# Sheet1.net
KiCad netlist of a schematic drawn in Altium Designer
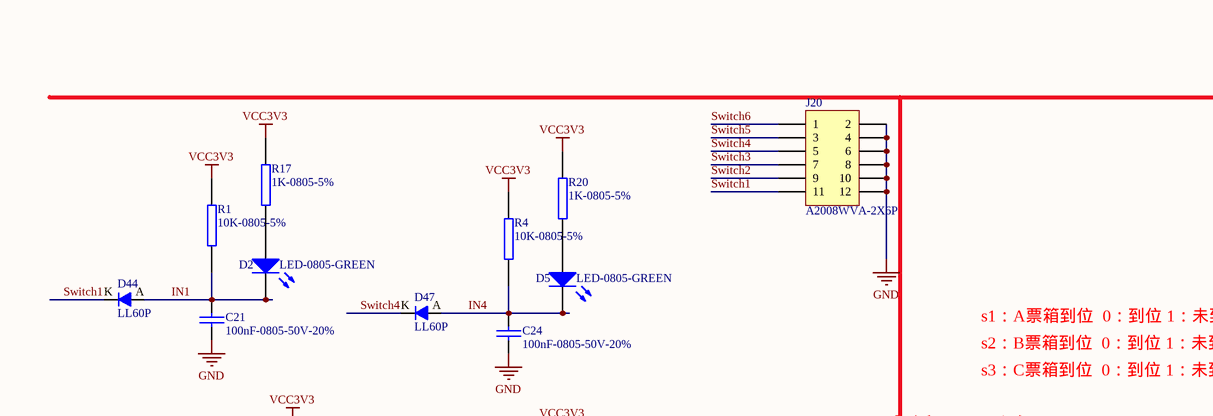
[diagram p0: Sheet1.SchDoc, top left]
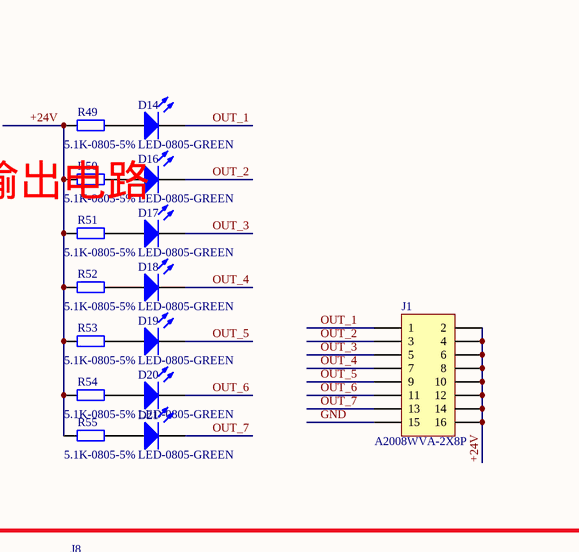
[diagram p1: Sheet1.SchDoc, top middle]
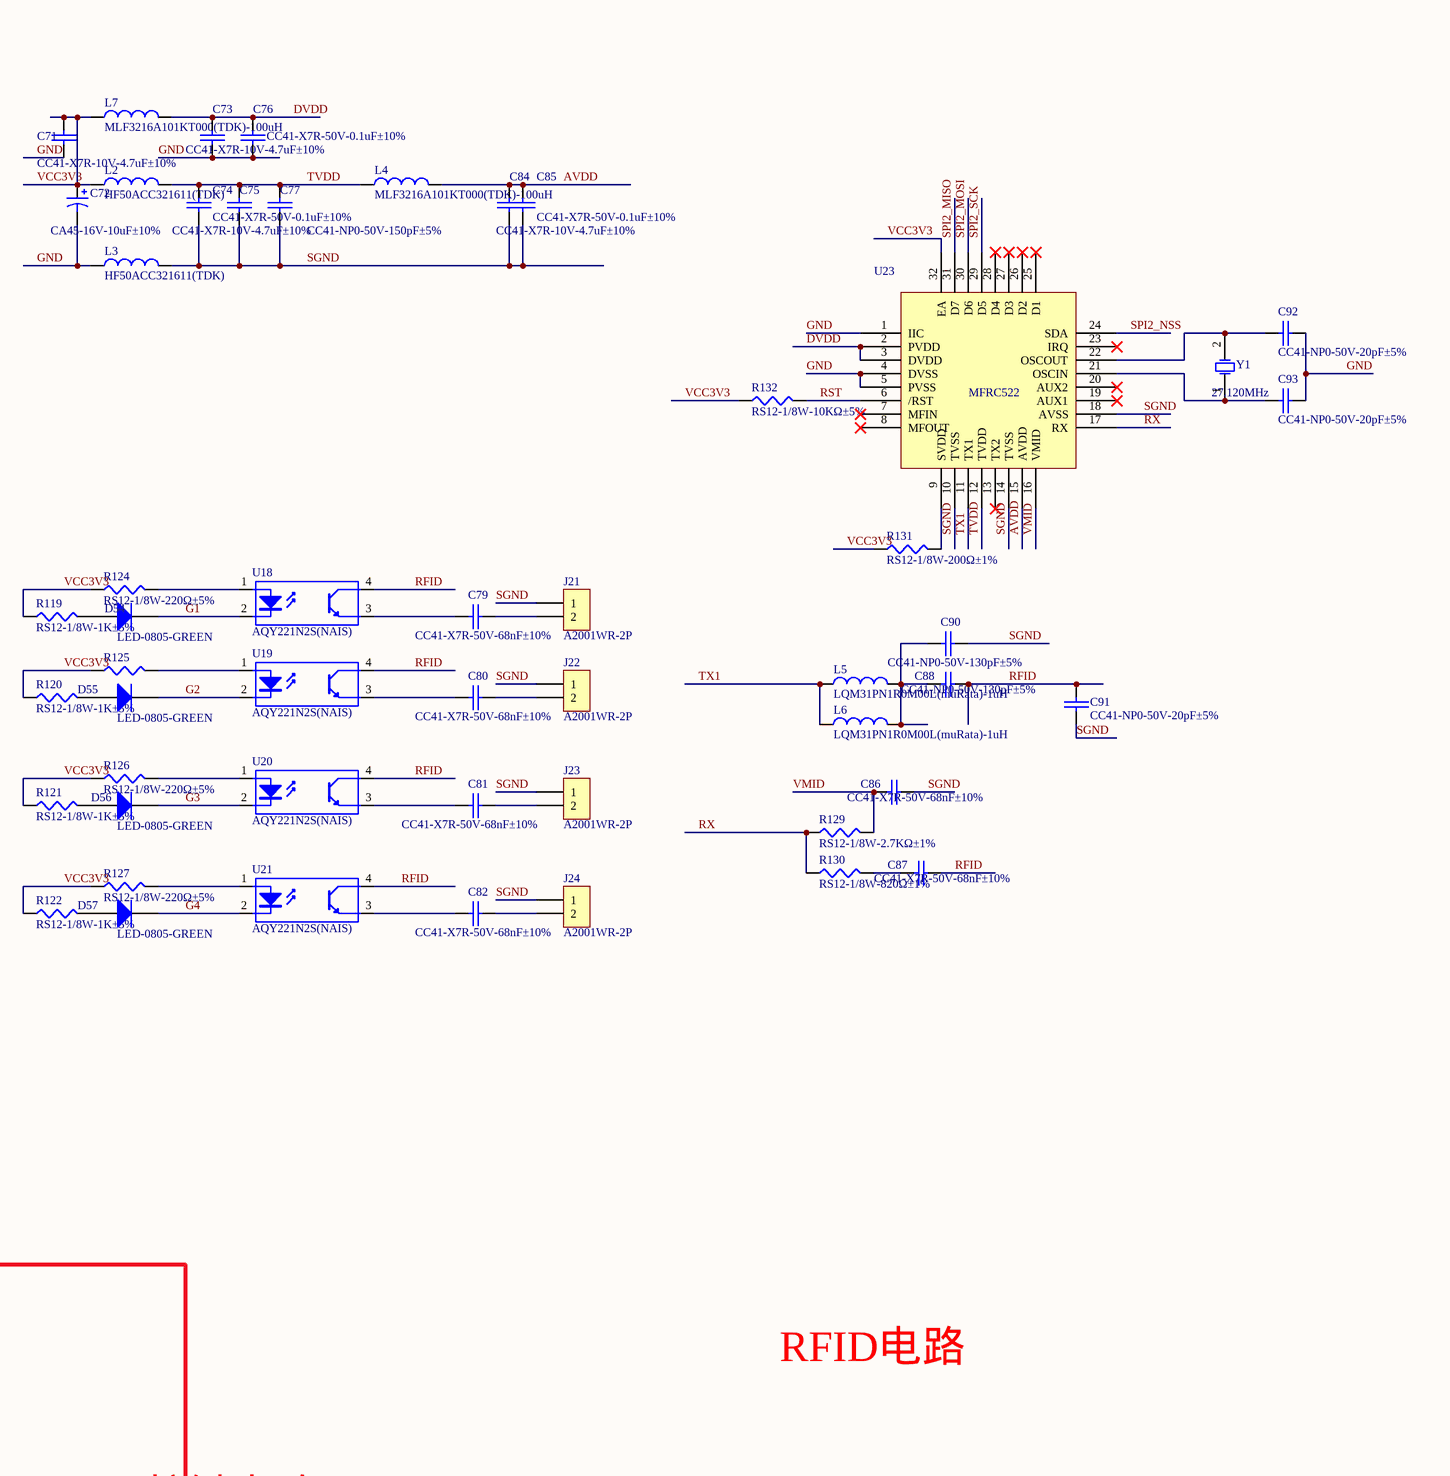
[diagram p2: Sheet1.SchDoc, top right]
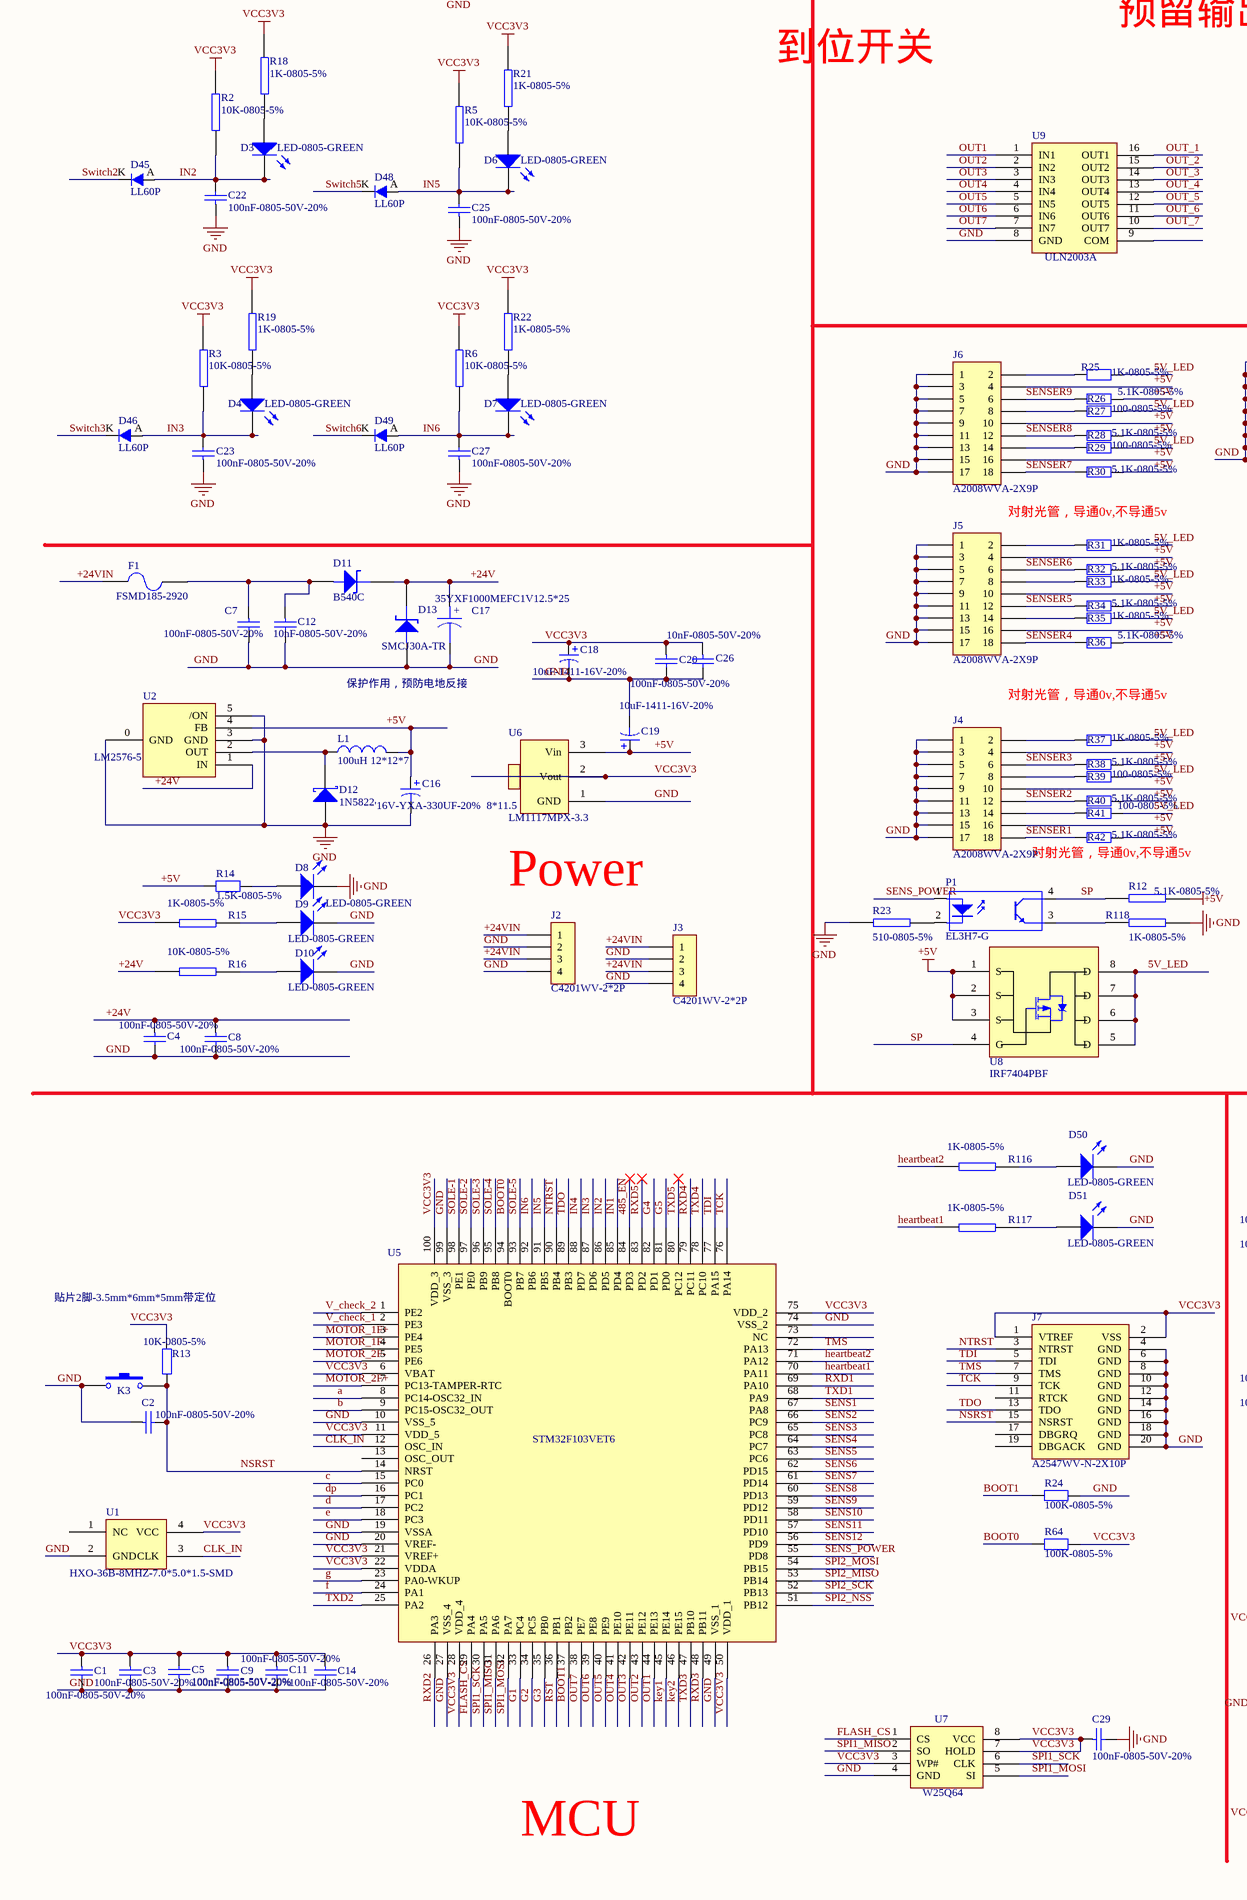
[diagram p3: Sheet1.SchDoc, bottom left]
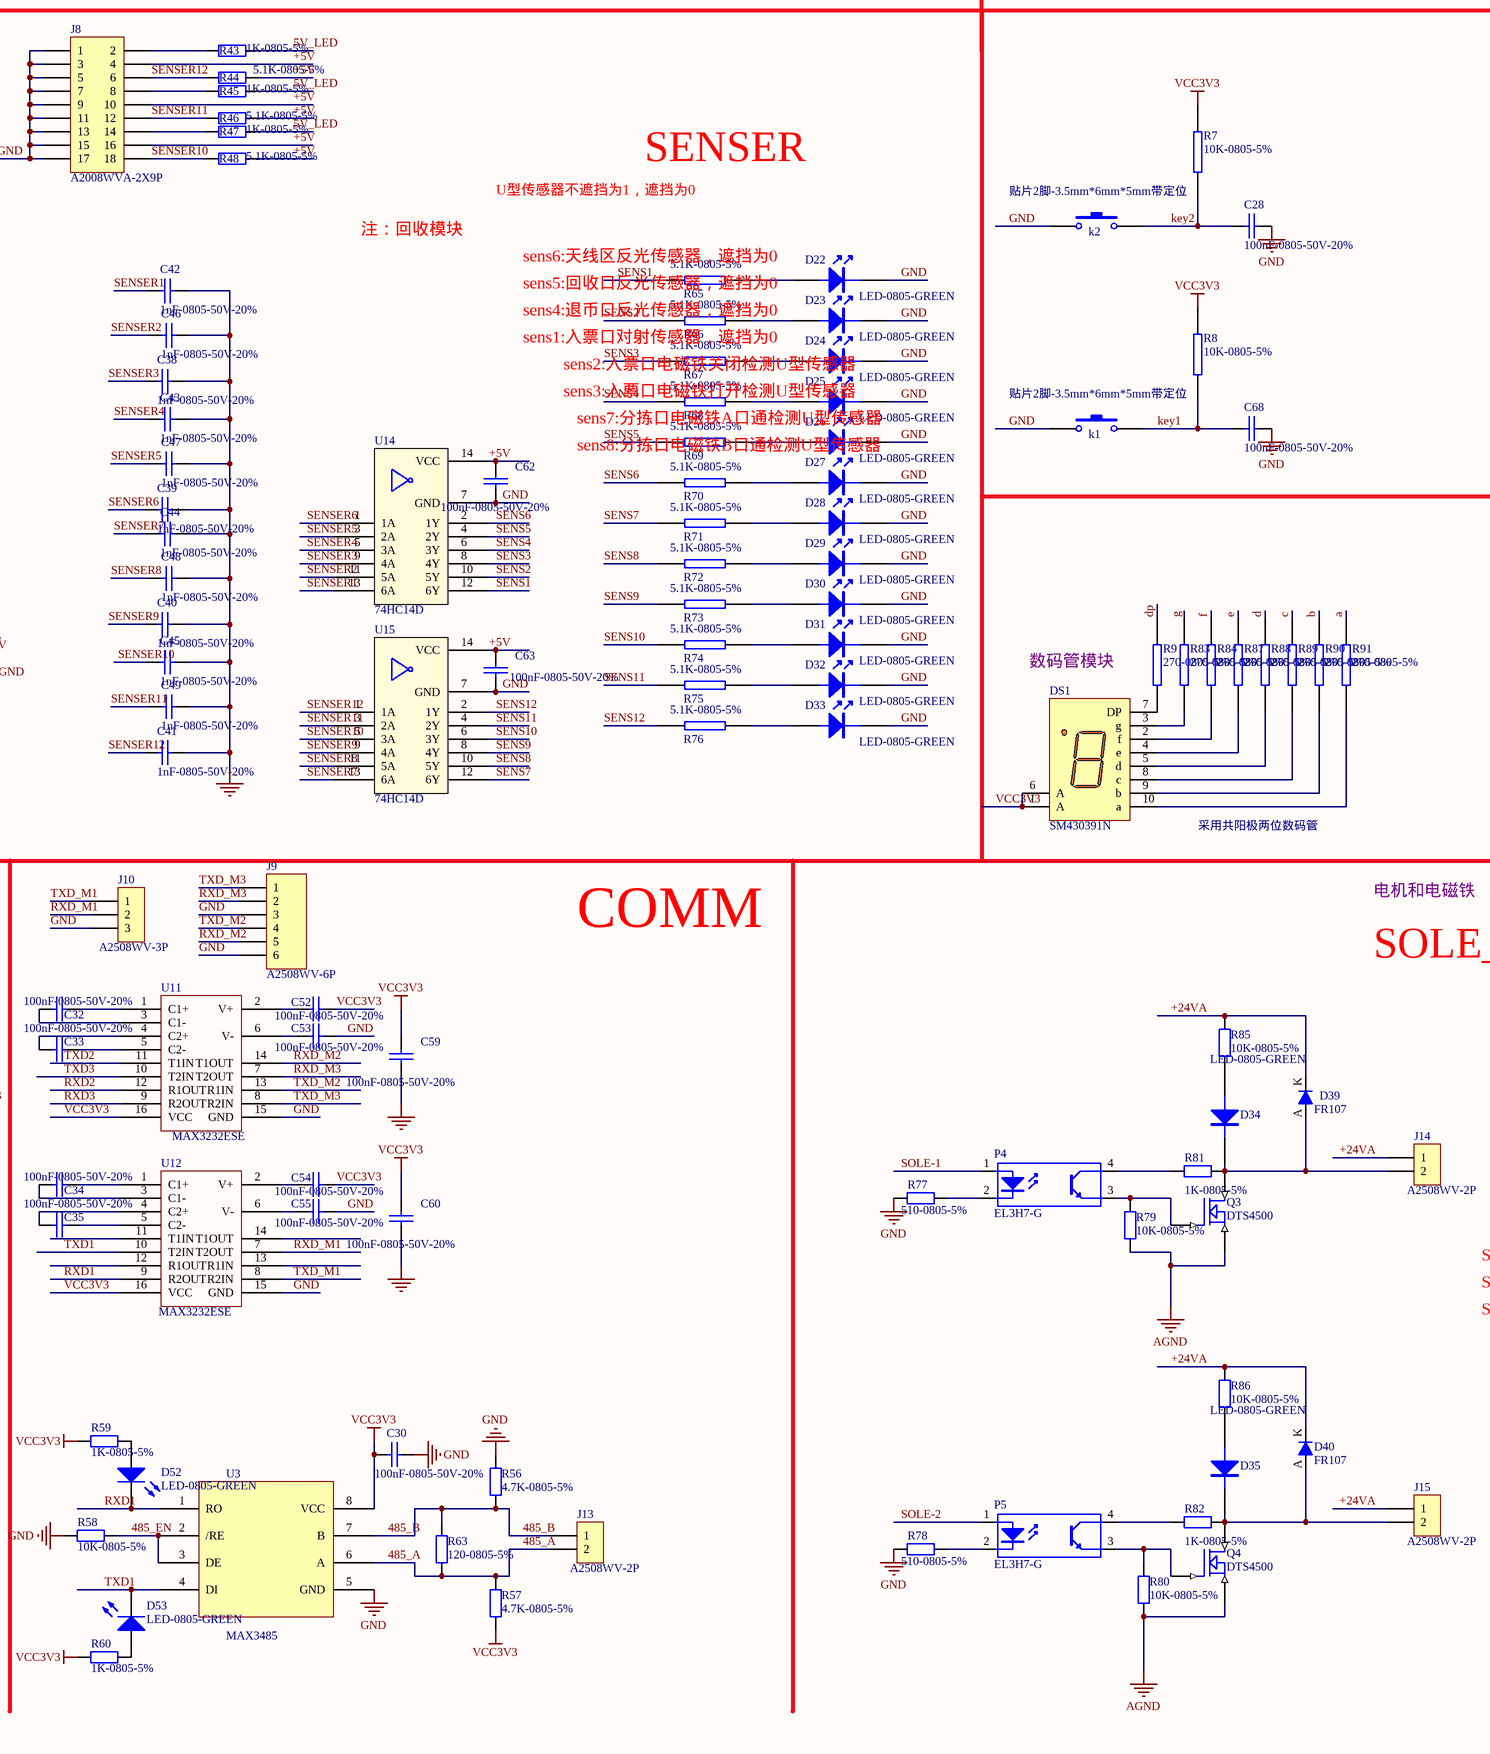
[diagram p4: Sheet1.SchDoc, bottom middle]
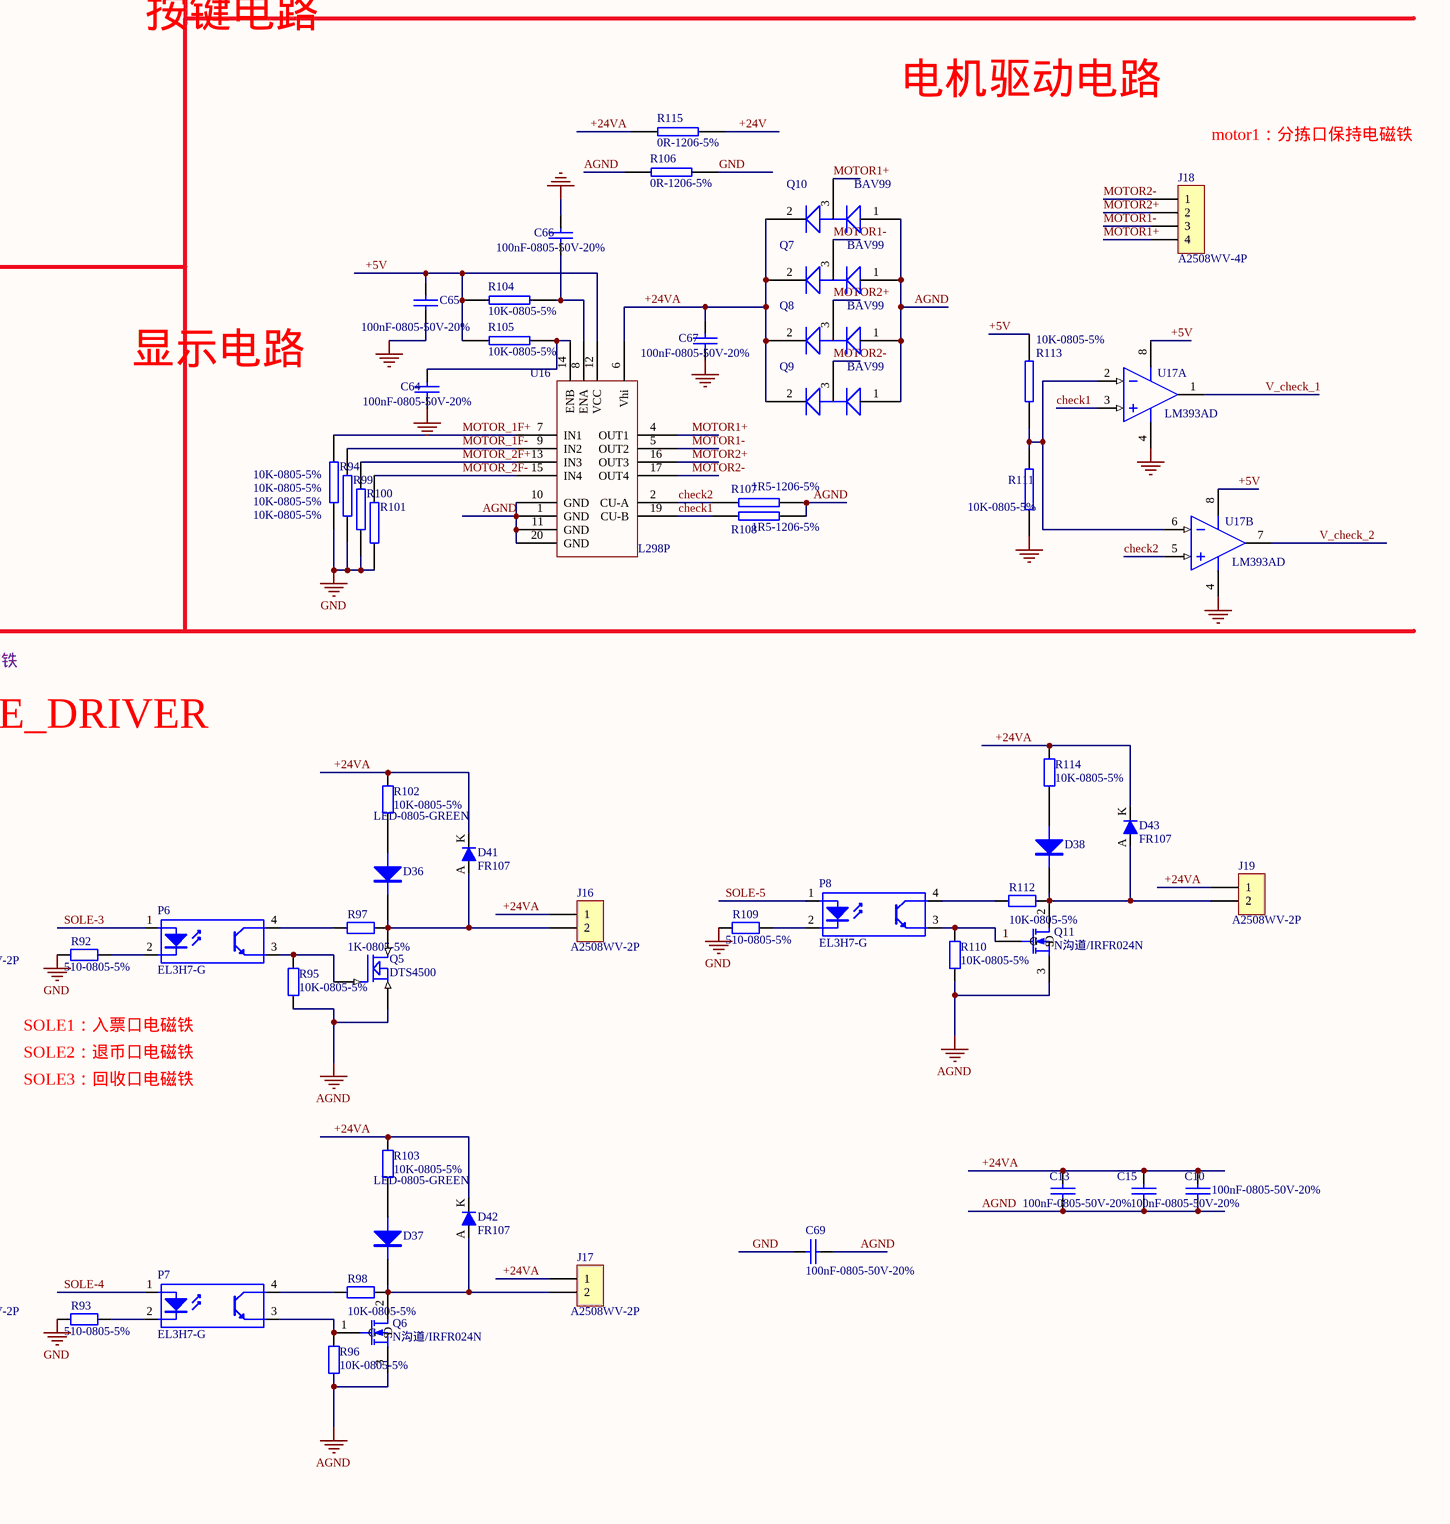
[diagram p5: Sheet1.SchDoc, bottom right]

(export (version "E")
  (design (tool "Eeschema 10.0.6"))
  (components
    (comp (ref "C1")
      (value "100nF-0805-50V-20%")
      (footprint "0805")
      (description "Capacitor")
      (libsource (lib "*") (part "CAP"))
    )
    (comp (ref "C2")
      (value "100nF-0805-50V-20%")
      (footprint "0805")
      (description "Capacitor")
      (libsource (lib "*") (part "CAP"))
    )
    (comp (ref "C3")
      (value "100nF-0805-50V-20%")
      (footprint "0805")
      (description "Capacitor")
      (libsource (lib "*") (part "CAP"))
    )
    (comp (ref "C4")
      (value "100nF-0805-50V-20%")
      (footprint "0805")
      (description "Capacitor")
      (libsource (lib "*") (part "CAP"))
    )
    (comp (ref "C5")
      (value "100nF-0805-50V-20%")
      (footprint "0805")
      (description "Capacitor")
      (libsource (lib "*") (part "CAP"))
    )
    (comp (ref "C7")
      (value "100nF-0805-50V-20%")
      (footprint "0805")
      (description "Capacitor")
      (libsource (lib "*") (part "CAP"))
    )
    (comp (ref "C8")
      (value "100nF-0805-50V-20%")
      (footprint "0805")
      (description "Capacitor")
      (libsource (lib "*") (part "CAP"))
    )
    (comp (ref "C9")
      (value "100nF-0805-50V-20%")
      (footprint "0805")
      (description "Capacitor")
      (libsource (lib "*") (part "CAP"))
    )
    (comp (ref "C10")
      (value "100nF-0805-50V-20%")
      (footprint "0805")
      (description "Capacitor")
      (libsource (lib "*") (part "CAP"))
    )
    (comp (ref "C11")
      (value "100nF-0805-50V-20%")
      (footprint "0805")
      (description "Capacitor")
      (libsource (lib "*") (part "CAP"))
    )
    (comp (ref "C12")
      (value "10nF-0805-50V-20%")
      (footprint "0805")
      (description "Capacitor")
      (libsource (lib "*") (part "CAP"))
    )
    (comp (ref "C13")
      (value "100nF-0805-50V-20%")
      (footprint "0805")
      (description "Capacitor")
      (libsource (lib "*") (part "CAP"))
    )
    (comp (ref "C14")
      (value "100nF-0805-50V-20%")
      (footprint "0805")
      (description "Capacitor")
      (libsource (lib "*") (part "CAP"))
    )
    (comp (ref "C15")
      (value "100nF-0805-50V-20%")
      (footprint "0805")
      (description "Capacitor")
      (libsource (lib "*") (part "CAP"))
    )
    (comp (ref "C16")
      (value "'16V-YXA-330UF-20%  8*11.5")
      (footprint "RB.2/.4 - 8MM")
      (description "Polarized Capacitor (Radial)")
      (fields (field (name "PUBLISHER") "Altium Limited"))
      (libsource (lib "Miscellaneous Devices") (part "Cap Pol1"))
    )
    (comp (ref "C17")
      (value "35YXF1000MEFC1V12.5*25")
      (footprint "RB.2/.4")
      (description "Capacitor")
      (libsource (lib "*") (part "CAPACITOR POL"))
    )
    (comp (ref "C18")
      (value "10uF-1411-16V-20%")
      (footprint "1411-B")
      (description "Polarized Capacitor (Radial)")
      (fields (field (name "PUBLISHER") "Altium Limited"))
      (libsource (lib "Miscellaneous Devices") (part "Cap Pol1"))
    )
    (comp (ref "C19")
      (value "10uF-1411-16V-20%")
      (footprint "1411-B")
      (description "Polarized Capacitor (Radial)")
      (fields (field (name "PUBLISHER") "Altium Limited"))
      (libsource (lib "Miscellaneous Devices") (part "Cap Pol1"))
    )
    (comp (ref "C20")
      (value "100nF-0805-50V-20%")
      (footprint "0805")
      (description "Capacitor")
      (libsource (lib "*") (part "CAP"))
    )
    (comp (ref "C21")
      (value "100nF-0805-50V-20%")
      (footprint "0805")
      (description "Capacitor")
      (libsource (lib "*") (part "CAP"))
    )
    (comp (ref "C22")
      (value "100nF-0805-50V-20%")
      (footprint "0805")
      (description "Capacitor")
      (libsource (lib "*") (part "CAP"))
    )
    (comp (ref "C23")
      (value "100nF-0805-50V-20%")
      (footprint "0805")
      (description "Capacitor")
      (libsource (lib "*") (part "CAP"))
    )
    (comp (ref "C24")
      (value "100nF-0805-50V-20%")
      (footprint "0805")
      (description "Capacitor")
      (libsource (lib "*") (part "CAP"))
    )
    (comp (ref "C25")
      (value "100nF-0805-50V-20%")
      (footprint "0805")
      (description "Capacitor")
      (libsource (lib "*") (part "CAP"))
    )
    (comp (ref "C26")
      (value "10nF-0805-50V-20%")
      (footprint "0805")
      (description "Capacitor")
      (libsource (lib "*") (part "CAP"))
    )
    (comp (ref "C27")
      (value "100nF-0805-50V-20%")
      (footprint "0805")
      (description "Capacitor")
      (libsource (lib "*") (part "CAP"))
    )
    (comp (ref "C28")
      (value "100nF-0805-50V-20%")
      (footprint "0805")
      (description "Capacitor")
      (libsource (lib "*") (part "CAP"))
    )
    (comp (ref "C29")
      (value "100nF-0805-50V-20%")
      (footprint "0805")
      (description "Capacitor")
      (libsource (lib "*") (part "CAP"))
    )
    (comp (ref "C30")
      (value "100nF-0805-50V-20%")
      (footprint "0805")
      (description "Capacitor")
      (libsource (lib "*") (part "CAP"))
    )
    (comp (ref "C32")
      (value "100nF-0805-50V-20%")
      (footprint "0805")
      (description "Capacitor")
      (libsource (lib "") (part "CAP_1"))
    )
    (comp (ref "C33")
      (value "100nF-0805-50V-20%")
      (footprint "0805")
      (description "Capacitor")
      (libsource (lib "") (part "CAP_1"))
    )
    (comp (ref "C34")
      (value "100nF-0805-50V-20%")
      (footprint "0805")
      (description "Capacitor")
      (libsource (lib "") (part "CAP_1"))
    )
    (comp (ref "C35")
      (value "100nF-0805-50V-20%")
      (footprint "0805")
      (description "Capacitor")
      (libsource (lib "") (part "CAP_1"))
    )
    (comp (ref "C38")
      (value "1nF-0805-50V-20%")
      (footprint "0805")
      (description "Capacitor")
      (libsource (lib "*") (part "CAP"))
    )
    (comp (ref "C39")
      (value "1nF-0805-50V-20%")
      (footprint "0805")
      (description "Capacitor")
      (libsource (lib "*") (part "CAP"))
    )
    (comp (ref "C40")
      (value "1nF-0805-50V-20%")
      (footprint "0805")
      (description "Capacitor")
      (libsource (lib "*") (part "CAP"))
    )
    (comp (ref "C41")
      (value "1nF-0805-50V-20%")
      (footprint "0805")
      (description "Capacitor")
      (libsource (lib "*") (part "CAP"))
    )
    (comp (ref "C42")
      (value "1nF-0805-50V-20%")
      (footprint "0805")
      (description "Capacitor")
      (libsource (lib "*") (part "CAP"))
    )
    (comp (ref "C43")
      (value "1nF-0805-50V-20%")
      (footprint "0805")
      (description "Capacitor")
      (libsource (lib "*") (part "CAP"))
    )
    (comp (ref "C44")
      (value "1nF-0805-50V-20%")
      (footprint "0805")
      (description "Capacitor")
      (libsource (lib "*") (part "CAP"))
    )
    (comp (ref "C45")
      (value "1nF-0805-50V-20%")
      (footprint "0805")
      (description "Capacitor")
      (libsource (lib "*") (part "CAP"))
    )
    (comp (ref "C46")
      (value "1nF-0805-50V-20%")
      (footprint "0805")
      (description "Capacitor")
      (libsource (lib "*") (part "CAP"))
    )
    (comp (ref "C47")
      (value "1nF-0805-50V-20%")
      (footprint "0805")
      (description "Capacitor")
      (libsource (lib "*") (part "CAP"))
    )
    (comp (ref "C48")
      (value "1nF-0805-50V-20%")
      (footprint "0805")
      (description "Capacitor")
      (libsource (lib "*") (part "CAP"))
    )
    (comp (ref "C49")
      (value "1nF-0805-50V-20%")
      (footprint "0805")
      (description "Capacitor")
      (libsource (lib "*") (part "CAP"))
    )
    (comp (ref "C52")
      (value "100nF-0805-50V-20%")
      (footprint "0805")
      (description "Capacitor")
      (libsource (lib "") (part "CAP_1"))
    )
    (comp (ref "C53")
      (value "100nF-0805-50V-20%")
      (footprint "0805")
      (description "Capacitor")
      (libsource (lib "") (part "CAP_1"))
    )
    (comp (ref "C54")
      (value "100nF-0805-50V-20%")
      (footprint "0805")
      (description "Capacitor")
      (libsource (lib "") (part "CAP_1"))
    )
    (comp (ref "C55")
      (value "100nF-0805-50V-20%")
      (footprint "0805")
      (description "Capacitor")
      (libsource (lib "") (part "CAP_1"))
    )
    (comp (ref "C59")
      (value "100nF-0805-50V-20%")
      (footprint "0805")
      (description "Capacitor")
      (libsource (lib "*") (part "CAP"))
    )
    (comp (ref "C60")
      (value "100nF-0805-50V-20%")
      (footprint "0805")
      (description "Capacitor")
      (libsource (lib "*") (part "CAP"))
    )
    (comp (ref "C62")
      (value "100nF-0805-50V-20%")
      (footprint "0805")
      (description "Capacitor")
      (libsource (lib "*") (part "CAP"))
    )
    (comp (ref "C63")
      (value "100nF-0805-50V-20%")
      (footprint "0805")
      (description "Capacitor")
      (libsource (lib "*") (part "CAP"))
    )
    (comp (ref "C64")
      (value "100nF-0805-50V-20%")
      (footprint "0805")
      (description "Capacitor")
      (libsource (lib "*") (part "CAP"))
    )
    (comp (ref "C65")
      (value "100nF-0805-50V-20%")
      (footprint "0805")
      (description "Capacitor")
      (libsource (lib "*") (part "CAP"))
    )
    (comp (ref "C66")
      (value "100nF-0805-50V-20%")
      (footprint "0805")
      (description "Capacitor")
      (libsource (lib "*") (part "CAP"))
    )
    (comp (ref "C67")
      (value "100nF-0805-50V-20%")
      (footprint "0805")
      (description "Capacitor")
      (libsource (lib "*") (part "CAP"))
    )
    (comp (ref "C68")
      (value "100nF-0805-50V-20%")
      (footprint "0805")
      (description "Capacitor")
      (libsource (lib "*") (part "CAP"))
    )
    (comp (ref "C69")
      (value "100nF-0805-50V-20%")
      (footprint "0805")
      (description "Capacitor")
      (libsource (lib "*") (part "CAP"))
    )
    (comp (ref "C71")
      (value "CC41-X7R-10V-4.7uF±10%")
      (footprint "RFID主控板-MFC522:1206C")
      (description "Capacitor")
      (libsource (lib "PCB_Project1_1") (part "CAP"))
    )
    (comp (ref "C72")
      (value "CA45-16V-10uF±10%")
      (footprint "RFID主控板-MFC522:3216-A")
      (description "Polarized Capacitor (Radial)")
      (fields (field (name "PUBLISHER") "Altium Limited"))
      (libsource (lib "Miscellaneous Devices") (part "Cap Pol1"))
    )
    (comp (ref "C73")
      (value "CC41-X7R-10V-4.7uF±10%")
      (footprint "1206C")
      (description "Capacitor")
      (libsource (lib "PCB_Project1_1") (part "CAP"))
    )
    (comp (ref "C74")
      (value "CC41-X7R-10V-4.7uF±10%")
      (footprint "RFID主控板-MFC522:1206C")
      (description "Capacitor")
      (libsource (lib "PCB_Project1_1") (part "CAP"))
    )
    (comp (ref "C75")
      (value "CC41-X7R-50V-0.1uF±10%")
      (footprint "0805C")
      (description "Capacitor")
      (libsource (lib "PCB_Project1_1") (part "CAP"))
    )
    (comp (ref "C76")
      (value "CC41-X7R-50V-0.1uF±10%")
      (footprint "0805C")
      (description "Capacitor")
      (libsource (lib "PCB_Project1_1") (part "CAP"))
    )
    (comp (ref "C77")
      (value "CC41-NP0-50V-150pF±5%")
      (footprint "0805C")
      (description "Capacitor")
      (libsource (lib "PCB_Project1_1") (part "CAP"))
    )
    (comp (ref "C79")
      (value "CC41-X7R-50V-68nF±10%")
      (footprint "RFID主控板-MFC522:0805C")
      (description "Capacitor")
      (libsource (lib "PCB_Project1_1") (part "CAP"))
    )
    (comp (ref "C80")
      (value "CC41-X7R-50V-68nF±10%")
      (footprint "0805C")
      (description "Capacitor")
      (libsource (lib "PCB_Project1_1") (part "CAP"))
    )
    (comp (ref "C81")
      (value "CC41-X7R-50V-68nF±10%")
      (footprint "0805C")
      (description "Capacitor")
      (libsource (lib "PCB_Project1_1") (part "CAP"))
    )
    (comp (ref "C82")
      (value "CC41-X7R-50V-68nF±10%")
      (footprint "0805C")
      (description "Capacitor")
      (libsource (lib "PCB_Project1_1") (part "CAP"))
    )
    (comp (ref "C84")
      (value "CC41-X7R-10V-4.7uF±10%")
      (footprint "1206C")
      (description "Capacitor")
      (libsource (lib "PCB_Project1_1") (part "CAP"))
    )
    (comp (ref "C85")
      (value "CC41-X7R-50V-0.1uF±10%")
      (footprint "0805C")
      (description "Capacitor")
      (libsource (lib "PCB_Project1_1") (part "CAP"))
    )
    (comp (ref "C86")
      (value "CC41-X7R-50V-68nF±10%")
      (footprint "0805C")
      (description "Capacitor")
      (libsource (lib "PCB_Project1_1") (part "CAP"))
    )
    (comp (ref "C87")
      (value "CC41-X7R-50V-68nF±10%")
      (footprint "0805C")
      (description "Capacitor")
      (libsource (lib "PCB_Project1_1") (part "CAP"))
    )
    (comp (ref "C88")
      (value "CC41-NP0-50V-130pF±5%")
      (footprint "0805C")
      (description "Capacitor")
      (libsource (lib "PCB_Project1_1") (part "CAP"))
    )
    (comp (ref "C90")
      (value "CC41-NP0-50V-130pF±5%")
      (footprint "0805C")
      (description "Capacitor")
      (libsource (lib "PCB_Project1_1") (part "CAP"))
    )
    (comp (ref "C91")
      (value "CC41-NP0-50V-20pF±5%")
      (footprint "0805C")
      (description "Capacitor")
      (libsource (lib "PCB_Project1_1") (part "CAP"))
    )
    (comp (ref "C92")
      (value "CC41-NP0-50V-20pF±5%")
      (footprint "0805C")
      (description "Capacitor")
      (libsource (lib "PCB_Project1_1") (part "CAP"))
    )
    (comp (ref "C93")
      (value "CC41-NP0-50V-20pF±5%")
      (footprint "0805C")
      (description "Capacitor")
      (libsource (lib "PCB_Project1_1") (part "CAP"))
    )
    (comp (ref "D2")
      (value "LED-0805-GREEN")
      (footprint "LED-0805")
      (description "Typical INFRARED GaAs LED")
      (fields (field (name "PUBLISHER") "Altium Limited"))
      (libsource (lib "Miscellaneous Devices") (part "LED0"))
    )
    (comp (ref "D3")
      (value "LED-0805-GREEN")
      (footprint "LED-0805")
      (description "Typical INFRARED GaAs LED")
      (fields (field (name "PUBLISHER") "Altium Limited"))
      (libsource (lib "Miscellaneous Devices") (part "LED0"))
    )
    (comp (ref "D4")
      (value "LED-0805-GREEN")
      (footprint "LED-0805")
      (description "Typical INFRARED GaAs LED")
      (fields (field (name "PUBLISHER") "Altium Limited"))
      (libsource (lib "Miscellaneous Devices") (part "LED0"))
    )
    (comp (ref "D5")
      (value "LED-0805-GREEN")
      (footprint "LED-0805")
      (description "Typical INFRARED GaAs LED")
      (fields (field (name "PUBLISHER") "Altium Limited"))
      (libsource (lib "Miscellaneous Devices") (part "LED0"))
    )
    (comp (ref "D6")
      (value "LED-0805-GREEN")
      (footprint "LED-0805")
      (description "Typical INFRARED GaAs LED")
      (fields (field (name "PUBLISHER") "Altium Limited"))
      (libsource (lib "Miscellaneous Devices") (part "LED0"))
    )
    (comp (ref "D7")
      (value "LED-0805-GREEN")
      (footprint "LED-0805")
      (description "Typical INFRARED GaAs LED")
      (fields (field (name "PUBLISHER") "Altium Limited"))
      (libsource (lib "Miscellaneous Devices") (part "LED0"))
    )
    (comp (ref "D8")
      (value "LED-0805-GREEN")
      (footprint "LED-0805")
      (description "Typical INFRARED GaAs LED")
      (fields (field (name "PUBLISHER") "Altium Limited"))
      (libsource (lib "Miscellaneous Devices") (part "LED0"))
    )
    (comp (ref "D9")
      (value "LED-0805-GREEN")
      (footprint "LED-0805")
      (description "Typical INFRARED GaAs LED")
      (fields (field (name "PUBLISHER") "Altium Limited"))
      (libsource (lib "Miscellaneous Devices") (part "LED0"))
    )
    (comp (ref "D10")
      (value "LED-0805-GREEN")
      (footprint "LED-0805")
      (description "Typical INFRARED GaAs LED")
      (fields (field (name "PUBLISHER") "Altium Limited"))
      (libsource (lib "Miscellaneous Devices") (part "LED0"))
    )
    (comp (ref "D11")
      (value "B540C")
      (footprint "SMC")
      (description "Zener Diode")
      (libsource (lib "*") (part "ZENER2"))
    )
    (comp (ref "D12")
      (value "1N5822")
      (footprint "IN5822 SMT")
      (description "Schottky Diode")
      (fields (field (name "PUBLISHER") "Altium Limited"))
      (libsource (lib "Miscellaneous Devices") (part "D Schottky"))
    )
    (comp (ref "D13")
      (value "SMCJ30A-TR")
      (footprint "SMC")
      (description "Zener Diode")
      (libsource (lib "*") (part "ZENER2"))
    )
    (comp (ref "D14")
      (value "LED-0805-GREEN")
      (footprint "LED-0805")
      (description "Typical INFRARED GaAs LED")
      (fields (field (name "PUBLISHER") "Altium Limited"))
      (libsource (lib "Miscellaneous Devices") (part "LED0"))
    )
    (comp (ref "D16")
      (value "LED-0805-GREEN")
      (footprint "LED-0805")
      (description "Typical INFRARED GaAs LED")
      (fields (field (name "PUBLISHER") "Altium Limited"))
      (libsource (lib "Miscellaneous Devices") (part "LED0"))
    )
    (comp (ref "D17")
      (value "LED-0805-GREEN")
      (footprint "LED-0805")
      (description "Typical INFRARED GaAs LED")
      (fields (field (name "PUBLISHER") "Altium Limited"))
      (libsource (lib "Miscellaneous Devices") (part "LED0"))
    )
    (comp (ref "D18")
      (value "LED-0805-GREEN")
      (footprint "LED-0805")
      (description "Typical INFRARED GaAs LED")
      (fields (field (name "PUBLISHER") "Altium Limited"))
      (libsource (lib "Miscellaneous Devices") (part "LED0"))
    )
    (comp (ref "D19")
      (value "LED-0805-GREEN")
      (footprint "LED-0805")
      (description "Typical INFRARED GaAs LED")
      (fields (field (name "PUBLISHER") "Altium Limited"))
      (libsource (lib "Miscellaneous Devices") (part "LED0"))
    )
    (comp (ref "D20")
      (value "LED-0805-GREEN")
      (footprint "LED-0805")
      (description "Typical INFRARED GaAs LED")
      (fields (field (name "PUBLISHER") "Altium Limited"))
      (libsource (lib "Miscellaneous Devices") (part "LED0"))
    )
    (comp (ref "D21")
      (value "LED-0805-GREEN")
      (footprint "LED-0805")
      (description "Typical INFRARED GaAs LED")
      (fields (field (name "PUBLISHER") "Altium Limited"))
      (libsource (lib "Miscellaneous Devices") (part "LED0"))
    )
    (comp (ref "D22") (value "LED-0805-GREEN") (footprint "LED-0805") (libsource (lib "*") (part "LED")))
    (comp (ref "D23") (value "LED-0805-GREEN") (footprint "LED-0805") (libsource (lib "*") (part "LED")))
    (comp (ref "D24") (value "LED-0805-GREEN") (footprint "LED-0805") (libsource (lib "*") (part "LED")))
    (comp (ref "D25") (value "LED-0805-GREEN") (footprint "LED-0805") (libsource (lib "*") (part "LED")))
    (comp (ref "D26") (value "LED-0805-GREEN") (footprint "LED-0805") (libsource (lib "*") (part "LED")))
    (comp (ref "D27") (value "LED-0805-GREEN") (footprint "LED-0805") (libsource (lib "*") (part "LED")))
    (comp (ref "D28") (value "LED-0805-GREEN") (footprint "LED-0805") (libsource (lib "*") (part "LED")))
    (comp (ref "D29") (value "LED-0805-GREEN") (footprint "LED-0805") (libsource (lib "*") (part "LED")))
    (comp (ref "D30") (value "LED-0805-GREEN") (footprint "LED-0805") (libsource (lib "*") (part "LED")))
    (comp (ref "D31") (value "LED-0805-GREEN") (footprint "LED-0805") (libsource (lib "*") (part "LED")))
    (comp (ref "D32") (value "LED-0805-GREEN") (footprint "LED-0805") (libsource (lib "*") (part "LED")))
    (comp (ref "D33") (value "LED-0805-GREEN") (footprint "LED-0805") (libsource (lib "*") (part "LED")))
    (comp (ref "D34")
      (value "LED-0805-GREEN")
      (footprint "LED-0805")
      (description "Diode")
      (libsource (lib "*") (part "DIODE"))
    )
    (comp (ref "D35")
      (value "LED-0805-GREEN")
      (footprint "LED-0805")
      (description "Diode")
      (libsource (lib "*") (part "DIODE"))
    )
    (comp (ref "D36")
      (value "LED-0805-GREEN")
      (footprint "LED-0805")
      (description "Diode")
      (libsource (lib "*") (part "DIODE"))
    )
    (comp (ref "D37")
      (value "LED-0805-GREEN")
      (footprint "LED-0805")
      (description "Diode")
      (libsource (lib "*") (part "DIODE"))
    )
    (comp (ref "D38")
      (value "LED-0805-GREEN")
      (footprint "LED-0805")
      (description "Diode")
      (libsource (lib "*") (part "DIODE"))
    )
    (comp (ref "D39")
      (value "FR107")
      (footprint "DO-214AC")
      (libsource (lib "T-SZLG-MCB-16-0247-PN-37990042-SZLG-Hopper-01控制板") (part "1N4148"))
    )
    (comp (ref "D40")
      (value "FR107")
      (footprint "DO-214AC")
      (libsource (lib "T-SZLG-MCB-16-0247-PN-37990042-SZLG-Hopper-01控制板") (part "1N4148"))
    )
    (comp (ref "D41")
      (value "FR107")
      (footprint "DO-214AC")
      (libsource (lib "T-SZLG-MCB-16-0247-PN-37990042-SZLG-Hopper-01控制板") (part "1N4148"))
    )
    (comp (ref "D42")
      (value "FR107")
      (footprint "DO-214AC")
      (libsource (lib "T-SZLG-MCB-16-0247-PN-37990042-SZLG-Hopper-01控制板") (part "1N4148"))
    )
    (comp (ref "D43")
      (value "FR107")
      (footprint "DO-214AC")
      (libsource (lib "T-SZLG-MCB-16-0247-PN-37990042-SZLG-Hopper-01控制板") (part "1N4148"))
    )
    (comp (ref "D44")
      (value "LL60P")
      (footprint "PCB22:DIODE")
      (libsource (lib "T-SZLG-MCB-16-0247-PN-37990042-SZLG-Hopper-01控制板") (part "1N4148"))
    )
    (comp (ref "D45")
      (value "LL60P")
      (footprint "DIODE")
      (libsource (lib "T-SZLG-MCB-16-0247-PN-37990042-SZLG-Hopper-01控制板") (part "1N4148"))
    )
    (comp (ref "D46")
      (value "LL60P")
      (footprint "DIODE")
      (libsource (lib "T-SZLG-MCB-16-0247-PN-37990042-SZLG-Hopper-01控制板") (part "1N4148"))
    )
    (comp (ref "D47")
      (value "LL60P")
      (footprint "DIODE")
      (libsource (lib "T-SZLG-MCB-16-0247-PN-37990042-SZLG-Hopper-01控制板") (part "1N4148"))
    )
    (comp (ref "D48")
      (value "LL60P")
      (footprint "DIODE")
      (libsource (lib "T-SZLG-MCB-16-0247-PN-37990042-SZLG-Hopper-01控制板") (part "1N4148"))
    )
    (comp (ref "D49")
      (value "LL60P")
      (footprint "DIODE")
      (libsource (lib "T-SZLG-MCB-16-0247-PN-37990042-SZLG-Hopper-01控制板") (part "1N4148"))
    )
    (comp (ref "D50")
      (value "LED-0805-GREEN")
      (footprint "LED-0805")
      (description "Typical INFRARED GaAs LED")
      (fields (field (name "PUBLISHER") "Altium Limited"))
      (libsource (lib "Miscellaneous Devices") (part "LED0"))
    )
    (comp (ref "D51")
      (value "LED-0805-GREEN")
      (footprint "LED-0805")
      (description "Typical INFRARED GaAs LED")
      (fields (field (name "PUBLISHER") "Altium Limited"))
      (libsource (lib "Miscellaneous Devices") (part "LED0"))
    )
    (comp (ref "D52")
      (value "LED-0805-GREEN")
      (footprint "LED-0805")
      (description "Typical INFRARED GaAs LED")
      (fields (field (name "PUBLISHER") "Altium Limited"))
      (libsource (lib "Miscellaneous Devices") (part "LED0"))
    )
    (comp (ref "D53")
      (value "LED-0805-GREEN")
      (footprint "LED-0805")
      (description "Typical INFRARED GaAs LED")
      (fields (field (name "PUBLISHER") "Altium Limited"))
      (libsource (lib "Miscellaneous Devices") (part "LED0"))
    )
    (comp (ref "D54")
      (value "LED-0805-GREEN")
      (footprint "RFID主控板-MFC522:0805D")
      (description "Default Diode")
      (fields (field (name "PUBLISHER") "Altium Limited"))
      (libsource (lib "Miscellaneous Devices") (part "Diode"))
    )
    (comp (ref "D55")
      (value "LED-0805-GREEN")
      (footprint "0805D")
      (description "Default Diode")
      (fields (field (name "PUBLISHER") "Altium Limited"))
      (libsource (lib "Miscellaneous Devices") (part "Diode"))
    )
    (comp (ref "D56")
      (value "LED-0805-GREEN")
      (footprint "0805D")
      (description "Default Diode")
      (fields (field (name "PUBLISHER") "Altium Limited"))
      (libsource (lib "Miscellaneous Devices") (part "Diode"))
    )
    (comp (ref "D57")
      (value "LED-0805-GREEN")
      (footprint "0805D")
      (description "Default Diode")
      (fields (field (name "PUBLISHER") "Altium Limited"))
      (libsource (lib "Miscellaneous Devices") (part "Diode"))
    )
    (comp (ref "DS1")
      (value "SM430391N")
      (footprint "LEDDIP-10")
      (description "7.62 mm Black Surface Orange 7-Segment Display: CA, RH DP")
      (fields (field (name "PUBLISHER") "Altium Limited"))
      (libsource (lib "*") (part "Dpy Amber-CA"))
    )
    (comp (ref "F1")
      (value "FSMD185-2920")
      (footprint "2920")
      (description "Fuse")
      (libsource (lib "*") (part "FUSE2"))
    )
    (comp (ref "J1")
      (value "A2008WVA-2X8P")
      (footprint "PCB12:A2008WVA-2X8P")
      (description "Header, 8-Pin, Dual row")
      (fields (field (name "PUBLISHER") "Altium Limited"))
      (libsource (lib "Miscellaneous Connectors") (part "Header 8X2"))
    )
    (comp (ref "J2")
      (value "C4201WV-2*2P")
      (footprint "MX4 .2- 2*2P-180")
      (description "Connector")
      (libsource (lib "*") (part "CON4"))
    )
    (comp (ref "J3")
      (value "C4201WV-2*2P")
      (footprint "PCB1:MX4 .2- 2*2P-180")
      (description "Connector")
      (libsource (lib "*") (part "CON4"))
    )
    (comp (ref "J4")
      (value "A2008WVA-2X9P")
      (footprint "PCB12:A2008WVA-2X9P")
      (description "Header, 9-Pin, Dual row")
      (fields (field (name "PUBLISHER") "Altium Limited"))
      (libsource (lib "Miscellaneous Connectors") (part "Header 9X2"))
    )
    (comp (ref "J5")
      (value "A2008WVA-2X9P")
      (footprint "PCB12:A2008WVA-2X9P")
      (description "Header, 9-Pin, Dual row")
      (fields (field (name "PUBLISHER") "Altium Limited"))
      (libsource (lib "Miscellaneous Connectors") (part "Header 9X2"))
    )
    (comp (ref "J6")
      (value "A2008WVA-2X9P")
      (footprint "PCB12:A2008WVA-2X9P")
      (description "Header, 9-Pin, Dual row")
      (fields (field (name "PUBLISHER") "Altium Limited"))
      (libsource (lib "Miscellaneous Connectors") (part "Header 9X2"))
    )
    (comp (ref "J7") (value "A2547WV-N-2X10P") (footprint "JTAG_20") (libsource (lib "STM32") (part "JTAG")))
    (comp (ref "J8")
      (value "A2008WVA-2X9P")
      (footprint "PCB12:A2008WVA-2X9P")
      (description "Header, 9-Pin, Dual row")
      (fields (field (name "PUBLISHER") "Altium Limited"))
      (libsource (lib "Miscellaneous Connectors") (part "Header 9X2"))
    )
    (comp (ref "J9")
      (value "A2508WV-6P")
      (footprint "PCB1:W143-6")
      (description "Header, 6-Pin")
      (fields (field (name "PUBLISHER") "Altium Limited"))
      (libsource (lib "Miscellaneous Connectors") (part "Header 6"))
    )
    (comp (ref "J10")
      (value "A2508WV-3P")
      (footprint "H3")
      (description "Connector")
      (libsource (lib "*") (part "CON3"))
    )
    (comp (ref "J13")
      (value "A2508WV-2P")
      (footprint "2.5-2P  180 JXT")
      (libsource (lib "元件库") (part "CON2"))
    )
    (comp (ref "J14")
      (value "A2508WV-2P")
      (footprint "2.5-2P  180 JXT")
      (libsource (lib "元件库") (part "CON2"))
    )
    (comp (ref "J15")
      (value "A2508WV-2P")
      (footprint "2.5-2P  180 JXT")
      (libsource (lib "元件库") (part "CON2"))
    )
    (comp (ref "J16")
      (value "A2508WV-2P")
      (footprint "2.5-2P  180 JXT")
      (libsource (lib "元件库") (part "CON2"))
    )
    (comp (ref "J17")
      (value "A2508WV-2P")
      (footprint "2.5-2P  180 JXT")
      (libsource (lib "元件库") (part "CON2"))
    )
    (comp (ref "J18")
      (value "A2508WV-4P")
      (footprint "W143-4")
      (description "Connector")
      (libsource (lib "*") (part "CON4"))
    )
    (comp (ref "J19")
      (value "A2508WV-2P")
      (footprint "2.5-2P  180 JXT")
      (libsource (lib "元件库") (part "CON2"))
    )
    (comp (ref "J20")
      (value "A2008WVA-2X6P")
      (footprint "PCB12:A2008WVA-2X6P")
      (description "Header, 6-Pin, Dual row")
      (fields (field (name "PUBLISHER") "Altium Limited"))
      (libsource (lib "Miscellaneous Connectors") (part "Header 6X2"))
    )
    (comp (ref "J21")
      (value "A2001WR-2P")
      (footprint "A2001WR-2P")
      (libsource (lib "PCB_Project1_1") (part "CON2"))
    )
    (comp (ref "J22")
      (value "A2001WR-2P")
      (footprint "A2001WR-2P")
      (libsource (lib "PCB_Project1_1") (part "CON2"))
    )
    (comp (ref "J23")
      (value "A2001WR-2P")
      (footprint "A2001WR-2P")
      (libsource (lib "PCB_Project1_1") (part "CON2"))
    )
    (comp (ref "J24")
      (value "A2001WR-2P")
      (footprint "A2001WR-2P")
      (libsource (lib "PCB_Project1_1") (part "CON2"))
    )
    (comp (ref "k1")
      (value "贴片2脚-3.5mm*6mm*5mm带定位")
      (footprint "BUTTON2")
      (description "Switch")
      (libsource (lib "SilvestStandardSchLib") (part "Switch"))
    )
    (comp (ref "k2")
      (value "贴片2脚-3.5mm*6mm*5mm带定位")
      (footprint "BUTTON2")
      (description "Switch")
      (libsource (lib "SilvestStandardSchLib") (part "Switch"))
    )
    (comp (ref "K3")
      (value "贴片2脚-3.5mm*6mm*5mm带定位")
      (footprint "BUTTON2")
      (description "Switch")
      (libsource (lib "SilvestStandardSchLib") (part "Switch"))
    )
    (comp (ref "L1")
      (value "100uH 12*12*7")
      (footprint "Inductor SMT7")
      (description "Inductor")
      (fields (field (name "PUBLISHER") "Altium Limited"))
      (libsource (lib "Miscellaneous Devices") (part "Inductor"))
    )
    (comp (ref "L2")
      (value "HF50ACC321611(TDK)")
      (footprint "RFID主控板-MFC522:1206L")
      (description "Inductor")
      (fields (field (name "PUBLISHER") "Altium Limited"))
      (libsource (lib "Miscellaneous Devices") (part "Inductor"))
    )
    (comp (ref "L3")
      (value "HF50ACC321611(TDK)")
      (footprint "RFID主控板-MFC522:1206L")
      (description "Inductor")
      (fields (field (name "PUBLISHER") "Altium Limited"))
      (libsource (lib "Miscellaneous Devices") (part "Inductor"))
    )
    (comp (ref "L4")
      (value "MLF3216A101KT000(TDK)-100uH")
      (footprint "RFID主控板-MFC522:1206L")
      (description "Inductor")
      (fields (field (name "PUBLISHER") "Altium Limited"))
      (libsource (lib "Miscellaneous Devices") (part "Inductor"))
    )
    (comp (ref "L5")
      (value "LQM31PN1R0M00L(muRata)-1uH")
      (footprint "RFID主控板-MFC522:1206L")
      (description "Inductor")
      (fields (field (name "PUBLISHER") "Altium Limited"))
      (libsource (lib "Miscellaneous Devices") (part "Inductor"))
    )
    (comp (ref "L6")
      (value "LQM31PN1R0M00L(muRata)-1uH")
      (footprint "RFID主控板-MFC522:1206L")
      (description "Inductor")
      (fields (field (name "PUBLISHER") "Altium Limited"))
      (libsource (lib "Miscellaneous Devices") (part "Inductor"))
    )
    (comp (ref "L7")
      (value "MLF3216A101KT000(TDK)-100uH")
      (footprint "RFID主控板-MFC522:1206L")
      (description "Inductor")
      (fields (field (name "PUBLISHER") "Altium Limited"))
      (libsource (lib "Miscellaneous Devices") (part "Inductor"))
    )
    (comp (ref "P1")
      (value "EL3H7-G")
      (footprint "SSOP4")
      (description "OpticalCoupler")
      (libsource (lib "SilvestStandardSchLib") (part "OpticalCoupler"))
    )
    (comp (ref "P4")
      (value "EL3H7-G")
      (footprint "SSOP4")
      (description "OpticalCoupler")
      (libsource (lib "SilvestStandardSchLib") (part "OpticalCoupler"))
    )
    (comp (ref "P5")
      (value "EL3H7-G")
      (footprint "SSOP4")
      (description "OpticalCoupler")
      (libsource (lib "SilvestStandardSchLib") (part "OpticalCoupler"))
    )
    (comp (ref "P6")
      (value "EL3H7-G")
      (footprint "SSOP4")
      (description "OpticalCoupler")
      (libsource (lib "SilvestStandardSchLib") (part "OpticalCoupler"))
    )
    (comp (ref "P7")
      (value "EL3H7-G")
      (footprint "SSOP4")
      (description "OpticalCoupler")
      (libsource (lib "SilvestStandardSchLib") (part "OpticalCoupler"))
    )
    (comp (ref "P8")
      (value "EL3H7-G")
      (footprint "SSOP4")
      (description "OpticalCoupler")
      (libsource (lib "SilvestStandardSchLib") (part "OpticalCoupler"))
    )
    (comp (ref "Q3") (value "DTS4500") (footprint "SOT-23") (libsource (lib "*") (part "MOSFET N")))
    (comp (ref "Q4") (value "DTS4500") (footprint "SOT-23") (libsource (lib "*") (part "MOSFET N")))
    (comp (ref "Q5") (value "DTS4500") (footprint "SOT-23") (libsource (lib "*") (part "MOSFET N")))
    (comp (ref "Q6")
      (value "N沟道/IRFR024N")
      (footprint "TO-252AA")
      (description "N-Channel MOSFET")
      (fields (field (name "PUBLISHER") "Altium Limited"))
      (libsource (lib "T-SZLG-MCB-16-0247-PN-37990042-SZLG-Hopper-01控制板") (part "MOSFET-N"))
    )
    (comp (ref "Q7") (value "BAV99") (footprint "SOT-23") (libsource (lib "*") (part "BAV99")))
    (comp (ref "Q8") (value "BAV99") (footprint "SOT-23") (libsource (lib "*") (part "BAV99")))
    (comp (ref "Q9") (value "BAV99") (footprint "SOT-23") (libsource (lib "*") (part "BAV99")))
    (comp (ref "Q10") (value "BAV99") (footprint "SOT-23") (libsource (lib "*") (part "BAV99")))
    (comp (ref "Q11")
      (value "N沟道/IRFR024N")
      (footprint "TO-252AA")
      (description "N-Channel MOSFET")
      (fields (field (name "PUBLISHER") "Altium Limited"))
      (libsource (lib "T-SZLG-MCB-16-0247-PN-37990042-SZLG-Hopper-01控制板") (part "MOSFET-N"))
    )
    (comp (ref "R1") (value "10K-0805-5%") (footprint "0805") (libsource (lib "*") (part "RES2")))
    (comp (ref "R2") (value "10K-0805-5%") (footprint "0805") (libsource (lib "*") (part "RES2")))
    (comp (ref "R3") (value "10K-0805-5%") (footprint "0805") (libsource (lib "*") (part "RES2")))
    (comp (ref "R4") (value "10K-0805-5%") (footprint "0805") (libsource (lib "*") (part "RES2")))
    (comp (ref "R5") (value "10K-0805-5%") (footprint "0805") (libsource (lib "*") (part "RES2")))
    (comp (ref "R6") (value "10K-0805-5%") (footprint "0805") (libsource (lib "*") (part "RES2")))
    (comp (ref "R7") (value "10K-0805-5%") (footprint "0805") (libsource (lib "*") (part "RES2")))
    (comp (ref "R8") (value "10K-0805-5%") (footprint "0805") (libsource (lib "*") (part "RES2")))
    (comp (ref "R9") (value "270-0805-5%") (footprint "0805") (libsource (lib "*") (part "RES2")))
    (comp (ref "R12") (value "5.1K-0805-5%") (footprint "0805") (libsource (lib "*") (part "RES2")))
    (comp (ref "R13")
      (value "10K-0805-5%")
      (footprint "0805")
      (description "Resistor")
      (fields (field (name "PUBLISHER") "Altium Limited"))
      (libsource (lib "") (part "Res2_2"))
    )
    (comp (ref "R14")
      (value "1.5K-0805-5%")
      (footprint "0805")
      (description "Resistor")
      (fields (field (name "PUBLISHER") "Altium Limited"))
      (libsource (lib "") (part "Res2_3"))
    )
    (comp (ref "R15") (value "1K-0805-5%") (footprint "0805") (libsource (lib "") (part "RES2_1")))
    (comp (ref "R16") (value "10K-0805-5%") (footprint "0805") (libsource (lib "") (part "RES2_1")))
    (comp (ref "R17") (value "1K-0805-5%") (footprint "0805") (libsource (lib "*") (part "RES2")))
    (comp (ref "R18") (value "1K-0805-5%") (footprint "0805") (libsource (lib "*") (part "RES2")))
    (comp (ref "R19") (value "1K-0805-5%") (footprint "0805") (libsource (lib "*") (part "RES2")))
    (comp (ref "R20") (value "1K-0805-5%") (footprint "0805") (libsource (lib "*") (part "RES2")))
    (comp (ref "R21") (value "1K-0805-5%") (footprint "0805") (libsource (lib "*") (part "RES2")))
    (comp (ref "R22") (value "1K-0805-5%") (footprint "0805") (libsource (lib "*") (part "RES2")))
    (comp (ref "R23") (value "510-0805-5%") (footprint "0805") (libsource (lib "*") (part "RES2")))
    (comp (ref "R24")
      (value "100K-0805-5%")
      (footprint "0805")
      (description "Resistor")
      (fields (field (name "PUBLISHER") "Altium Limited"))
      (libsource (lib "") (part "Res2_1"))
    )
    (comp (ref "R25")
      (value "1K-0805-5%")
      (footprint "0805")
      (description "Resistor")
      (fields (field (name "PUBLISHER") "Altium Limited"))
      (libsource (lib "*") (part "Res2"))
    )
    (comp (ref "R26")
      (value "5.1K-0805-5%")
      (footprint "0805")
      (description "Resistor")
      (fields (field (name "PUBLISHER") "Altium Limited"))
      (libsource (lib "*") (part "Res2"))
    )
    (comp (ref "R27")
      (value "100-0805-5%")
      (footprint "0805")
      (description "Resistor")
      (fields (field (name "PUBLISHER") "Altium Limited"))
      (libsource (lib "*") (part "Res2"))
    )
    (comp (ref "R28")
      (value "5.1K-0805-5%")
      (footprint "0805")
      (description "Resistor")
      (fields (field (name "PUBLISHER") "Altium Limited"))
      (libsource (lib "*") (part "Res2"))
    )
    (comp (ref "R29")
      (value "100-0805-5%")
      (footprint "0805")
      (description "Resistor")
      (fields (field (name "PUBLISHER") "Altium Limited"))
      (libsource (lib "*") (part "Res2"))
    )
    (comp (ref "R30")
      (value "5.1K-0805-5%")
      (footprint "0805")
      (description "Resistor")
      (fields (field (name "PUBLISHER") "Altium Limited"))
      (libsource (lib "*") (part "Res2"))
    )
    (comp (ref "R31")
      (value "1K-0805-5%")
      (footprint "0805")
      (description "Resistor")
      (fields (field (name "PUBLISHER") "Altium Limited"))
      (libsource (lib "*") (part "Res2"))
    )
    (comp (ref "R32")
      (value "5.1K-0805-5%")
      (footprint "0805")
      (description "Resistor")
      (fields (field (name "PUBLISHER") "Altium Limited"))
      (libsource (lib "*") (part "Res2"))
    )
    (comp (ref "R33")
      (value "1K-0805-5%")
      (footprint "0805")
      (description "Resistor")
      (fields (field (name "PUBLISHER") "Altium Limited"))
      (libsource (lib "*") (part "Res2"))
    )
    (comp (ref "R34")
      (value "5.1K-0805-5%")
      (footprint "0805")
      (description "Resistor")
      (fields (field (name "PUBLISHER") "Altium Limited"))
      (libsource (lib "*") (part "Res2"))
    )
    (comp (ref "R35")
      (value "1K-0805-5%")
      (footprint "0805")
      (description "Resistor")
      (fields (field (name "PUBLISHER") "Altium Limited"))
      (libsource (lib "*") (part "Res2"))
    )
    (comp (ref "R36")
      (value "5.1K-0805-5%")
      (footprint "0805")
      (description "Resistor")
      (fields (field (name "PUBLISHER") "Altium Limited"))
      (libsource (lib "*") (part "Res2"))
    )
    (comp (ref "R37")
      (value "1K-0805-5%")
      (footprint "0805")
      (description "Resistor")
      (fields (field (name "PUBLISHER") "Altium Limited"))
      (libsource (lib "*") (part "Res2"))
    )
    (comp (ref "R38")
      (value "5.1K-0805-5%")
      (footprint "0805")
      (description "Resistor")
      (fields (field (name "PUBLISHER") "Altium Limited"))
      (libsource (lib "*") (part "Res2"))
    )
    (comp (ref "R39")
      (value "100-0805-5%")
      (footprint "0805")
      (description "Resistor")
      (fields (field (name "PUBLISHER") "Altium Limited"))
      (libsource (lib "*") (part "Res2"))
    )
    (comp (ref "R40")
      (value "5.1K-0805-5%")
      (footprint "0805")
      (description "Resistor")
      (fields (field (name "PUBLISHER") "Altium Limited"))
      (libsource (lib "*") (part "Res2"))
    )
    (comp (ref "R41")
      (value "100-0805-5%")
      (footprint "0805")
      (description "Resistor")
      (fields (field (name "PUBLISHER") "Altium Limited"))
      (libsource (lib "*") (part "Res2"))
    )
    (comp (ref "R42")
      (value "5.1K-0805-5%")
      (footprint "0805")
      (description "Resistor")
      (fields (field (name "PUBLISHER") "Altium Limited"))
      (libsource (lib "*") (part "Res2"))
    )
    (comp (ref "R43")
      (value "1K-0805-5%")
      (footprint "0805")
      (description "Resistor")
      (fields (field (name "PUBLISHER") "Altium Limited"))
      (libsource (lib "*") (part "Res2"))
    )
    (comp (ref "R44")
      (value "5.1K-0805-5%")
      (footprint "0805")
      (description "Resistor")
      (fields (field (name "PUBLISHER") "Altium Limited"))
      (libsource (lib "*") (part "Res2"))
    )
    (comp (ref "R45")
      (value "1K-0805-5%")
      (footprint "0805")
      (description "Resistor")
      (fields (field (name "PUBLISHER") "Altium Limited"))
      (libsource (lib "*") (part "Res2"))
    )
    (comp (ref "R46")
      (value "5.1K-0805-5%")
      (footprint "0805")
      (description "Resistor")
      (fields (field (name "PUBLISHER") "Altium Limited"))
      (libsource (lib "*") (part "Res2"))
    )
    (comp (ref "R47")
      (value "1K-0805-5%")
      (footprint "0805")
      (description "Resistor")
      (fields (field (name "PUBLISHER") "Altium Limited"))
      (libsource (lib "*") (part "Res2"))
    )
    (comp (ref "R48")
      (value "5.1K-0805-5%")
      (footprint "0805")
      (description "Resistor")
      (fields (field (name "PUBLISHER") "Altium Limited"))
      (libsource (lib "*") (part "Res2"))
    )
    (comp (ref "R49")
      (value "5.1K-0805-5%")
      (footprint "0805")
      (description "Resistor")
      (fields (field (name "PUBLISHER") "Altium Limited"))
      (libsource (lib "") (part "Res2_1"))
    )
    (comp (ref "R50")
      (value "5.1K-0805-5%")
      (footprint "0805")
      (description "Resistor")
      (fields (field (name "PUBLISHER") "Altium Limited"))
      (libsource (lib "") (part "Res2_1"))
    )
    (comp (ref "R51")
      (value "5.1K-0805-5%")
      (footprint "0805")
      (description "Resistor")
      (fields (field (name "PUBLISHER") "Altium Limited"))
      (libsource (lib "") (part "Res2_1"))
    )
    (comp (ref "R52")
      (value "5.1K-0805-5%")
      (footprint "0805")
      (description "Resistor")
      (fields (field (name "PUBLISHER") "Altium Limited"))
      (libsource (lib "") (part "Res2_1"))
    )
    (comp (ref "R53")
      (value "5.1K-0805-5%")
      (footprint "0805")
      (description "Resistor")
      (fields (field (name "PUBLISHER") "Altium Limited"))
      (libsource (lib "") (part "Res2_1"))
    )
    (comp (ref "R54")
      (value "5.1K-0805-5%")
      (footprint "0805")
      (description "Resistor")
      (fields (field (name "PUBLISHER") "Altium Limited"))
      (libsource (lib "") (part "Res2_1"))
    )
    (comp (ref "R55")
      (value "5.1K-0805-5%")
      (footprint "0805")
      (description "Resistor")
      (fields (field (name "PUBLISHER") "Altium Limited"))
      (libsource (lib "") (part "Res2_1"))
    )
    (comp (ref "R56")
      (value "4.7K-0805-5%")
      (footprint "0805")
      (description "Resistor")
      (fields (field (name "PUBLISHER") "Altium Limited"))
      (libsource (lib "Miscellaneous Devices") (part "Res2"))
    )
    (comp (ref "R57")
      (value "4.7K-0805-5%")
      (footprint "0805")
      (description "Resistor")
      (fields (field (name "PUBLISHER") "Altium Limited"))
      (libsource (lib "Miscellaneous Devices") (part "Res2"))
    )
    (comp (ref "R58")
      (value "10K-0805-5%")
      (footprint "0805")
      (description "Resistor")
      (fields (field (name "PUBLISHER") "Altium Limited"))
      (libsource (lib "") (part "Res2_3"))
    )
    (comp (ref "R59")
      (value "1K-0805-5%")
      (footprint "0805")
      (description "Resistor")
      (fields (field (name "PUBLISHER") "Altium Limited"))
      (libsource (lib "") (part "Res2_1"))
    )
    (comp (ref "R60")
      (value "1K-0805-5%")
      (footprint "0805")
      (description "Resistor")
      (fields (field (name "PUBLISHER") "Altium Limited"))
      (libsource (lib "") (part "Res2_1"))
    )
    (comp (ref "R63")
      (value "120-0805-5%")
      (footprint "0805")
      (description "Resistor")
      (fields (field (name "PUBLISHER") "Altium Limited"))
      (libsource (lib "Miscellaneous Devices") (part "Res2"))
    )
    (comp (ref "R64")
      (value "100K-0805-5%")
      (footprint "0805")
      (description "Resistor")
      (fields (field (name "PUBLISHER") "Altium Limited"))
      (libsource (lib "") (part "Res2_1"))
    )
    (comp (ref "R65") (value "5.1K-0805-5%") (footprint "0805") (libsource (lib "*") (part "RES2")))
    (comp (ref "R66") (value "5.1K-0805-5%") (footprint "0805") (libsource (lib "*") (part "RES2")))
    (comp (ref "R67") (value "5.1K-0805-5%") (footprint "0805") (libsource (lib "*") (part "RES2")))
    (comp (ref "R68") (value "5.1K-0805-5%") (footprint "0805") (libsource (lib "*") (part "RES2")))
    (comp (ref "R69") (value "5.1K-0805-5%") (footprint "0805") (libsource (lib "*") (part "RES2")))
    (comp (ref "R70") (value "5.1K-0805-5%") (footprint "0805") (libsource (lib "*") (part "RES2")))
    (comp (ref "R71") (value "5.1K-0805-5%") (footprint "0805") (libsource (lib "*") (part "RES2")))
    (comp (ref "R72") (value "5.1K-0805-5%") (footprint "0805") (libsource (lib "*") (part "RES2")))
    (comp (ref "R73") (value "5.1K-0805-5%") (footprint "0805") (libsource (lib "*") (part "RES2")))
    (comp (ref "R74") (value "5.1K-0805-5%") (footprint "0805") (libsource (lib "*") (part "RES2")))
    (comp (ref "R75") (value "5.1K-0805-5%") (footprint "0805") (libsource (lib "*") (part "RES2")))
    (comp (ref "R76") (value "5.1K-0805-5%") (footprint "0805") (libsource (lib "*") (part "RES2")))
    (comp (ref "R77")
      (value "510-0805-5%")
      (footprint "0805")
      (description "Resistor")
      (fields (field (name "PUBLISHER") "Altium Limited"))
      (libsource (lib "") (part "Res2_1"))
    )
    (comp (ref "R78")
      (value "510-0805-5%")
      (footprint "0805")
      (description "Resistor")
      (fields (field (name "PUBLISHER") "Altium Limited"))
      (libsource (lib "") (part "Res2_1"))
    )
    (comp (ref "R79")
      (value "10K-0805-5%")
      (footprint "0805")
      (description "Resistor")
      (fields (field (name "PUBLISHER") "Altium Limited"))
      (libsource (lib "Miscellaneous Devices") (part "Res2"))
    )
    (comp (ref "R80")
      (value "10K-0805-5%")
      (footprint "0805")
      (description "Resistor")
      (fields (field (name "PUBLISHER") "Altium Limited"))
      (libsource (lib "Miscellaneous Devices") (part "Res2"))
    )
    (comp (ref "R81")
      (value "1K-0805-5%")
      (footprint "0805")
      (description "Resistor")
      (fields (field (name "PUBLISHER") "Altium Limited"))
      (libsource (lib "") (part "Res2_3"))
    )
    (comp (ref "R82")
      (value "1K-0805-5%")
      (footprint "0805")
      (description "Resistor")
      (fields (field (name "PUBLISHER") "Altium Limited"))
      (libsource (lib "") (part "Res2_3"))
    )
    (comp (ref "R83") (value "270-0805-5%") (footprint "0805") (libsource (lib "*") (part "RES2")))
    (comp (ref "R84") (value "270-0805-5%") (footprint "0805") (libsource (lib "*") (part "RES2")))
    (comp (ref "R85")
      (value "10K-0805-5%")
      (footprint "0805")
      (description "Resistor")
      (fields (field (name "PUBLISHER") "Altium Limited"))
      (libsource (lib "Miscellaneous Devices") (part "Res2"))
    )
    (comp (ref "R86")
      (value "10K-0805-5%")
      (footprint "0805")
      (description "Resistor")
      (fields (field (name "PUBLISHER") "Altium Limited"))
      (libsource (lib "Miscellaneous Devices") (part "Res2"))
    )
    (comp (ref "R87") (value "270-0805-5%") (footprint "0805") (libsource (lib "*") (part "RES2")))
    (comp (ref "R88") (value "270-0805-5%") (footprint "0805") (libsource (lib "*") (part "RES2")))
    (comp (ref "R89") (value "270-0805-5%") (footprint "0805") (libsource (lib "*") (part "RES2")))
    (comp (ref "R90") (value "270-0805-5%") (footprint "0805") (libsource (lib "*") (part "RES2")))
    (comp (ref "R91") (value "270-0805-5%") (footprint "0805") (libsource (lib "*") (part "RES2")))
    (comp (ref "R92")
      (value "510-0805-5%")
      (footprint "0805")
      (description "Resistor")
      (fields (field (name "PUBLISHER") "Altium Limited"))
      (libsource (lib "") (part "Res2_1"))
    )
    (comp (ref "R93")
      (value "510-0805-5%")
      (footprint "0805")
      (description "Resistor")
      (fields (field (name "PUBLISHER") "Altium Limited"))
      (libsource (lib "") (part "Res2_1"))
    )
    (comp (ref "R94") (value "10K-0805-5%") (footprint "0805") (libsource (lib "*") (part "RES2")))
    (comp (ref "R95")
      (value "10K-0805-5%")
      (footprint "0805")
      (description "Resistor")
      (fields (field (name "PUBLISHER") "Altium Limited"))
      (libsource (lib "Miscellaneous Devices") (part "Res2"))
    )
    (comp (ref "R96")
      (value "10K-0805-5%")
      (footprint "0805")
      (description "Resistor")
      (fields (field (name "PUBLISHER") "Altium Limited"))
      (libsource (lib "Miscellaneous Devices") (part "Res2"))
    )
    (comp (ref "R97")
      (value "1K-0805-5%")
      (footprint "0805")
      (description "Resistor")
      (fields (field (name "PUBLISHER") "Altium Limited"))
      (libsource (lib "") (part "Res2_3"))
    )
    (comp (ref "R98")
      (value "10K-0805-5%")
      (footprint "0805")
      (description "Resistor")
      (fields (field (name "PUBLISHER") "Altium Limited"))
      (libsource (lib "") (part "Res2_3"))
    )
    (comp (ref "R99") (value "10K-0805-5%") (footprint "0805") (libsource (lib "*") (part "RES2")))
    (comp (ref "R100") (value "10K-0805-5%") (footprint "0805") (libsource (lib "*") (part "RES2")))
    (comp (ref "R101") (value "10K-0805-5%") (footprint "0805") (libsource (lib "*") (part "RES2")))
    (comp (ref "R102")
      (value "10K-0805-5%")
      (footprint "0805")
      (description "Resistor")
      (fields (field (name "PUBLISHER") "Altium Limited"))
      (libsource (lib "Miscellaneous Devices") (part "Res2"))
    )
    (comp (ref "R103")
      (value "10K-0805-5%")
      (footprint "0805")
      (description "Resistor")
      (fields (field (name "PUBLISHER") "Altium Limited"))
      (libsource (lib "Miscellaneous Devices") (part "Res2"))
    )
    (comp (ref "R104") (value "10K-0805-5%") (footprint "0805") (libsource (lib "*") (part "RES2")))
    (comp (ref "R105") (value "10K-0805-5%") (footprint "0805") (libsource (lib "*") (part "RES2")))
    (comp (ref "R106") (value "0R-1206-5%") (footprint "1206") (libsource (lib "*") (part "RES2")))
    (comp (ref "R107") (value "1R5-1206-5%") (footprint "1206") (libsource (lib "*") (part "RES2")))
    (comp (ref "R108") (value "1R5-1206-5%") (footprint "1206") (libsource (lib "*") (part "RES2")))
    (comp (ref "R109")
      (value "510-0805-5%")
      (footprint "0805")
      (description "Resistor")
      (fields (field (name "PUBLISHER") "Altium Limited"))
      (libsource (lib "") (part "Res2_1"))
    )
    (comp (ref "R110")
      (value "10K-0805-5%")
      (footprint "0805")
      (description "Resistor")
      (fields (field (name "PUBLISHER") "Altium Limited"))
      (libsource (lib "Miscellaneous Devices") (part "Res2"))
    )
    (comp (ref "R111") (value "10K-0805-5%") (footprint "0805") (libsource (lib "*") (part "RES2")))
    (comp (ref "R112")
      (value "10K-0805-5%")
      (footprint "0805")
      (description "Resistor")
      (fields (field (name "PUBLISHER") "Altium Limited"))
      (libsource (lib "") (part "Res2_3"))
    )
    (comp (ref "R113") (value "10K-0805-5%") (footprint "0805") (libsource (lib "*") (part "RES2")))
    (comp (ref "R114")
      (value "10K-0805-5%")
      (footprint "0805")
      (description "Resistor")
      (fields (field (name "PUBLISHER") "Altium Limited"))
      (libsource (lib "Miscellaneous Devices") (part "Res2"))
    )
    (comp (ref "R115") (value "0R-1206-5%") (footprint "1206") (libsource (lib "*") (part "RES2")))
    (comp (ref "R116") (value "1K-0805-5%") (footprint "0805") (libsource (lib "") (part "RES2_1")))
    (comp (ref "R117") (value "1K-0805-5%") (footprint "0805") (libsource (lib "") (part "RES2_1")))
    (comp (ref "R118") (value "1K-0805-5%") (footprint "0805") (libsource (lib "*") (part "RES2")))
    (comp (ref "R119")
      (value "RS12-1/8W-1K±5%")
      (footprint "RFID主控板-MFC522:0805R")
      (description "Resistor")
      (fields (field (name "PUBLISHER") "Altium Limited"))
      (libsource (lib "Miscellaneous Devices") (part "Res3"))
    )
    (comp (ref "R120")
      (value "RS12-1/8W-1K±5%")
      (footprint "RFID主控板-MFC522:0805R")
      (description "Resistor")
      (fields (field (name "PUBLISHER") "Altium Limited"))
      (libsource (lib "Miscellaneous Devices") (part "Res3"))
    )
    (comp (ref "R121")
      (value "RS12-1/8W-1K±5%")
      (footprint "RFID主控板-MFC522:0805R")
      (description "Resistor")
      (fields (field (name "PUBLISHER") "Altium Limited"))
      (libsource (lib "Miscellaneous Devices") (part "Res3"))
    )
    (comp (ref "R122")
      (value "RS12-1/8W-1K±5%")
      (footprint "RFID主控板-MFC522:0805R")
      (description "Resistor")
      (fields (field (name "PUBLISHER") "Altium Limited"))
      (libsource (lib "Miscellaneous Devices") (part "Res3"))
    )
    (comp (ref "R124")
      (value "RS12-1/8W-220Ω±5%")
      (footprint "RFID主控板-MFC522:0805R")
      (description "Resistor")
      (fields (field (name "PUBLISHER") "Altium Limited"))
      (libsource (lib "Miscellaneous Devices") (part "Res3"))
    )
    (comp (ref "R125")
      (value "RS12-1/8W-220Ω±5%")
      (footprint "RFID主控板-MFC522:0805R")
      (description "Resistor")
      (fields (field (name "PUBLISHER") "Altium Limited"))
      (libsource (lib "Miscellaneous Devices") (part "Res3"))
    )
    (comp (ref "R126")
      (value "RS12-1/8W-220Ω±5%")
      (footprint "0805R")
      (description "Resistor")
      (fields (field (name "PUBLISHER") "Altium Limited"))
      (libsource (lib "Miscellaneous Devices") (part "Res3"))
    )
    (comp (ref "R127")
      (value "RS12-1/8W-220Ω±5%")
      (footprint "0805R")
      (description "Resistor")
      (fields (field (name "PUBLISHER") "Altium Limited"))
      (libsource (lib "Miscellaneous Devices") (part "Res3"))
    )
    (comp (ref "R129")
      (value "RS12-1/8W-2.7KΩ±1%")
      (footprint "RFID主控板-MFC522:0805R")
      (description "Resistor")
      (fields (field (name "PUBLISHER") "Altium Limited"))
      (libsource (lib "Miscellaneous Devices") (part "Res3"))
    )
    (comp (ref "R130")
      (value "RS12-1/8W-820Ω±1%")
      (footprint "RFID主控板-MFC522:0805R")
      (description "Resistor")
      (fields (field (name "PUBLISHER") "Altium Limited"))
      (libsource (lib "Miscellaneous Devices") (part "Res3"))
    )
    (comp (ref "R131")
      (value "RS12-1/8W-200Ω±1%")
      (footprint "RFID主控板-MFC522:0805R")
      (description "Resistor")
      (fields (field (name "PUBLISHER") "Altium Limited"))
      (libsource (lib "Miscellaneous Devices") (part "Res3"))
    )
    (comp (ref "R132")
      (value "RS12-1/8W-10KΩ±5%")
      (footprint "RFID主控板-MFC522:0805R")
      (description "Resistor")
      (fields (field (name "PUBLISHER") "Altium Limited"))
      (libsource (lib "Miscellaneous Devices") (part "Res3"))
    )
    (comp (ref "U1")
      (value "HXO-36B-8MHZ-7.0*5.0*1.5-SMD")
      (footprint "OSC_4_S")
      (libsource (lib "*") (part "CRYSTAL"))
    )
    (comp (ref "U2")
      (value "LM2576-5")
      (footprint "TO-263")
      (description "TO-263")
      (libsource (lib "SilvestStandardSchLib") (part "LM2576"))
    )
    (comp (ref "U3") (value "MAX3485") (footprint "PcbLib1:SOP8") (libsource (lib "*") (part "MAX3485")))
    (comp (ref "U5")
      (value "STM32F103VET6")
      (footprint "LQFP100_N")
      (libsource (lib "STM32") (part "STM32F103VET6"))
    )
    (comp (ref "U6")
      (value "LM1117MPX-3.3")
      (footprint "SOT-223-3L")
      (libsource (lib "PCB_Project1") (part "LM1117MPX-3.3"))
    )
    (comp (ref "U7") (value "W25Q64") (footprint "SO-8M") (libsource (lib "*") (part "W25Q64")))
    (comp (ref "U8") (value "IRF7404PBF") (footprint "SO-8") (libsource (lib "*") (part "sop8(IRF7404)")))
    (comp (ref "U9")
      (value "ULN2003A")
      (footprint "SO-16")
      (description "Darlinton BJT Array")
      (libsource (lib "SilvestStandardSchLib") (part "ULN2003"))
    )
    (comp (ref "U11") (value "MAX3232ESE") (footprint "SOIC-16") (libsource (lib "*") (part "SPI3232E")))
    (comp (ref "U12") (value "MAX3232ESE") (footprint "SOIC-16") (libsource (lib "*") (part "SPI3232E")))
    (comp (ref "U14")
      (value "74HC14D")
      (footprint "SO-14")
      (description "Hex Inverters")
      (libsource (lib "SilvestStandardSchLib") (part "74HC04"))
    )
    (comp (ref "U15")
      (value "74HC14D")
      (footprint "SO-14")
      (description "Hex Inverters")
      (libsource (lib "SilvestStandardSchLib") (part "74HC04"))
    )
    (comp (ref "U16") (value "L298P") (footprint "POWERSO20_N") (libsource (lib "*") (part "L298P")))
    (comp (ref "U17")
      (value "LM393AD")
      (footprint "SO-8")
      (description "Low-Power Dual Voltage Comparator")
      (fields (field (name "PUBLISHER") "Altium Limited"))
      (libsource (lib "*") (part "LM393AD"))
    )
    (comp (ref "U18")
      (value "AQY221N2S(NAIS)")
      (footprint "SOP-4")
      (description "OpticalCoupler")
      (libsource (lib "PCB_Project1_1") (part "OpticalCoupler"))
    )
    (comp (ref "U19")
      (value "AQY221N2S(NAIS)")
      (footprint "SOP-4")
      (description "OpticalCoupler")
      (libsource (lib "PCB_Project1_1") (part "OpticalCoupler"))
    )
    (comp (ref "U20")
      (value "AQY221N2S(NAIS)")
      (footprint "SOP-4")
      (description "OpticalCoupler")
      (libsource (lib "PCB_Project1_1") (part "OpticalCoupler"))
    )
    (comp (ref "U21")
      (value "AQY221N2S(NAIS)")
      (footprint "SOP-4")
      (description "OpticalCoupler")
      (libsource (lib "PCB_Project1_1") (part "OpticalCoupler"))
    )
    (comp (ref "U23")
      (value "MFRC522")
      (footprint "RFID主控板-MFC522:QFN-32")
      (libsource (lib "PCB_Project2") (part "RC522"))
    )
    (comp (ref "Y1")
      (value "27.120MHz")
      (footprint "PcbLib1:XTAL")
      (description "Crystal Oscillator")
      (fields (field (name "PUBLISHER") "Altium Limited"))
      (libsource (lib "Miscellaneous Devices") (part "XTAL"))
    )
  )
  (nets
    (net (code "1") (name "+5V") (class "Default")
      (node (ref "C16") (pin "1") (pinfunction "1_1") (pintype "passive"))
      (node (ref "C19") (pin "1") (pinfunction "1_1") (pintype "passive"))
      (node (ref "C62") (pin "1") (pinfunction "1_1") (pintype "passive"))
      (node (ref "C63") (pin "1") (pinfunction "1_1") (pintype "passive"))
      (node (ref "C65") (pin "1") (pinfunction "1_1") (pintype "passive"))
      (node (ref "J4") (pin "10") (pinfunction "10_10") (pintype "passive"))
      (node (ref "J4") (pin "16") (pinfunction "16_16") (pintype "passive"))
      (node (ref "J4") (pin "4") (pinfunction "4_4") (pintype "passive"))
      (node (ref "J5") (pin "10") (pinfunction "10_10") (pintype "passive"))
      (node (ref "J5") (pin "16") (pinfunction "16_16") (pintype "passive"))
      (node (ref "J5") (pin "4") (pinfunction "4_4") (pintype "passive"))
      (node (ref "J6") (pin "10") (pinfunction "10_10") (pintype "passive"))
      (node (ref "J6") (pin "16") (pinfunction "16_16") (pintype "passive"))
      (node (ref "J6") (pin "4") (pinfunction "4_4") (pintype "passive"))
      (node (ref "J8") (pin "10") (pinfunction "10_10") (pintype "passive"))
      (node (ref "J8") (pin "16") (pinfunction "16_16") (pintype "passive"))
      (node (ref "J8") (pin "4") (pinfunction "4_4") (pintype "passive"))
      (node (ref "L1") (pin "2") (pinfunction "2_2") (pintype "passive"))
      (node (ref "R104") (pin "1") (pinfunction "1_1") (pintype "passive"))
      (node (ref "R105") (pin "1") (pinfunction "1_1") (pintype "passive"))
      (node (ref "R113") (pin "1") (pinfunction "1_1") (pintype "passive"))
      (node (ref "R12") (pin "1") (pinfunction "1_1") (pintype "passive"))
      (node (ref "R14") (pin "1") (pinfunction "1_1") (pintype "passive"))
      (node (ref "R26") (pin "1") (pinfunction "1_1") (pintype "passive"))
      (node (ref "R28") (pin "1") (pinfunction "1_1") (pintype "passive"))
      (node (ref "R30") (pin "1") (pinfunction "1_1") (pintype "passive"))
      (node (ref "R32") (pin "1") (pinfunction "1_1") (pintype "passive"))
      (node (ref "R34") (pin "1") (pinfunction "1_1") (pintype "passive"))
      (node (ref "R36") (pin "1") (pinfunction "1_1") (pintype "passive"))
      (node (ref "R38") (pin "1") (pinfunction "1_1") (pintype "passive"))
      (node (ref "R40") (pin "1") (pinfunction "1_1") (pintype "passive"))
      (node (ref "R42") (pin "1") (pinfunction "1_1") (pintype "passive"))
      (node (ref "R44") (pin "1") (pinfunction "1_1") (pintype "passive"))
      (node (ref "R46") (pin "1") (pinfunction "1_1") (pintype "passive"))
      (node (ref "R48") (pin "1") (pinfunction "1_1") (pintype "passive"))
      (node (ref "U14") (pin "14") (pinfunction "VCC_14") (pintype "passive"))
      (node (ref "U15") (pin "14") (pinfunction "VCC_14") (pintype "passive"))
      (node (ref "U16") (pin "12") (pinfunction "VCC_12") (pintype "passive"))
      (node (ref "U17") (pin "8") (pinfunction "V+_8") (pintype "power_in"))
      (node (ref "U2") (pin "4") (pinfunction "FB_4") (pintype "passive"))
      (node (ref "U6") (pin "3") (pinfunction "Vin_3") (pintype "passive"))
      (node (ref "U8") (pin "1") (pinfunction "S_1") (pintype "passive"))
      (node (ref "U8") (pin "2") (pinfunction "S_2") (pintype "passive"))
      (node (ref "U8") (pin "3") (pinfunction "S_3") (pintype "passive"))
    )
    (net (code "2") (name "/+24V") (class "Default")
      (node (ref "C17") (pin "1") (pinfunction "1_1") (pintype "passive"))
      (node (ref "C4") (pin "1") (pinfunction "1_1") (pintype "passive"))
      (node (ref "C8") (pin "1") (pinfunction "1_1") (pintype "passive"))
      (node (ref "D11") (pin "2") (pinfunction "K_2") (pintype "passive"))
      (node (ref "D13") (pin "2") (pinfunction "K_2") (pintype "passive"))
      (node (ref "J1") (pin "10") (pinfunction "10_10") (pintype "passive"))
      (node (ref "J1") (pin "12") (pinfunction "12_12") (pintype "passive"))
      (node (ref "J1") (pin "14") (pinfunction "14_14") (pintype "passive"))
      (node (ref "J1") (pin "16") (pinfunction "16_16") (pintype "passive"))
      (node (ref "J1") (pin "2") (pinfunction "2_2") (pintype "passive"))
      (node (ref "J1") (pin "4") (pinfunction "4_4") (pintype "passive"))
      (node (ref "J1") (pin "6") (pinfunction "6_6") (pintype "passive"))
      (node (ref "J1") (pin "8") (pinfunction "8_8") (pintype "passive"))
      (node (ref "R115") (pin "2") (pinfunction "2_2") (pintype "passive"))
      (node (ref "R16") (pin "1") (pinfunction "1_1") (pintype "passive"))
      (node (ref "R49") (pin "2") (pinfunction "2_2") (pintype "passive"))
      (node (ref "R50") (pin "2") (pinfunction "2_2") (pintype "passive"))
      (node (ref "R51") (pin "2") (pinfunction "2_2") (pintype "passive"))
      (node (ref "R52") (pin "2") (pinfunction "2_2") (pintype "passive"))
      (node (ref "R53") (pin "2") (pinfunction "2_2") (pintype "passive"))
      (node (ref "R54") (pin "2") (pinfunction "2_2") (pintype "passive"))
      (node (ref "R55") (pin "2") (pinfunction "2_2") (pintype "passive"))
      (node (ref "U2") (pin "1") (pinfunction "IN_1") (pintype "passive"))
    )
    (net (code "3") (name "/+24VA") (class "Default")
      (node (ref "C10") (pin "1") (pinfunction "1_1") (pintype "passive"))
      (node (ref "C13") (pin "1") (pinfunction "1_1") (pintype "passive"))
      (node (ref "C15") (pin "1") (pinfunction "1_1") (pintype "passive"))
      (node (ref "C67") (pin "1") (pinfunction "1_1") (pintype "passive"))
      (node (ref "D39") (pin "K") (pinfunction "K_K") (pintype "passive"))
      (node (ref "D40") (pin "K") (pinfunction "K_K") (pintype "passive"))
      (node (ref "D41") (pin "K") (pinfunction "K_K") (pintype "passive"))
      (node (ref "D42") (pin "K") (pinfunction "K_K") (pintype "passive"))
      (node (ref "D43") (pin "K") (pinfunction "K_K") (pintype "passive"))
      (node (ref "J14") (pin "1") (pinfunction "1_1") (pintype "passive"))
      (node (ref "J15") (pin "1") (pinfunction "1_1") (pintype "passive"))
      (node (ref "J16") (pin "1") (pinfunction "1_1") (pintype "passive"))
      (node (ref "J17") (pin "1") (pinfunction "1_1") (pintype "passive"))
      (node (ref "J19") (pin "1") (pinfunction "1_1") (pintype "passive"))
      (node (ref "Q10") (pin "2") (pintype "passive"))
      (node (ref "Q7") (pin "2") (pintype "passive"))
      (node (ref "Q8") (pin "2") (pintype "passive"))
      (node (ref "Q9") (pin "2") (pintype "passive"))
      (node (ref "R102") (pin "1") (pinfunction "1_1") (pintype "passive"))
      (node (ref "R103") (pin "1") (pinfunction "1_1") (pintype "passive"))
      (node (ref "R114") (pin "1") (pinfunction "1_1") (pintype "passive"))
      (node (ref "R115") (pin "1") (pinfunction "1_1") (pintype "passive"))
      (node (ref "R85") (pin "1") (pinfunction "1_1") (pintype "passive"))
      (node (ref "R86") (pin "1") (pinfunction "1_1") (pintype "passive"))
      (node (ref "U16") (pin "6") (pinfunction "Vhi_6") (pintype "passive"))
    )
    (net (code "4") (name "/+24VIN") (class "Default")
      (node (ref "F1") (pin "1") (pinfunction "1_1") (pintype "passive"))
      (node (ref "J2") (pin "1") (pinfunction "1_1") (pintype "passive"))
      (node (ref "J2") (pin "3") (pinfunction "3_3") (pintype "passive"))
      (node (ref "J3") (pin "1") (pinfunction "1_1") (pintype "passive"))
      (node (ref "J3") (pin "3") (pinfunction "3_3") (pintype "passive"))
    )
    (net (code "5") (name "/5V_LED") (class "Default")
      (node (ref "R25") (pin "1") (pinfunction "1_1") (pintype "passive"))
      (node (ref "R27") (pin "1") (pinfunction "1_1") (pintype "passive"))
      (node (ref "R29") (pin "1") (pinfunction "1_1") (pintype "passive"))
      (node (ref "R31") (pin "1") (pinfunction "1_1") (pintype "passive"))
      (node (ref "R33") (pin "1") (pinfunction "1_1") (pintype "passive"))
      (node (ref "R35") (pin "1") (pinfunction "1_1") (pintype "passive"))
      (node (ref "R37") (pin "1") (pinfunction "1_1") (pintype "passive"))
      (node (ref "R39") (pin "1") (pinfunction "1_1") (pintype "passive"))
      (node (ref "R41") (pin "1") (pinfunction "1_1") (pintype "passive"))
      (node (ref "R43") (pin "1") (pinfunction "1_1") (pintype "passive"))
      (node (ref "R45") (pin "1") (pinfunction "1_1") (pintype "passive"))
      (node (ref "R47") (pin "1") (pinfunction "1_1") (pintype "passive"))
      (node (ref "U8") (pin "5") (pinfunction "D_5") (pintype "passive"))
      (node (ref "U8") (pin "6") (pinfunction "D_6") (pintype "passive"))
      (node (ref "U8") (pin "7") (pinfunction "D_7") (pintype "passive"))
      (node (ref "U8") (pin "8") (pinfunction "D_8") (pintype "passive"))
    )
    (net (code "6") (name "/485_A") (class "Default")
      (node (ref "J13") (pin "2") (pinfunction "2_2") (pintype "passive"))
      (node (ref "R57") (pin "1") (pinfunction "1_1") (pintype "passive"))
      (node (ref "R63") (pin "2") (pinfunction "2_2") (pintype "passive"))
      (node (ref "U3") (pin "6") (pinfunction "A_6") (pintype "passive"))
    )
    (net (code "7") (name "/485_B") (class "Default")
      (node (ref "J13") (pin "1") (pinfunction "1_1") (pintype "passive"))
      (node (ref "R56") (pin "2") (pinfunction "2_2") (pintype "passive"))
      (node (ref "R63") (pin "1") (pinfunction "1_1") (pintype "passive"))
      (node (ref "U3") (pin "7") (pinfunction "B_7") (pintype "passive"))
    )
    (net (code "8") (name "/485_EN") (class "Default")
      (node (ref "R58") (pin "2") (pinfunction "2_2") (pintype "passive"))
      (node (ref "U3") (pin "2") (pinfunction "/RE_2") (pintype "passive"))
      (node (ref "U3") (pin "3") (pinfunction "DE_3") (pintype "passive"))
      (node (ref "U5") (pin "84") (pinfunction "PD3_84") (pintype "passive"))
    )
    (net (code "9") (name "/AVDD") (class "Default")
      (node (ref "C84") (pin "2") (pinfunction "2_2") (pintype "passive"))
      (node (ref "C85") (pin "2") (pinfunction "2_2") (pintype "passive"))
      (node (ref "L4") (pin "2") (pinfunction "2_2") (pintype "passive"))
      (node (ref "U23") (pin "15") (pinfunction "AVDD_15") (pintype "passive"))
    )
    (net (code "10") (name "/BOOT0") (class "Default")
      (node (ref "R64") (pin "2") (pinfunction "2_2") (pintype "passive"))
      (node (ref "U5") (pin "94") (pinfunction "BOOT0_94") (pintype "passive"))
    )
    (net (code "11") (name "/BOOT1") (class "Default")
      (node (ref "R24") (pin "2") (pinfunction "2_2") (pintype "passive"))
      (node (ref "U5") (pin "37") (pinfunction "PB2_37") (pintype "passive"))
    )
    (net (code "12") (name "/CLK_IN") (class "Default")
      (node (ref "U1") (pin "3") (pinfunction "CLK_3") (pintype "passive"))
      (node (ref "U5") (pin "12") (pinfunction "OSC_IN_12") (pintype "passive"))
    )
    (net (code "13") (name "/DVDD") (class "Default")
      (node (ref "C73") (pin "2") (pinfunction "2_2") (pintype "passive"))
      (node (ref "C76") (pin "2") (pinfunction "2_2") (pintype "passive"))
      (node (ref "L7") (pin "2") (pinfunction "2_2") (pintype "passive"))
      (node (ref "U23") (pin "2") (pinfunction "PVDD_2") (pintype "passive"))
      (node (ref "U23") (pin "3") (pinfunction "DVDD_3") (pintype "passive"))
    )
    (net (code "14") (name "/FLASH_CS") (class "Default")
      (node (ref "U5") (pin "29") (pinfunction "PA4_29") (pintype "passive"))
      (node (ref "U7") (pin "1") (pinfunction "CS_1") (pintype "passive"))
    )
    (net (code "15") (name "/G1") (class "Default")
      (node (ref "D54") (pin "2") (pinfunction "K_2") (pintype "passive"))
      (node (ref "U18") (pin "2") (pinfunction "K_2") (pintype "passive"))
      (node (ref "U5") (pin "33") (pinfunction "PC4_33") (pintype "passive"))
    )
    (net (code "16") (name "/G2") (class "Default")
      (node (ref "D55") (pin "2") (pinfunction "K_2") (pintype "passive"))
      (node (ref "U19") (pin "2") (pinfunction "K_2") (pintype "passive"))
      (node (ref "U5") (pin "34") (pinfunction "PC5_34") (pintype "passive"))
    )
    (net (code "17") (name "/G3") (class "Default")
      (node (ref "D56") (pin "2") (pinfunction "K_2") (pintype "passive"))
      (node (ref "U20") (pin "2") (pinfunction "K_2") (pintype "passive"))
      (node (ref "U5") (pin "35") (pinfunction "PB0_35") (pintype "passive"))
    )
    (net (code "18") (name "/G4") (class "Default")
      (node (ref "D57") (pin "2") (pinfunction "K_2") (pintype "passive"))
      (node (ref "U21") (pin "2") (pinfunction "K_2") (pintype "passive"))
      (node (ref "U5") (pin "82") (pinfunction "PD1_82") (pintype "passive"))
    )
    (net (code "19") (name "/G5") (class "Default")
      (node (ref "U5") (pin "81") (pinfunction "PD0_81") (pintype "passive"))
    )
    (net (code "20") (name "/IN1") (class "Default")
      (node (ref "C21") (pin "2") (pinfunction "2_2") (pintype "passive"))
      (node (ref "D2") (pin "2") (pinfunction "K_2") (pintype "passive"))
      (node (ref "D44") (pin "A") (pinfunction "A_A") (pintype "passive"))
      (node (ref "R1") (pin "2") (pinfunction "2_2") (pintype "passive"))
      (node (ref "U5") (pin "85") (pinfunction "PD4_85") (pintype "passive"))
    )
    (net (code "21") (name "/IN2") (class "Default")
      (node (ref "C22") (pin "2") (pinfunction "2_2") (pintype "passive"))
      (node (ref "D3") (pin "2") (pinfunction "K_2") (pintype "passive"))
      (node (ref "D45") (pin "A") (pinfunction "A_A") (pintype "passive"))
      (node (ref "R2") (pin "2") (pinfunction "2_2") (pintype "passive"))
      (node (ref "U5") (pin "86") (pinfunction "PD5_86") (pintype "passive"))
    )
    (net (code "22") (name "/IN3") (class "Default")
      (node (ref "C23") (pin "2") (pinfunction "2_2") (pintype "passive"))
      (node (ref "D4") (pin "2") (pinfunction "K_2") (pintype "passive"))
      (node (ref "D46") (pin "A") (pinfunction "A_A") (pintype "passive"))
      (node (ref "R3") (pin "2") (pinfunction "2_2") (pintype "passive"))
      (node (ref "U5") (pin "87") (pinfunction "PD6_87") (pintype "passive"))
    )
    (net (code "23") (name "/IN4") (class "Default")
      (node (ref "C24") (pin "2") (pinfunction "2_2") (pintype "passive"))
      (node (ref "D47") (pin "A") (pinfunction "A_A") (pintype "passive"))
      (node (ref "D5") (pin "2") (pinfunction "K_2") (pintype "passive"))
      (node (ref "R4") (pin "2") (pinfunction "2_2") (pintype "passive"))
      (node (ref "U5") (pin "88") (pinfunction "PD7_88") (pintype "passive"))
    )
    (net (code "24") (name "/IN5") (class "Default")
      (node (ref "C25") (pin "2") (pinfunction "2_2") (pintype "passive"))
      (node (ref "D48") (pin "A") (pinfunction "A_A") (pintype "passive"))
      (node (ref "D6") (pin "2") (pinfunction "K_2") (pintype "passive"))
      (node (ref "R5") (pin "2") (pinfunction "2_2") (pintype "passive"))
      (node (ref "U5") (pin "91") (pinfunction "PB5_91") (pintype "passive"))
    )
    (net (code "25") (name "/IN6") (class "Default")
      (node (ref "C27") (pin "2") (pinfunction "2_2") (pintype "passive"))
      (node (ref "D49") (pin "A") (pinfunction "A_A") (pintype "passive"))
      (node (ref "D7") (pin "2") (pinfunction "K_2") (pintype "passive"))
      (node (ref "R6") (pin "2") (pinfunction "2_2") (pintype "passive"))
      (node (ref "U5") (pin "92") (pinfunction "PB6_92") (pintype "passive"))
    )
    (net (code "26") (name "/MOTOR1+") (class "Default")
      (node (ref "J18") (pin "4") (pinfunction "4_4") (pintype "passive"))
      (node (ref "Q10") (pin "3") (pintype "passive"))
      (node (ref "U16") (pin "4") (pinfunction "OUT1_4") (pintype "passive"))
    )
    (net (code "27") (name "/MOTOR1-") (class "Default")
      (node (ref "J18") (pin "3") (pinfunction "3_3") (pintype "passive"))
      (node (ref "Q7") (pin "3") (pintype "passive"))
      (node (ref "U16") (pin "5") (pinfunction "OUT2_5") (pintype "passive"))
    )
    (net (code "28") (name "/MOTOR2+") (class "Default")
      (node (ref "J18") (pin "2") (pinfunction "2_2") (pintype "passive"))
      (node (ref "Q8") (pin "3") (pintype "passive"))
      (node (ref "U16") (pin "16") (pinfunction "OUT3_16") (pintype "passive"))
    )
    (net (code "29") (name "/MOTOR2-") (class "Default")
      (node (ref "J18") (pin "1") (pinfunction "1_1") (pintype "passive"))
      (node (ref "Q9") (pin "3") (pintype "passive"))
      (node (ref "U16") (pin "17") (pinfunction "OUT4_17") (pintype "passive"))
    )
    (net (code "30") (name "/MOTOR_1F+") (class "Default")
      (node (ref "R94") (pin "2") (pinfunction "2_2") (pintype "passive"))
      (node (ref "U16") (pin "7") (pinfunction "IN1_7") (pintype "passive"))
      (node (ref "U5") (pin "3") (pinfunction "PE4_3") (pintype "passive"))
    )
    (net (code "31") (name "/MOTOR_1F-") (class "Default")
      (node (ref "R99") (pin "2") (pinfunction "2_2") (pintype "passive"))
      (node (ref "U16") (pin "9") (pinfunction "IN2_9") (pintype "passive"))
      (node (ref "U5") (pin "4") (pinfunction "PE5_4") (pintype "passive"))
    )
    (net (code "32") (name "/MOTOR_2F+") (class "Default")
      (node (ref "R100") (pin "2") (pinfunction "2_2") (pintype "passive"))
      (node (ref "U16") (pin "13") (pinfunction "IN3_13") (pintype "passive"))
      (node (ref "U5") (pin "7") (pinfunction "PC13-TAMPER-RTC_7") (pintype "passive"))
    )
    (net (code "33") (name "/MOTOR_2F-") (class "Default")
      (node (ref "R101") (pin "2") (pinfunction "2_2") (pintype "passive"))
      (node (ref "U16") (pin "15") (pinfunction "IN4_15") (pintype "passive"))
      (node (ref "U5") (pin "5") (pinfunction "PE6_5") (pintype "passive"))
    )
    (net (code "34") (name "/NSRST") (class "Default")
      (node (ref "C2") (pin "2") (pinfunction "2_2") (pintype "passive"))
      (node (ref "J7") (pin "15") (pinfunction "NSRST_15") (pintype "passive"))
      (node (ref "K3") (pin "2") (pinfunction "2_2") (pintype "passive"))
      (node (ref "R13") (pin "1") (pinfunction "1_1") (pintype "passive"))
      (node (ref "U5") (pin "14") (pinfunction "NRST_14") (pintype "passive"))
    )
    (net (code "35") (name "/NTRST") (class "Default")
      (node (ref "J7") (pin "3") (pinfunction "NTRST_3") (pintype "passive"))
      (node (ref "U5") (pin "90") (pinfunction "PB4_90") (pintype "passive"))
    )
    (net (code "36") (name "/OUT1") (class "Default")
      (node (ref "U5") (pin "44") (pinfunction "PE13_44") (pintype "passive"))
      (node (ref "U9") (pin "1") (pinfunction "IN1_1") (pintype "passive"))
    )
    (net (code "37") (name "/OUT2") (class "Default")
      (node (ref "U5") (pin "43") (pinfunction "PE12_43") (pintype "passive"))
      (node (ref "U9") (pin "2") (pinfunction "IN2_2") (pintype "passive"))
    )
    (net (code "38") (name "/OUT3") (class "Default")
      (node (ref "U5") (pin "42") (pinfunction "PE11_42") (pintype "passive"))
      (node (ref "U9") (pin "3") (pinfunction "IN3_3") (pintype "passive"))
    )
    (net (code "39") (name "/OUT4") (class "Default")
      (node (ref "U5") (pin "41") (pinfunction "PE10_41") (pintype "passive"))
      (node (ref "U9") (pin "4") (pinfunction "IN4_4") (pintype "passive"))
    )
    (net (code "40") (name "/OUT5") (class "Default")
      (node (ref "U5") (pin "40") (pinfunction "PE9_40") (pintype "passive"))
      (node (ref "U9") (pin "5") (pinfunction "IN5_5") (pintype "passive"))
    )
    (net (code "41") (name "/OUT6") (class "Default")
      (node (ref "U5") (pin "39") (pinfunction "PE8_39") (pintype "passive"))
      (node (ref "U9") (pin "6") (pinfunction "IN6_6") (pintype "passive"))
    )
    (net (code "42") (name "/OUT7") (class "Default")
      (node (ref "U5") (pin "38") (pinfunction "PE7_38") (pintype "passive"))
      (node (ref "U9") (pin "7") (pinfunction "IN7_7") (pintype "passive"))
    )
    (net (code "43") (name "/OUT_1") (class "Default")
      (node (ref "D14") (pin "2") (pinfunction "K_2") (pintype "passive"))
      (node (ref "J1") (pin "1") (pinfunction "1_1") (pintype "passive"))
      (node (ref "U9") (pin "16") (pinfunction "OUT1_16") (pintype "passive"))
    )
    (net (code "44") (name "/OUT_2") (class "Default")
      (node (ref "D16") (pin "2") (pinfunction "K_2") (pintype "passive"))
      (node (ref "J1") (pin "3") (pinfunction "3_3") (pintype "passive"))
      (node (ref "U9") (pin "15") (pinfunction "OUT2_15") (pintype "passive"))
    )
    (net (code "45") (name "/OUT_3") (class "Default")
      (node (ref "D17") (pin "2") (pinfunction "K_2") (pintype "passive"))
      (node (ref "J1") (pin "5") (pinfunction "5_5") (pintype "passive"))
      (node (ref "U9") (pin "14") (pinfunction "OUT3_14") (pintype "passive"))
    )
    (net (code "46") (name "/OUT_4") (class "Default")
      (node (ref "D18") (pin "2") (pinfunction "K_2") (pintype "passive"))
      (node (ref "J1") (pin "7") (pinfunction "7_7") (pintype "passive"))
      (node (ref "U9") (pin "13") (pinfunction "OUT4_13") (pintype "passive"))
    )
    (net (code "47") (name "/OUT_5") (class "Default")
      (node (ref "D19") (pin "2") (pinfunction "K_2") (pintype "passive"))
      (node (ref "J1") (pin "9") (pinfunction "9_9") (pintype "passive"))
      (node (ref "U9") (pin "12") (pinfunction "OUT5_12") (pintype "passive"))
    )
    (net (code "48") (name "/OUT_6") (class "Default")
      (node (ref "D20") (pin "2") (pinfunction "K_2") (pintype "passive"))
      (node (ref "J1") (pin "11") (pinfunction "11_11") (pintype "passive"))
      (node (ref "U9") (pin "11") (pinfunction "OUT6_11") (pintype "passive"))
    )
    (net (code "49") (name "/OUT_7") (class "Default")
      (node (ref "D21") (pin "2") (pinfunction "K_2") (pintype "passive"))
      (node (ref "J1") (pin "13") (pinfunction "13_13") (pintype "passive"))
      (node (ref "U9") (pin "10") (pinfunction "OUT7_10") (pintype "passive"))
    )
    (net (code "50") (name "/RFID") (class "Default")
      (node (ref "C87") (pin "2") (pinfunction "2_2") (pintype "passive"))
      (node (ref "C88") (pin "2") (pinfunction "2_2") (pintype "passive"))
      (node (ref "C91") (pin "2") (pinfunction "2_2") (pintype "passive"))
      (node (ref "U18") (pin "4") (pinfunction "C_4") (pintype "passive"))
      (node (ref "U19") (pin "4") (pinfunction "C_4") (pintype "passive"))
      (node (ref "U20") (pin "4") (pinfunction "C_4") (pintype "passive"))
      (node (ref "U21") (pin "4") (pinfunction "C_4") (pintype "passive"))
    )
    (net (code "51") (name "/RST") (class "Default")
      (node (ref "R132") (pin "2") (pinfunction "2_2") (pintype "passive"))
      (node (ref "U23") (pin "6") (pinfunction "/RST_6") (pintype "passive"))
      (node (ref "U5") (pin "36") (pinfunction "PB1_36") (pintype "passive"))
    )
    (net (code "52") (name "/RX") (class "Default")
      (node (ref "R129") (pin "1") (pinfunction "1_1") (pintype "passive"))
      (node (ref "R130") (pin "1") (pinfunction "1_1") (pintype "passive"))
      (node (ref "U23") (pin "17") (pinfunction "RX_17") (pintype "passive"))
    )
    (net (code "53") (name "/RXD1") (class "Default")
      (node (ref "D52") (pin "2") (pinfunction "K_2") (pintype "passive"))
      (node (ref "U12") (pin "9") (pinfunction "R2OUT_9") (pintype "passive"))
      (node (ref "U3") (pin "1") (pinfunction "RO_1") (pintype "passive"))
      (node (ref "U5") (pin "69") (pinfunction "PA10_69") (pintype "passive"))
    )
    (net (code "54") (name "/RXD2") (class "Default")
      (node (ref "U11") (pin "12") (pinfunction "R1OUT_12") (pintype "passive"))
      (node (ref "U5") (pin "26") (pinfunction "PA3_26") (pintype "passive"))
    )
    (net (code "55") (name "/RXD3") (class "Default")
      (node (ref "U11") (pin "9") (pinfunction "R2OUT_9") (pintype "passive"))
      (node (ref "U5") (pin "48") (pinfunction "PB11_48") (pintype "passive"))
    )
    (net (code "56") (name "/RXD4") (class "Default")
      (node (ref "U5") (pin "79") (pinfunction "PC11_79") (pintype "passive"))
    )
    (net (code "57") (name "/RXD5") (class "Default")
      (node (ref "U5") (pin "83") (pinfunction "PD2_83") (pintype "passive+no_connect"))
    )
    (net (code "58") (name "/RXD_M1") (class "Default")
      (node (ref "J10") (pin "2") (pinfunction "2_2") (pintype "passive"))
      (node (ref "U12") (pin "7") (pinfunction "T2OUT_7") (pintype "passive"))
    )
    (net (code "59") (name "/RXD_M2") (class "Default")
      (node (ref "J9") (pin "5") (pinfunction "5_5") (pintype "passive"))
      (node (ref "U11") (pin "14") (pinfunction "T1OUT_14") (pintype "passive"))
    )
    (net (code "60") (name "/RXD_M3") (class "Default")
      (node (ref "J9") (pin "2") (pinfunction "2_2") (pintype "passive"))
      (node (ref "U11") (pin "7") (pinfunction "T2OUT_7") (pintype "passive"))
    )
    (net (code "61") (name "/SENS1") (class "Default")
      (node (ref "R65") (pin "1") (pinfunction "1_1") (pintype "passive"))
      (node (ref "U14") (pin "12") (pinfunction "6Y_12") (pintype "passive"))
      (node (ref "U5") (pin "67") (pinfunction "PA8_67") (pintype "passive"))
    )
    (net (code "62") (name "/SENS2") (class "Default")
      (node (ref "R66") (pin "1") (pinfunction "1_1") (pintype "passive"))
      (node (ref "U14") (pin "10") (pinfunction "5Y_10") (pintype "passive"))
      (node (ref "U5") (pin "66") (pinfunction "PC9_66") (pintype "passive"))
    )
    (net (code "63") (name "/SENS3") (class "Default")
      (node (ref "R67") (pin "1") (pinfunction "1_1") (pintype "passive"))
      (node (ref "U14") (pin "8") (pinfunction "4Y_8") (pintype "passive"))
      (node (ref "U5") (pin "65") (pinfunction "PC8_65") (pintype "passive"))
    )
    (net (code "64") (name "/SENS4") (class "Default")
      (node (ref "R68") (pin "1") (pinfunction "1_1") (pintype "passive"))
      (node (ref "U14") (pin "6") (pinfunction "3Y_6") (pintype "passive"))
      (node (ref "U5") (pin "64") (pinfunction "PC7_64") (pintype "passive"))
    )
    (net (code "65") (name "/SENS5") (class "Default")
      (node (ref "R69") (pin "1") (pinfunction "1_1") (pintype "passive"))
      (node (ref "U14") (pin "4") (pinfunction "2Y_4") (pintype "passive"))
      (node (ref "U5") (pin "63") (pinfunction "PC6_63") (pintype "passive"))
    )
    (net (code "66") (name "/SENS6") (class "Default")
      (node (ref "R70") (pin "1") (pinfunction "1_1") (pintype "passive"))
      (node (ref "U14") (pin "2") (pinfunction "1Y_2") (pintype "passive"))
      (node (ref "U5") (pin "62") (pinfunction "PD15_62") (pintype "passive"))
    )
    (net (code "67") (name "/SENS7") (class "Default")
      (node (ref "R71") (pin "1") (pinfunction "1_1") (pintype "passive"))
      (node (ref "U15") (pin "12") (pinfunction "6Y_12") (pintype "passive"))
      (node (ref "U5") (pin "61") (pinfunction "PD14_61") (pintype "passive"))
    )
    (net (code "68") (name "/SENS8") (class "Default")
      (node (ref "R72") (pin "1") (pinfunction "1_1") (pintype "passive"))
      (node (ref "U15") (pin "10") (pinfunction "5Y_10") (pintype "passive"))
      (node (ref "U5") (pin "60") (pinfunction "PD13_60") (pintype "passive"))
    )
    (net (code "69") (name "/SENS9") (class "Default")
      (node (ref "R73") (pin "1") (pinfunction "1_1") (pintype "passive"))
      (node (ref "U15") (pin "8") (pinfunction "4Y_8") (pintype "passive"))
      (node (ref "U5") (pin "59") (pinfunction "PD12_59") (pintype "passive"))
    )
    (net (code "70") (name "/SENS10") (class "Default")
      (node (ref "R74") (pin "1") (pinfunction "1_1") (pintype "passive"))
      (node (ref "U15") (pin "6") (pinfunction "3Y_6") (pintype "passive"))
      (node (ref "U5") (pin "58") (pinfunction "PD11_58") (pintype "passive"))
    )
    (net (code "71") (name "/SENS11") (class "Default")
      (node (ref "R75") (pin "1") (pinfunction "1_1") (pintype "passive"))
      (node (ref "U15") (pin "4") (pinfunction "2Y_4") (pintype "passive"))
      (node (ref "U5") (pin "57") (pinfunction "PD10_57") (pintype "passive"))
    )
    (net (code "72") (name "/SENS12") (class "Default")
      (node (ref "R76") (pin "1") (pinfunction "1_1") (pintype "passive"))
      (node (ref "U15") (pin "2") (pinfunction "1Y_2") (pintype "passive"))
      (node (ref "U5") (pin "56") (pinfunction "PD9_56") (pintype "passive"))
    )
    (net (code "73") (name "/SENSER1") (class "Default")
      (node (ref "C42") (pin "1") (pinfunction "1_1") (pintype "passive"))
      (node (ref "J4") (pin "18") (pinfunction "18_18") (pintype "passive"))
      (node (ref "R42") (pin "2") (pinfunction "2_2") (pintype "passive"))
      (node (ref "U14") (pin "13") (pinfunction "6A_13") (pintype "passive"))
    )
    (net (code "74") (name "/SENSER2") (class "Default")
      (node (ref "C46") (pin "1") (pinfunction "1_1") (pintype "passive"))
      (node (ref "J4") (pin "12") (pinfunction "12_12") (pintype "passive"))
      (node (ref "R40") (pin "2") (pinfunction "2_2") (pintype "passive"))
      (node (ref "U14") (pin "11") (pinfunction "5A_11") (pintype "passive"))
    )
    (net (code "75") (name "/SENSER3") (class "Default")
      (node (ref "C38") (pin "1") (pinfunction "1_1") (pintype "passive"))
      (node (ref "J4") (pin "6") (pinfunction "6_6") (pintype "passive"))
      (node (ref "R38") (pin "2") (pinfunction "2_2") (pintype "passive"))
      (node (ref "U14") (pin "9") (pinfunction "4A_9") (pintype "passive"))
    )
    (net (code "76") (name "/SENSER4") (class "Default")
      (node (ref "C43") (pin "1") (pinfunction "1_1") (pintype "passive"))
      (node (ref "J5") (pin "18") (pinfunction "18_18") (pintype "passive"))
      (node (ref "R36") (pin "2") (pinfunction "2_2") (pintype "passive"))
      (node (ref "U14") (pin "5") (pinfunction "3A_5") (pintype "passive"))
    )
    (net (code "77") (name "/SENSER5") (class "Default")
      (node (ref "C47") (pin "1") (pinfunction "1_1") (pintype "passive"))
      (node (ref "J5") (pin "12") (pinfunction "12_12") (pintype "passive"))
      (node (ref "R34") (pin "2") (pinfunction "2_2") (pintype "passive"))
      (node (ref "U14") (pin "3") (pinfunction "2A_3") (pintype "passive"))
    )
    (net (code "78") (name "/SENSER6") (class "Default")
      (node (ref "C39") (pin "1") (pinfunction "1_1") (pintype "passive"))
      (node (ref "J5") (pin "6") (pinfunction "6_6") (pintype "passive"))
      (node (ref "R32") (pin "2") (pinfunction "2_2") (pintype "passive"))
      (node (ref "U14") (pin "1") (pinfunction "1A_1") (pintype "passive"))
    )
    (net (code "79") (name "/SENSER7") (class "Default")
      (node (ref "C44") (pin "1") (pinfunction "1_1") (pintype "passive"))
      (node (ref "J6") (pin "18") (pinfunction "18_18") (pintype "passive"))
      (node (ref "R30") (pin "2") (pinfunction "2_2") (pintype "passive"))
      (node (ref "U15") (pin "13") (pinfunction "6A_13") (pintype "passive"))
    )
    (net (code "80") (name "/SENSER8") (class "Default")
      (node (ref "C48") (pin "1") (pinfunction "1_1") (pintype "passive"))
      (node (ref "J6") (pin "12") (pinfunction "12_12") (pintype "passive"))
      (node (ref "R28") (pin "2") (pinfunction "2_2") (pintype "passive"))
      (node (ref "U15") (pin "11") (pinfunction "5A_11") (pintype "passive"))
    )
    (net (code "81") (name "/SENSER9") (class "Default")
      (node (ref "C40") (pin "1") (pinfunction "1_1") (pintype "passive"))
      (node (ref "J6") (pin "6") (pinfunction "6_6") (pintype "passive"))
      (node (ref "R26") (pin "2") (pinfunction "2_2") (pintype "passive"))
      (node (ref "U15") (pin "9") (pinfunction "4A_9") (pintype "passive"))
    )
    (net (code "82") (name "/SENSER10") (class "Default")
      (node (ref "C45") (pin "1") (pinfunction "1_1") (pintype "passive"))
      (node (ref "J8") (pin "18") (pinfunction "18_18") (pintype "passive"))
      (node (ref "R48") (pin "2") (pinfunction "2_2") (pintype "passive"))
      (node (ref "U15") (pin "5") (pinfunction "3A_5") (pintype "passive"))
    )
    (net (code "83") (name "/SENSER11") (class "Default")
      (node (ref "C49") (pin "1") (pinfunction "1_1") (pintype "passive"))
      (node (ref "J8") (pin "12") (pinfunction "12_12") (pintype "passive"))
      (node (ref "R46") (pin "2") (pinfunction "2_2") (pintype "passive"))
      (node (ref "U15") (pin "3") (pinfunction "2A_3") (pintype "passive"))
    )
    (net (code "84") (name "/SENSER12") (class "Default")
      (node (ref "C41") (pin "1") (pinfunction "1_1") (pintype "passive"))
      (node (ref "J8") (pin "6") (pinfunction "6_6") (pintype "passive"))
      (node (ref "R44") (pin "2") (pinfunction "2_2") (pintype "passive"))
      (node (ref "U15") (pin "1") (pinfunction "1A_1") (pintype "passive"))
    )
    (net (code "85") (name "/SENS_POWER") (class "Default")
      (node (ref "P1") (pin "1") (pinfunction "A_1") (pintype "passive"))
      (node (ref "U5") (pin "55") (pinfunction "PD8_55") (pintype "passive"))
    )
    (net (code "86") (name "/SGND") (class "Default")
      (node (ref "C74") (pin "1") (pinfunction "1_1") (pintype "passive"))
      (node (ref "C75") (pin "1") (pinfunction "1_1") (pintype "passive"))
      (node (ref "C77") (pin "1") (pinfunction "1_1") (pintype "passive"))
      (node (ref "C84") (pin "1") (pinfunction "1_1") (pintype "passive"))
      (node (ref "C85") (pin "1") (pinfunction "1_1") (pintype "passive"))
      (node (ref "C86") (pin "2") (pinfunction "2_2") (pintype "passive"))
      (node (ref "C90") (pin "2") (pinfunction "2_2") (pintype "passive"))
      (node (ref "C91") (pin "1") (pinfunction "1_1") (pintype "passive"))
      (node (ref "J21") (pin "1") (pinfunction "1_1") (pintype "passive"))
      (node (ref "J22") (pin "1") (pinfunction "1_1") (pintype "passive"))
      (node (ref "J23") (pin "1") (pinfunction "1_1") (pintype "passive"))
      (node (ref "J24") (pin "1") (pinfunction "1_1") (pintype "passive"))
      (node (ref "L3") (pin "2") (pinfunction "2_2") (pintype "passive"))
      (node (ref "U23") (pin "10") (pinfunction "TVSS_10") (pintype "passive"))
      (node (ref "U23") (pin "14") (pinfunction "TVSS_14") (pintype "passive"))
      (node (ref "U23") (pin "18") (pinfunction "AVSS_18") (pintype "passive"))
    )
    (net (code "87") (name "/SOLE-1") (class "Default")
      (node (ref "P4") (pin "1") (pinfunction "A_1") (pintype "passive"))
      (node (ref "U5") (pin "98") (pinfunction "PE1_98") (pintype "passive"))
    )
    (net (code "88") (name "/SOLE-2") (class "Default")
      (node (ref "P5") (pin "1") (pinfunction "A_1") (pintype "passive"))
      (node (ref "U5") (pin "97") (pinfunction "PE0_97") (pintype "passive"))
    )
    (net (code "89") (name "/SOLE-3") (class "Default")
      (node (ref "P6") (pin "1") (pinfunction "A_1") (pintype "passive"))
      (node (ref "U5") (pin "96") (pinfunction "PB9_96") (pintype "passive"))
    )
    (net (code "90") (name "/SOLE-4") (class "Default")
      (node (ref "P7") (pin "1") (pinfunction "A_1") (pintype "passive"))
      (node (ref "U5") (pin "95") (pinfunction "PB8_95") (pintype "passive"))
    )
    (net (code "91") (name "/SOLE-5") (class "Default")
      (node (ref "P8") (pin "1") (pinfunction "A_1") (pintype "passive"))
      (node (ref "U5") (pin "93") (pinfunction "PB7_93") (pintype "passive"))
    )
    (net (code "92") (name "/SP") (class "Default")
      (node (ref "P1") (pin "4") (pinfunction "C_4") (pintype "passive"))
      (node (ref "R12") (pin "2") (pinfunction "2_2") (pintype "passive"))
      (node (ref "U8") (pin "4") (pinfunction "G_4") (pintype "passive"))
    )
    (net (code "93") (name "/SPI1_MISO") (class "Default")
      (node (ref "U5") (pin "31") (pinfunction "PA6_31") (pintype "passive"))
      (node (ref "U7") (pin "2") (pinfunction "SO_2") (pintype "passive"))
    )
    (net (code "94") (name "/SPI1_MOSI") (class "Default")
      (node (ref "U5") (pin "32") (pinfunction "PA7_32") (pintype "passive"))
      (node (ref "U7") (pin "5") (pinfunction "SI_5") (pintype "passive"))
    )
    (net (code "95") (name "/SPI1_SCK") (class "Default")
      (node (ref "U5") (pin "30") (pinfunction "PA5_30") (pintype "passive"))
      (node (ref "U7") (pin "6") (pinfunction "CLK_6") (pintype "passive"))
    )
    (net (code "96") (name "/SPI2_MISO") (class "Default")
      (node (ref "U23") (pin "31") (pinfunction "D7_31") (pintype "passive"))
      (node (ref "U5") (pin "53") (pinfunction "PB14_53") (pintype "passive"))
    )
    (net (code "97") (name "/SPI2_MOSI") (class "Default")
      (node (ref "U23") (pin "30") (pinfunction "D6_30") (pintype "passive"))
      (node (ref "U5") (pin "54") (pinfunction "PB15_54") (pintype "passive"))
    )
    (net (code "98") (name "/SPI2_NSS") (class "Default")
      (node (ref "U23") (pin "24") (pinfunction "SDA_24") (pintype "passive"))
      (node (ref "U5") (pin "51") (pinfunction "PB12_51") (pintype "passive"))
    )
    (net (code "99") (name "/SPI2_SCK") (class "Default")
      (node (ref "U23") (pin "29") (pinfunction "D5_29") (pintype "passive"))
      (node (ref "U5") (pin "52") (pinfunction "PB13_52") (pintype "passive"))
    )
    (net (code "100") (name "/Switch1") (class "Default")
      (node (ref "D44") (pin "K") (pinfunction "K_K") (pintype "passive"))
      (node (ref "J20") (pin "11") (pinfunction "11_11") (pintype "passive"))
    )
    (net (code "101") (name "/Switch2") (class "Default")
      (node (ref "D45") (pin "K") (pinfunction "K_K") (pintype "passive"))
      (node (ref "J20") (pin "9") (pinfunction "9_9") (pintype "passive"))
    )
    (net (code "102") (name "/Switch3") (class "Default")
      (node (ref "D46") (pin "K") (pinfunction "K_K") (pintype "passive"))
      (node (ref "J20") (pin "7") (pinfunction "7_7") (pintype "passive"))
    )
    (net (code "103") (name "/Switch4") (class "Default")
      (node (ref "D47") (pin "K") (pinfunction "K_K") (pintype "passive"))
      (node (ref "J20") (pin "5") (pinfunction "5_5") (pintype "passive"))
    )
    (net (code "104") (name "/Switch5") (class "Default")
      (node (ref "D48") (pin "K") (pinfunction "K_K") (pintype "passive"))
      (node (ref "J20") (pin "3") (pinfunction "3_3") (pintype "passive"))
    )
    (net (code "105") (name "/Switch6") (class "Default")
      (node (ref "D49") (pin "K") (pinfunction "K_K") (pintype "passive"))
      (node (ref "J20") (pin "1") (pinfunction "1_1") (pintype "passive"))
    )
    (net (code "106") (name "/TCK") (class "Default")
      (node (ref "J7") (pin "9") (pinfunction "TCK_9") (pintype "passive"))
      (node (ref "U5") (pin "76") (pinfunction "PA14_76") (pintype "passive"))
    )
    (net (code "107") (name "/TDI") (class "Default")
      (node (ref "J7") (pin "5") (pinfunction "TDI_5") (pintype "passive"))
      (node (ref "U5") (pin "77") (pinfunction "PA15_77") (pintype "passive"))
    )
    (net (code "108") (name "/TDO") (class "Default")
      (node (ref "J7") (pin "13") (pinfunction "TDO_13") (pintype "passive"))
      (node (ref "U5") (pin "89") (pinfunction "PB3_89") (pintype "passive"))
    )
    (net (code "109") (name "/TMS") (class "Default")
      (node (ref "J7") (pin "7") (pinfunction "TMS_7") (pintype "passive"))
      (node (ref "U5") (pin "72") (pinfunction "PA13_72") (pintype "passive"))
    )
    (net (code "110") (name "/TVDD") (class "Default")
      (node (ref "C74") (pin "2") (pinfunction "2_2") (pintype "passive"))
      (node (ref "C75") (pin "2") (pinfunction "2_2") (pintype "passive"))
      (node (ref "C77") (pin "2") (pinfunction "2_2") (pintype "passive"))
      (node (ref "L2") (pin "2") (pinfunction "2_2") (pintype "passive"))
      (node (ref "L4") (pin "1") (pinfunction "1_1") (pintype "passive"))
      (node (ref "U23") (pin "12") (pinfunction "TVDD_12") (pintype "passive"))
    )
    (net (code "111") (name "/TX1") (class "Default")
      (node (ref "L5") (pin "1") (pinfunction "1_1") (pintype "passive"))
      (node (ref "L6") (pin "1") (pinfunction "1_1") (pintype "passive"))
      (node (ref "U23") (pin "11") (pinfunction "TX1_11") (pintype "passive"))
    )
    (net (code "112") (name "/TXD1") (class "Default")
      (node (ref "D53") (pin "2") (pinfunction "K_2") (pintype "passive"))
      (node (ref "U12") (pin "10") (pinfunction "T2IN_10") (pintype "passive"))
      (node (ref "U3") (pin "4") (pinfunction "DI_4") (pintype "passive"))
      (node (ref "U5") (pin "68") (pinfunction "PA9_68") (pintype "passive"))
    )
    (net (code "113") (name "/TXD2") (class "Default")
      (node (ref "U11") (pin "11") (pinfunction "T1IN_11") (pintype "passive"))
      (node (ref "U5") (pin "25") (pinfunction "PA2_25") (pintype "passive"))
    )
    (net (code "114") (name "/TXD3") (class "Default")
      (node (ref "U11") (pin "10") (pinfunction "T2IN_10") (pintype "passive"))
      (node (ref "U5") (pin "47") (pinfunction "PB10_47") (pintype "passive"))
    )
    (net (code "115") (name "/TXD4") (class "Default")
      (node (ref "U5") (pin "78") (pinfunction "PC10_78") (pintype "passive"))
    )
    (net (code "116") (name "/TXD5") (class "Default")
      (node (ref "U5") (pin "80") (pinfunction "PC12_80") (pintype "passive+no_connect"))
    )
    (net (code "117") (name "/TXD_M1") (class "Default")
      (node (ref "J10") (pin "1") (pinfunction "1_1") (pintype "passive"))
      (node (ref "U12") (pin "8") (pinfunction "R2IN_8") (pintype "passive"))
    )
    (net (code "118") (name "/TXD_M2") (class "Default")
      (node (ref "J9") (pin "4") (pinfunction "4_4") (pintype "passive"))
      (node (ref "U11") (pin "13") (pinfunction "R1IN_13") (pintype "passive"))
    )
    (net (code "119") (name "/TXD_M3") (class "Default")
      (node (ref "J9") (pin "1") (pinfunction "1_1") (pintype "passive"))
      (node (ref "U11") (pin "8") (pinfunction "R2IN_8") (pintype "passive"))
    )
    (net (code "120") (name "/VMID") (class "Default")
      (node (ref "C86") (pin "1") (pinfunction "1_1") (pintype "passive"))
      (node (ref "R129") (pin "2") (pinfunction "2_2") (pintype "passive"))
      (node (ref "U23") (pin "16") (pinfunction "VMID_16") (pintype "passive"))
    )
    (net (code "121") (name "/V_check_1") (class "Default")
      (node (ref "U17") (pin "1") (pinfunction "OUT_1") (pintype "open_collector"))
      (node (ref "U5") (pin "2") (pinfunction "PE3_2") (pintype "passive"))
    )
    (net (code "122") (name "/V_check_2") (class "Default")
      (node (ref "U17") (pin "7") (pinfunction "OUT_7") (pintype "open_collector"))
      (node (ref "U5") (pin "1") (pinfunction "PE2_1") (pintype "passive"))
    )
    (net (code "123") (name "/a") (class "Default")
      (node (ref "R91") (pin "1") (pinfunction "1_1") (pintype "passive"))
      (node (ref "U5") (pin "8") (pinfunction "PC14-OSC32_IN_8") (pintype "passive"))
    )
    (net (code "124") (name "/b") (class "Default")
      (node (ref "R90") (pin "1") (pinfunction "1_1") (pintype "passive"))
      (node (ref "U5") (pin "9") (pinfunction "PC15-OSC32_OUT_9") (pintype "passive"))
    )
    (net (code "125") (name "/c") (class "Default")
      (node (ref "R89") (pin "1") (pinfunction "1_1") (pintype "passive"))
      (node (ref "U5") (pin "15") (pinfunction "PC0_15") (pintype "passive"))
    )
    (net (code "126") (name "/check1") (class "Default")
      (node (ref "R108") (pin "1") (pinfunction "1_1") (pintype "passive"))
      (node (ref "U16") (pin "19") (pinfunction "CU-B_19") (pintype "passive"))
      (node (ref "U17") (pin "3") (pinfunction "IN+_3") (pintype "input"))
    )
    (net (code "127") (name "/check2") (class "Default")
      (node (ref "R107") (pin "1") (pinfunction "1_1") (pintype "passive"))
      (node (ref "U16") (pin "2") (pinfunction "CU-A_2") (pintype "passive"))
      (node (ref "U17") (pin "5") (pinfunction "IN+_5") (pintype "input"))
    )
    (net (code "128") (name "/d") (class "Default")
      (node (ref "R88") (pin "1") (pinfunction "1_1") (pintype "passive"))
      (node (ref "U5") (pin "17") (pinfunction "PC2_17") (pintype "passive"))
    )
    (net (code "129") (name "/dp") (class "Default")
      (node (ref "R9") (pin "1") (pinfunction "1_1") (pintype "passive"))
      (node (ref "U5") (pin "16") (pinfunction "PC1_16") (pintype "passive"))
    )
    (net (code "130") (name "/e") (class "Default")
      (node (ref "R87") (pin "1") (pinfunction "1_1") (pintype "passive"))
      (node (ref "U5") (pin "18") (pinfunction "PC3_18") (pintype "passive"))
    )
    (net (code "131") (name "/f") (class "Default")
      (node (ref "R84") (pin "1") (pinfunction "1_1") (pintype "passive"))
      (node (ref "U5") (pin "24") (pinfunction "PA1_24") (pintype "passive"))
    )
    (net (code "132") (name "/g") (class "Default")
      (node (ref "R83") (pin "1") (pinfunction "1_1") (pintype "passive"))
      (node (ref "U5") (pin "23") (pinfunction "PA0-WKUP_23") (pintype "passive"))
    )
    (net (code "133") (name "/heartbeat1") (class "Default")
      (node (ref "R117") (pin "1") (pinfunction "1_1") (pintype "passive"))
      (node (ref "U5") (pin "70") (pinfunction "PA11_70") (pintype "passive"))
    )
    (net (code "134") (name "/heartbeat2") (class "Default")
      (node (ref "R116") (pin "1") (pinfunction "1_1") (pintype "passive"))
      (node (ref "U5") (pin "71") (pinfunction "PA12_71") (pintype "passive"))
    )
    (net (code "135") (name "/key1") (class "Default")
      (node (ref "C68") (pin "1") (pinfunction "1_1") (pintype "passive"))
      (node (ref "R8") (pin "2") (pinfunction "2_2") (pintype "passive"))
      (node (ref "U5") (pin "45") (pinfunction "PE14_45") (pintype "passive"))
      (node (ref "k1") (pin "2") (pinfunction "2_2") (pintype "passive"))
    )
    (net (code "136") (name "/key2") (class "Default")
      (node (ref "C28") (pin "1") (pinfunction "1_1") (pintype "passive"))
      (node (ref "R7") (pin "2") (pinfunction "2_2") (pintype "passive"))
      (node (ref "U5") (pin "46") (pinfunction "PE15_46") (pintype "passive"))
      (node (ref "k2") (pin "2") (pinfunction "2_2") (pintype "passive"))
    )
    (net (code "137") (name "AGND") (class "Default")
      (node (ref "C10") (pin "2") (pinfunction "2_2") (pintype "passive"))
      (node (ref "C13") (pin "2") (pinfunction "2_2") (pintype "passive"))
      (node (ref "C15") (pin "2") (pinfunction "2_2") (pintype "passive"))
      (node (ref "C64") (pin "2") (pinfunction "2_2") (pintype "passive"))
      (node (ref "C65") (pin "2") (pinfunction "2_2") (pintype "passive"))
      (node (ref "C67") (pin "2") (pinfunction "2_2") (pintype "passive"))
      (node (ref "C69") (pin "2") (pinfunction "2_2") (pintype "passive"))
      (node (ref "Q10") (pin "1") (pintype "passive"))
      (node (ref "Q11") (pin "3") (pinfunction "S_3") (pintype "passive"))
      (node (ref "Q3") (pin "2") (pinfunction "S_2") (pintype "input"))
      (node (ref "Q4") (pin "2") (pinfunction "S_2") (pintype "input"))
      (node (ref "Q5") (pin "2") (pinfunction "S_2") (pintype "input"))
      (node (ref "Q6") (pin "3") (pinfunction "S_3") (pintype "passive"))
      (node (ref "Q7") (pin "1") (pintype "passive"))
      (node (ref "Q8") (pin "1") (pintype "passive"))
      (node (ref "Q9") (pin "1") (pintype "passive"))
      (node (ref "R106") (pin "1") (pinfunction "1_1") (pintype "passive"))
      (node (ref "R107") (pin "2") (pinfunction "2_2") (pintype "passive"))
      (node (ref "R108") (pin "2") (pinfunction "2_2") (pintype "passive"))
      (node (ref "R110") (pin "2") (pinfunction "2_2") (pintype "passive"))
      (node (ref "R79") (pin "2") (pinfunction "2_2") (pintype "passive"))
      (node (ref "R80") (pin "2") (pinfunction "2_2") (pintype "passive"))
      (node (ref "R95") (pin "2") (pinfunction "2_2") (pintype "passive"))
      (node (ref "R96") (pin "2") (pinfunction "2_2") (pintype "passive"))
      (node (ref "U16") (pin "1") (pinfunction "GND_1") (pintype "passive"))
      (node (ref "U16") (pin "10") (pinfunction "GND_10") (pintype "passive"))
      (node (ref "U16") (pin "11") (pinfunction "GND_11") (pintype "passive"))
      (node (ref "U16") (pin "20") (pinfunction "GND_20") (pintype "passive"))
    )
    (net (code "138") (name "GND") (class "Default")
      (node (ref "C1") (pin "2") (pinfunction "2_2") (pintype "passive"))
      (node (ref "C11") (pin "2") (pinfunction "2_2") (pintype "passive"))
      (node (ref "C12") (pin "2") (pinfunction "2_2") (pintype "passive"))
      (node (ref "C14") (pin "2") (pinfunction "2_2") (pintype "passive"))
      (node (ref "C16") (pin "2") (pinfunction "2_2") (pintype "passive"))
      (node (ref "C17") (pin "2") (pinfunction "2_2") (pintype "passive"))
      (node (ref "C18") (pin "2") (pinfunction "2_2") (pintype "passive"))
      (node (ref "C19") (pin "2") (pinfunction "2_2") (pintype "passive"))
      (node (ref "C2") (pin "1") (pinfunction "1_1") (pintype "passive"))
      (node (ref "C20") (pin "2") (pinfunction "2_2") (pintype "passive"))
      (node (ref "C21") (pin "1") (pinfunction "1_1") (pintype "passive"))
      (node (ref "C22") (pin "1") (pinfunction "1_1") (pintype "passive"))
      (node (ref "C23") (pin "1") (pinfunction "1_1") (pintype "passive"))
      (node (ref "C24") (pin "1") (pinfunction "1_1") (pintype "passive"))
      (node (ref "C25") (pin "1") (pinfunction "1_1") (pintype "passive"))
      (node (ref "C26") (pin "2") (pinfunction "2_2") (pintype "passive"))
      (node (ref "C27") (pin "1") (pinfunction "1_1") (pintype "passive"))
      (node (ref "C28") (pin "2") (pinfunction "2_2") (pintype "passive"))
      (node (ref "C29") (pin "2") (pinfunction "2_2") (pintype "passive"))
      (node (ref "C3") (pin "2") (pinfunction "2_2") (pintype "passive"))
      (node (ref "C30") (pin "2") (pinfunction "2_2") (pintype "passive"))
      (node (ref "C38") (pin "2") (pinfunction "2_2") (pintype "passive"))
      (node (ref "C39") (pin "2") (pinfunction "2_2") (pintype "passive"))
      (node (ref "C4") (pin "2") (pinfunction "2_2") (pintype "passive"))
      (node (ref "C40") (pin "2") (pinfunction "2_2") (pintype "passive"))
      (node (ref "C41") (pin "2") (pinfunction "2_2") (pintype "passive"))
      (node (ref "C42") (pin "2") (pinfunction "2_2") (pintype "passive"))
      (node (ref "C43") (pin "2") (pinfunction "2_2") (pintype "passive"))
      (node (ref "C44") (pin "2") (pinfunction "2_2") (pintype "passive"))
      (node (ref "C45") (pin "2") (pinfunction "2_2") (pintype "passive"))
      (node (ref "C46") (pin "2") (pinfunction "2_2") (pintype "passive"))
      (node (ref "C47") (pin "2") (pinfunction "2_2") (pintype "passive"))
      (node (ref "C48") (pin "2") (pinfunction "2_2") (pintype "passive"))
      (node (ref "C49") (pin "2") (pinfunction "2_2") (pintype "passive"))
      (node (ref "C5") (pin "1") (pinfunction "1_1") (pintype "passive"))
      (node (ref "C53") (pin "2") (pinfunction "2_2") (pintype "passive"))
      (node (ref "C55") (pin "2") (pinfunction "2_2") (pintype "passive"))
      (node (ref "C59") (pin "2") (pinfunction "2_2") (pintype "passive"))
      (node (ref "C60") (pin "2") (pinfunction "2_2") (pintype "passive"))
      (node (ref "C62") (pin "2") (pinfunction "2_2") (pintype "passive"))
      (node (ref "C63") (pin "2") (pinfunction "2_2") (pintype "passive"))
      (node (ref "C66") (pin "1") (pinfunction "1_1") (pintype "passive"))
      (node (ref "C68") (pin "2") (pinfunction "2_2") (pintype "passive"))
      (node (ref "C69") (pin "1") (pinfunction "1_1") (pintype "passive"))
      (node (ref "C7") (pin "2") (pinfunction "2_2") (pintype "passive"))
      (node (ref "C71") (pin "1") (pinfunction "1_1") (pintype "passive"))
      (node (ref "C72") (pin "2") (pinfunction "2_2") (pintype "passive"))
      (node (ref "C73") (pin "1") (pinfunction "1_1") (pintype "passive"))
      (node (ref "C76") (pin "1") (pinfunction "1_1") (pintype "passive"))
      (node (ref "C8") (pin "2") (pinfunction "2_2") (pintype "passive"))
      (node (ref "C9") (pin "2") (pinfunction "2_2") (pintype "passive"))
      (node (ref "C92") (pin "1") (pinfunction "1_1") (pintype "passive"))
      (node (ref "C93") (pin "1") (pinfunction "1_1") (pintype "passive"))
      (node (ref "D10") (pin "2") (pinfunction "K_2") (pintype "passive"))
      (node (ref "D12") (pin "1") (pinfunction "A_1") (pintype "passive"))
      (node (ref "D13") (pin "1") (pinfunction "A_1") (pintype "passive"))
      (node (ref "D22") (pin "2") (pinfunction "K_2") (pintype "passive"))
      (node (ref "D23") (pin "2") (pinfunction "K_2") (pintype "passive"))
      (node (ref "D24") (pin "2") (pinfunction "K_2") (pintype "passive"))
      (node (ref "D25") (pin "2") (pinfunction "K_2") (pintype "passive"))
      (node (ref "D26") (pin "2") (pinfunction "K_2") (pintype "passive"))
      (node (ref "D27") (pin "2") (pinfunction "K_2") (pintype "passive"))
      (node (ref "D28") (pin "2") (pinfunction "K_2") (pintype "passive"))
      (node (ref "D29") (pin "2") (pinfunction "K_2") (pintype "passive"))
      (node (ref "D30") (pin "2") (pinfunction "K_2") (pintype "passive"))
      (node (ref "D31") (pin "2") (pinfunction "K_2") (pintype "passive"))
      (node (ref "D32") (pin "2") (pinfunction "K_2") (pintype "passive"))
      (node (ref "D33") (pin "2") (pinfunction "K_2") (pintype "passive"))
      (node (ref "D50") (pin "2") (pinfunction "K_2") (pintype "passive"))
      (node (ref "D51") (pin "2") (pinfunction "K_2") (pintype "passive"))
      (node (ref "D8") (pin "2") (pinfunction "K_2") (pintype "passive"))
      (node (ref "D9") (pin "2") (pinfunction "K_2") (pintype "passive"))
      (node (ref "J1") (pin "15") (pinfunction "15_15") (pintype "passive"))
      (node (ref "J10") (pin "3") (pinfunction "3_3") (pintype "passive"))
      (node (ref "J2") (pin "2") (pinfunction "2_2") (pintype "passive"))
      (node (ref "J2") (pin "4") (pinfunction "4_4") (pintype "passive"))
      (node (ref "J20") (pin "10") (pinfunction "10_10") (pintype "passive"))
      (node (ref "J20") (pin "12") (pinfunction "12_12") (pintype "passive"))
      (node (ref "J20") (pin "2") (pinfunction "2_2") (pintype "passive"))
      (node (ref "J20") (pin "4") (pinfunction "4_4") (pintype "passive"))
      (node (ref "J20") (pin "6") (pinfunction "6_6") (pintype "passive"))
      (node (ref "J20") (pin "8") (pinfunction "8_8") (pintype "passive"))
      (node (ref "J3") (pin "2") (pinfunction "2_2") (pintype "passive"))
      (node (ref "J3") (pin "4") (pinfunction "4_4") (pintype "passive"))
      (node (ref "J4") (pin "1") (pinfunction "1_1") (pintype "passive"))
      (node (ref "J4") (pin "11") (pinfunction "11_11") (pintype "passive"))
      (node (ref "J4") (pin "13") (pinfunction "13_13") (pintype "passive"))
      (node (ref "J4") (pin "15") (pinfunction "15_15") (pintype "passive"))
      (node (ref "J4") (pin "17") (pinfunction "17_17") (pintype "passive"))
      (node (ref "J4") (pin "3") (pinfunction "3_3") (pintype "passive"))
      (node (ref "J4") (pin "5") (pinfunction "5_5") (pintype "passive"))
      (node (ref "J4") (pin "7") (pinfunction "7_7") (pintype "passive"))
      (node (ref "J4") (pin "9") (pinfunction "9_9") (pintype "passive"))
      (node (ref "J5") (pin "1") (pinfunction "1_1") (pintype "passive"))
      (node (ref "J5") (pin "11") (pinfunction "11_11") (pintype "passive"))
      (node (ref "J5") (pin "13") (pinfunction "13_13") (pintype "passive"))
      (node (ref "J5") (pin "15") (pinfunction "15_15") (pintype "passive"))
      (node (ref "J5") (pin "17") (pinfunction "17_17") (pintype "passive"))
      (node (ref "J5") (pin "3") (pinfunction "3_3") (pintype "passive"))
      (node (ref "J5") (pin "5") (pinfunction "5_5") (pintype "passive"))
      (node (ref "J5") (pin "7") (pinfunction "7_7") (pintype "passive"))
      (node (ref "J5") (pin "9") (pinfunction "9_9") (pintype "passive"))
      (node (ref "J6") (pin "1") (pinfunction "1_1") (pintype "passive"))
      (node (ref "J6") (pin "11") (pinfunction "11_11") (pintype "passive"))
      (node (ref "J6") (pin "13") (pinfunction "13_13") (pintype "passive"))
      (node (ref "J6") (pin "15") (pinfunction "15_15") (pintype "passive"))
      (node (ref "J6") (pin "17") (pinfunction "17_17") (pintype "passive"))
      (node (ref "J6") (pin "3") (pinfunction "3_3") (pintype "passive"))
      (node (ref "J6") (pin "5") (pinfunction "5_5") (pintype "passive"))
      (node (ref "J6") (pin "7") (pinfunction "7_7") (pintype "passive"))
      (node (ref "J6") (pin "9") (pinfunction "9_9") (pintype "passive"))
      (node (ref "J7") (pin "10") (pinfunction "GND_10") (pintype "passive"))
      (node (ref "J7") (pin "12") (pinfunction "GND_12") (pintype "passive"))
      (node (ref "J7") (pin "14") (pinfunction "GND_14") (pintype "passive"))
      (node (ref "J7") (pin "16") (pinfunction "GND_16") (pintype "passive"))
      (node (ref "J7") (pin "18") (pinfunction "GND_18") (pintype "passive"))
      (node (ref "J7") (pin "20") (pinfunction "GND_20") (pintype "passive"))
      (node (ref "J7") (pin "4") (pinfunction "GND_4") (pintype "passive"))
      (node (ref "J7") (pin "6") (pinfunction "GND_6") (pintype "passive"))
      (node (ref "J7") (pin "8") (pinfunction "GND_8") (pintype "passive"))
      (node (ref "J8") (pin "1") (pinfunction "1_1") (pintype "passive"))
      (node (ref "J8") (pin "11") (pinfunction "11_11") (pintype "passive"))
      (node (ref "J8") (pin "13") (pinfunction "13_13") (pintype "passive"))
      (node (ref "J8") (pin "15") (pinfunction "15_15") (pintype "passive"))
      (node (ref "J8") (pin "17") (pinfunction "17_17") (pintype "passive"))
      (node (ref "J8") (pin "3") (pinfunction "3_3") (pintype "passive"))
      (node (ref "J8") (pin "5") (pinfunction "5_5") (pintype "passive"))
      (node (ref "J8") (pin "7") (pinfunction "7_7") (pintype "passive"))
      (node (ref "J8") (pin "9") (pinfunction "9_9") (pintype "passive"))
      (node (ref "J9") (pin "3") (pinfunction "3_3") (pintype "passive"))
      (node (ref "J9") (pin "6") (pinfunction "6_6") (pintype "passive"))
      (node (ref "K3") (pin "1") (pinfunction "1_1") (pintype "passive"))
      (node (ref "L3") (pin "1") (pinfunction "1_1") (pintype "passive"))
      (node (ref "R100") (pin "1") (pinfunction "1_1") (pintype "passive"))
      (node (ref "R101") (pin "1") (pinfunction "1_1") (pintype "passive"))
      (node (ref "R106") (pin "2") (pinfunction "2_2") (pintype "passive"))
      (node (ref "R109") (pin "2") (pinfunction "2_2") (pintype "passive"))
      (node (ref "R111") (pin "2") (pinfunction "2_2") (pintype "passive"))
      (node (ref "R118") (pin "1") (pinfunction "1_1") (pintype "passive"))
      (node (ref "R23") (pin "2") (pinfunction "2_2") (pintype "passive"))
      (node (ref "R24") (pin "1") (pinfunction "1_1") (pintype "passive"))
      (node (ref "R56") (pin "1") (pinfunction "1_1") (pintype "passive"))
      (node (ref "R58") (pin "1") (pinfunction "1_1") (pintype "passive"))
      (node (ref "R77") (pin "2") (pinfunction "2_2") (pintype "passive"))
      (node (ref "R78") (pin "2") (pinfunction "2_2") (pintype "passive"))
      (node (ref "R92") (pin "2") (pinfunction "2_2") (pintype "passive"))
      (node (ref "R93") (pin "2") (pinfunction "2_2") (pintype "passive"))
      (node (ref "R94") (pin "1") (pinfunction "1_1") (pintype "passive"))
      (node (ref "R99") (pin "1") (pinfunction "1_1") (pintype "passive"))
      (node (ref "U1") (pin "2") (pinfunction "GND_2") (pintype "passive"))
      (node (ref "U11") (pin "15") (pinfunction "GND_15") (pintype "passive"))
      (node (ref "U12") (pin "15") (pinfunction "GND_15") (pintype "passive"))
      (node (ref "U14") (pin "7") (pinfunction "GND_7") (pintype "passive"))
      (node (ref "U15") (pin "7") (pinfunction "GND_7") (pintype "passive"))
      (node (ref "U17") (pin "4") (pinfunction "V-_4") (pintype "power_in"))
      (node (ref "U2") (pin "0") (pinfunction "GND_0") (pintype "passive"))
      (node (ref "U2") (pin "3") (pinfunction "GND_3") (pintype "passive"))
      (node (ref "U2") (pin "5") (pinfunction "/ON_5") (pintype "passive"))
      (node (ref "U23") (pin "1") (pinfunction "IIC_1") (pintype "passive"))
      (node (ref "U23") (pin "4") (pinfunction "DVSS_4") (pintype "passive"))
      (node (ref "U23") (pin "5") (pinfunction "PVSS_5") (pintype "passive"))
      (node (ref "U3") (pin "5") (pinfunction "GND_5") (pintype "passive"))
      (node (ref "U5") (pin "10") (pinfunction "VSS_5_10") (pintype "passive"))
      (node (ref "U5") (pin "19") (pinfunction "VSSA_19") (pintype "passive"))
      (node (ref "U5") (pin "20") (pinfunction "VREF-_20") (pintype "passive"))
      (node (ref "U5") (pin "27") (pinfunction "VSS_4_27") (pintype "passive"))
      (node (ref "U5") (pin "49") (pinfunction "VSS_1_49") (pintype "passive"))
      (node (ref "U5") (pin "74") (pinfunction "VSS_2_74") (pintype "passive"))
      (node (ref "U5") (pin "99") (pinfunction "VSS_3_99") (pintype "passive"))
      (node (ref "U6") (pin "1") (pinfunction "GND_1") (pintype "passive"))
      (node (ref "U7") (pin "4") (pinfunction "GND_4") (pintype "passive"))
      (node (ref "U9") (pin "8") (pinfunction "GND_8") (pintype "passive"))
      (node (ref "k1") (pin "1") (pinfunction "1_1") (pintype "passive"))
      (node (ref "k2") (pin "1") (pinfunction "1_1") (pintype "passive"))
    )
    (net (code "139") (name "Net-(C79-Pad2)") (class "Default")
      (node (ref "C79") (pin "2") (pinfunction "2_2") (pintype "passive"))
      (node (ref "J21") (pin "2") (pinfunction "2_2") (pintype "passive"))
    )
    (net (code "140") (name "Net-(C80-Pad2)") (class "Default")
      (node (ref "C80") (pin "2") (pinfunction "2_2") (pintype "passive"))
      (node (ref "J22") (pin "2") (pinfunction "2_2") (pintype "passive"))
    )
    (net (code "141") (name "Net-(C81-Pad2)") (class "Default")
      (node (ref "C81") (pin "2") (pinfunction "2_2") (pintype "passive"))
      (node (ref "J23") (pin "2") (pinfunction "2_2") (pintype "passive"))
    )
    (net (code "142") (name "Net-(C82-Pad2)") (class "Default")
      (node (ref "C82") (pin "2") (pinfunction "2_2") (pintype "passive"))
      (node (ref "J24") (pin "2") (pinfunction "2_2") (pintype "passive"))
    )
    (net (code "143") (name "Net-(C87-Pad1)") (class "Default")
      (node (ref "C87") (pin "1") (pinfunction "1_1") (pintype "passive"))
      (node (ref "R130") (pin "2") (pinfunction "2_2") (pintype "passive"))
    )
    (net (code "144") (name "Net-(C88-Pad1)") (class "Default")
      (node (ref "C88") (pin "1") (pinfunction "1_1") (pintype "passive"))
      (node (ref "C90") (pin "1") (pinfunction "1_1") (pintype "passive"))
      (node (ref "L5") (pin "2") (pinfunction "2_2") (pintype "passive"))
      (node (ref "L6") (pin "2") (pinfunction "2_2") (pintype "passive"))
    )
    (net (code "145") (name "Net-(D2-A)") (class "Default")
      (node (ref "D2") (pin "1") (pinfunction "A_1") (pintype "passive"))
      (node (ref "R17") (pin "2") (pinfunction "2_2") (pintype "passive"))
    )
    (net (code "146") (name "Net-(D3-A)") (class "Default")
      (node (ref "D3") (pin "1") (pinfunction "A_1") (pintype "passive"))
      (node (ref "R18") (pin "2") (pinfunction "2_2") (pintype "passive"))
    )
    (net (code "147") (name "Net-(D4-A)") (class "Default")
      (node (ref "D4") (pin "1") (pinfunction "A_1") (pintype "passive"))
      (node (ref "R19") (pin "2") (pinfunction "2_2") (pintype "passive"))
    )
    (net (code "148") (name "Net-(D5-A)") (class "Default")
      (node (ref "D5") (pin "1") (pinfunction "A_1") (pintype "passive"))
      (node (ref "R20") (pin "2") (pinfunction "2_2") (pintype "passive"))
    )
    (net (code "149") (name "Net-(D6-A)") (class "Default")
      (node (ref "D6") (pin "1") (pinfunction "A_1") (pintype "passive"))
      (node (ref "R21") (pin "2") (pinfunction "2_2") (pintype "passive"))
    )
    (net (code "150") (name "Net-(D7-A)") (class "Default")
      (node (ref "D7") (pin "1") (pinfunction "A_1") (pintype "passive"))
      (node (ref "R22") (pin "2") (pinfunction "2_2") (pintype "passive"))
    )
    (net (code "151") (name "Net-(D8-A)") (class "Default")
      (node (ref "D8") (pin "1") (pinfunction "A_1") (pintype "passive"))
      (node (ref "R14") (pin "2") (pinfunction "2_2") (pintype "passive"))
    )
    (net (code "152") (name "Net-(D9-A)") (class "Default")
      (node (ref "D9") (pin "1") (pinfunction "A_1") (pintype "passive"))
      (node (ref "R15") (pin "2") (pinfunction "2_2") (pintype "passive"))
    )
    (net (code "153") (name "Net-(D10-A)") (class "Default")
      (node (ref "D10") (pin "1") (pinfunction "A_1") (pintype "passive"))
      (node (ref "R16") (pin "2") (pinfunction "2_2") (pintype "passive"))
    )
    (net (code "154") (name "Net-(D11-A)") (class "Default")
      (node (ref "C12") (pin "1") (pinfunction "1_1") (pintype "passive"))
      (node (ref "C7") (pin "1") (pinfunction "1_1") (pintype "passive"))
      (node (ref "D11") (pin "1") (pinfunction "A_1") (pintype "passive"))
      (node (ref "F1") (pin "2") (pinfunction "2_2") (pintype "passive"))
    )
    (net (code "155") (name "Net-(D12-K)") (class "Default")
      (node (ref "D12") (pin "2") (pinfunction "K_2") (pintype "passive"))
      (node (ref "L1") (pin "1") (pinfunction "1_1") (pintype "passive"))
      (node (ref "U2") (pin "2") (pinfunction "OUT_2") (pintype "passive"))
    )
    (net (code "156") (name "Net-(D14-A)") (class "Default")
      (node (ref "D14") (pin "1") (pinfunction "A_1") (pintype "passive"))
      (node (ref "R49") (pin "1") (pinfunction "1_1") (pintype "passive"))
    )
    (net (code "157") (name "Net-(D16-A)") (class "Default")
      (node (ref "D16") (pin "1") (pinfunction "A_1") (pintype "passive"))
      (node (ref "R50") (pin "1") (pinfunction "1_1") (pintype "passive"))
    )
    (net (code "158") (name "Net-(D17-A)") (class "Default")
      (node (ref "D17") (pin "1") (pinfunction "A_1") (pintype "passive"))
      (node (ref "R51") (pin "1") (pinfunction "1_1") (pintype "passive"))
    )
    (net (code "159") (name "Net-(D18-A)") (class "Default")
      (node (ref "D18") (pin "1") (pinfunction "A_1") (pintype "passive"))
      (node (ref "R52") (pin "1") (pinfunction "1_1") (pintype "passive"))
    )
    (net (code "160") (name "Net-(D19-A)") (class "Default")
      (node (ref "D19") (pin "1") (pinfunction "A_1") (pintype "passive"))
      (node (ref "R53") (pin "1") (pinfunction "1_1") (pintype "passive"))
    )
    (net (code "161") (name "Net-(D20-A)") (class "Default")
      (node (ref "D20") (pin "1") (pinfunction "A_1") (pintype "passive"))
      (node (ref "R54") (pin "1") (pinfunction "1_1") (pintype "passive"))
    )
    (net (code "162") (name "Net-(D21-A)") (class "Default")
      (node (ref "D21") (pin "1") (pinfunction "A_1") (pintype "passive"))
      (node (ref "R55") (pin "1") (pinfunction "1_1") (pintype "passive"))
    )
    (net (code "163") (name "Net-(D22-A)") (class "Default")
      (node (ref "D22") (pin "1") (pinfunction "A_1") (pintype "passive"))
      (node (ref "R65") (pin "2") (pinfunction "2_2") (pintype "passive"))
    )
    (net (code "164") (name "Net-(D23-A)") (class "Default")
      (node (ref "D23") (pin "1") (pinfunction "A_1") (pintype "passive"))
      (node (ref "R66") (pin "2") (pinfunction "2_2") (pintype "passive"))
    )
    (net (code "165") (name "Net-(D24-A)") (class "Default")
      (node (ref "D24") (pin "1") (pinfunction "A_1") (pintype "passive"))
      (node (ref "R67") (pin "2") (pinfunction "2_2") (pintype "passive"))
    )
    (net (code "166") (name "Net-(D25-A)") (class "Default")
      (node (ref "D25") (pin "1") (pinfunction "A_1") (pintype "passive"))
      (node (ref "R68") (pin "2") (pinfunction "2_2") (pintype "passive"))
    )
    (net (code "167") (name "Net-(D26-A)") (class "Default")
      (node (ref "D26") (pin "1") (pinfunction "A_1") (pintype "passive"))
      (node (ref "R69") (pin "2") (pinfunction "2_2") (pintype "passive"))
    )
    (net (code "168") (name "Net-(D27-A)") (class "Default")
      (node (ref "D27") (pin "1") (pinfunction "A_1") (pintype "passive"))
      (node (ref "R70") (pin "2") (pinfunction "2_2") (pintype "passive"))
    )
    (net (code "169") (name "Net-(D28-A)") (class "Default")
      (node (ref "D28") (pin "1") (pinfunction "A_1") (pintype "passive"))
      (node (ref "R71") (pin "2") (pinfunction "2_2") (pintype "passive"))
    )
    (net (code "170") (name "Net-(D29-A)") (class "Default")
      (node (ref "D29") (pin "1") (pinfunction "A_1") (pintype "passive"))
      (node (ref "R72") (pin "2") (pinfunction "2_2") (pintype "passive"))
    )
    (net (code "171") (name "Net-(D30-A)") (class "Default")
      (node (ref "D30") (pin "1") (pinfunction "A_1") (pintype "passive"))
      (node (ref "R73") (pin "2") (pinfunction "2_2") (pintype "passive"))
    )
    (net (code "172") (name "Net-(D31-A)") (class "Default")
      (node (ref "D31") (pin "1") (pinfunction "A_1") (pintype "passive"))
      (node (ref "R74") (pin "2") (pinfunction "2_2") (pintype "passive"))
    )
    (net (code "173") (name "Net-(D32-A)") (class "Default")
      (node (ref "D32") (pin "1") (pinfunction "A_1") (pintype "passive"))
      (node (ref "R75") (pin "2") (pinfunction "2_2") (pintype "passive"))
    )
    (net (code "174") (name "Net-(D33-A)") (class "Default")
      (node (ref "D33") (pin "1") (pinfunction "A_1") (pintype "passive"))
      (node (ref "R76") (pin "2") (pinfunction "2_2") (pintype "passive"))
    )
    (net (code "175") (name "Net-(D34-A)") (class "Default")
      (node (ref "D34") (pin "1") (pinfunction "A_1") (pintype "passive"))
      (node (ref "R85") (pin "2") (pinfunction "2_2") (pintype "passive"))
    )
    (net (code "176") (name "Net-(D34-K)") (class "Default")
      (node (ref "D34") (pin "2") (pinfunction "K_2") (pintype "passive"))
      (node (ref "D39") (pin "A") (pinfunction "A_A") (pintype "passive"))
      (node (ref "J14") (pin "2") (pinfunction "2_2") (pintype "passive"))
      (node (ref "Q3") (pin "3") (pinfunction "D_3") (pintype "input"))
      (node (ref "R81") (pin "2") (pinfunction "2_2") (pintype "passive"))
    )
    (net (code "177") (name "Net-(D35-A)") (class "Default")
      (node (ref "D35") (pin "1") (pinfunction "A_1") (pintype "passive"))
      (node (ref "R86") (pin "2") (pinfunction "2_2") (pintype "passive"))
    )
    (net (code "178") (name "Net-(D35-K)") (class "Default")
      (node (ref "D35") (pin "2") (pinfunction "K_2") (pintype "passive"))
      (node (ref "D40") (pin "A") (pinfunction "A_A") (pintype "passive"))
      (node (ref "J15") (pin "2") (pinfunction "2_2") (pintype "passive"))
      (node (ref "Q4") (pin "3") (pinfunction "D_3") (pintype "input"))
      (node (ref "R82") (pin "2") (pinfunction "2_2") (pintype "passive"))
    )
    (net (code "179") (name "Net-(D36-A)") (class "Default")
      (node (ref "D36") (pin "1") (pinfunction "A_1") (pintype "passive"))
      (node (ref "R102") (pin "2") (pinfunction "2_2") (pintype "passive"))
    )
    (net (code "180") (name "Net-(D36-K)") (class "Default")
      (node (ref "D36") (pin "2") (pinfunction "K_2") (pintype "passive"))
      (node (ref "D41") (pin "A") (pinfunction "A_A") (pintype "passive"))
      (node (ref "J16") (pin "2") (pinfunction "2_2") (pintype "passive"))
      (node (ref "Q5") (pin "3") (pinfunction "D_3") (pintype "input"))
      (node (ref "R97") (pin "2") (pinfunction "2_2") (pintype "passive"))
    )
    (net (code "181") (name "Net-(D37-A)") (class "Default")
      (node (ref "D37") (pin "1") (pinfunction "A_1") (pintype "passive"))
      (node (ref "R103") (pin "2") (pinfunction "2_2") (pintype "passive"))
    )
    (net (code "182") (name "Net-(D37-K)") (class "Default")
      (node (ref "D37") (pin "2") (pinfunction "K_2") (pintype "passive"))
      (node (ref "D42") (pin "A") (pinfunction "A_A") (pintype "passive"))
      (node (ref "J17") (pin "2") (pinfunction "2_2") (pintype "passive"))
      (node (ref "Q6") (pin "2") (pinfunction "D_2") (pintype "passive"))
      (node (ref "R98") (pin "2") (pinfunction "2_2") (pintype "passive"))
    )
    (net (code "183") (name "Net-(D38-A)") (class "Default")
      (node (ref "D38") (pin "1") (pinfunction "A_1") (pintype "passive"))
      (node (ref "R114") (pin "2") (pinfunction "2_2") (pintype "passive"))
    )
    (net (code "184") (name "Net-(D38-K)") (class "Default")
      (node (ref "D38") (pin "2") (pinfunction "K_2") (pintype "passive"))
      (node (ref "D43") (pin "A") (pinfunction "A_A") (pintype "passive"))
      (node (ref "J19") (pin "2") (pinfunction "2_2") (pintype "passive"))
      (node (ref "Q11") (pin "2") (pinfunction "D_2") (pintype "passive"))
      (node (ref "R112") (pin "2") (pinfunction "2_2") (pintype "passive"))
    )
    (net (code "185") (name "Net-(D50-A)") (class "Default")
      (node (ref "D50") (pin "1") (pinfunction "A_1") (pintype "passive"))
      (node (ref "R116") (pin "2") (pinfunction "2_2") (pintype "passive"))
    )
    (net (code "186") (name "Net-(D51-A)") (class "Default")
      (node (ref "D51") (pin "1") (pinfunction "A_1") (pintype "passive"))
      (node (ref "R117") (pin "2") (pinfunction "2_2") (pintype "passive"))
    )
    (net (code "187") (name "Net-(D52-A)") (class "Default")
      (node (ref "D52") (pin "1") (pinfunction "A_1") (pintype "passive"))
      (node (ref "R59") (pin "1") (pinfunction "1_1") (pintype "passive"))
    )
    (net (code "188") (name "Net-(D53-A)") (class "Default")
      (node (ref "D53") (pin "1") (pinfunction "A_1") (pintype "passive"))
      (node (ref "R60") (pin "1") (pinfunction "1_1") (pintype "passive"))
    )
    (net (code "189") (name "Net-(D54-A)") (class "Default")
      (node (ref "D54") (pin "1") (pinfunction "A_1") (pintype "passive"))
      (node (ref "R119") (pin "2") (pinfunction "2_2") (pintype "passive"))
    )
    (net (code "190") (name "Net-(D55-A)") (class "Default")
      (node (ref "D55") (pin "1") (pinfunction "A_1") (pintype "passive"))
      (node (ref "R120") (pin "2") (pinfunction "2_2") (pintype "passive"))
    )
    (net (code "191") (name "Net-(D56-A)") (class "Default")
      (node (ref "D56") (pin "1") (pinfunction "A_1") (pintype "passive"))
      (node (ref "R121") (pin "2") (pinfunction "2_2") (pintype "passive"))
    )
    (net (code "192") (name "Net-(D57-A)") (class "Default")
      (node (ref "D57") (pin "1") (pinfunction "A_1") (pintype "passive"))
      (node (ref "R122") (pin "2") (pinfunction "2_2") (pintype "passive"))
    )
    (net (code "193") (name "Net-(DS1-DP)") (class "Default")
      (node (ref "DS1") (pin "7") (pinfunction "DP_7") (pintype "passive"))
      (node (ref "R9") (pin "2") (pinfunction "2_2") (pintype "passive"))
    )
    (net (code "194") (name "Net-(DS1-a)") (class "Default")
      (node (ref "DS1") (pin "10") (pinfunction "a_10") (pintype "passive"))
      (node (ref "R91") (pin "2") (pinfunction "2_2") (pintype "passive"))
    )
    (net (code "195") (name "Net-(DS1-b)") (class "Default")
      (node (ref "DS1") (pin "9") (pinfunction "b_9") (pintype "passive"))
      (node (ref "R90") (pin "2") (pinfunction "2_2") (pintype "passive"))
    )
    (net (code "196") (name "Net-(DS1-c)") (class "Default")
      (node (ref "DS1") (pin "8") (pinfunction "c_8") (pintype "passive"))
      (node (ref "R89") (pin "2") (pinfunction "2_2") (pintype "passive"))
    )
    (net (code "197") (name "Net-(DS1-d)") (class "Default")
      (node (ref "DS1") (pin "5") (pinfunction "d_5") (pintype "passive"))
      (node (ref "R88") (pin "2") (pinfunction "2_2") (pintype "passive"))
    )
    (net (code "198") (name "Net-(DS1-e)") (class "Default")
      (node (ref "DS1") (pin "4") (pinfunction "e_4") (pintype "passive"))
      (node (ref "R87") (pin "2") (pinfunction "2_2") (pintype "passive"))
    )
    (net (code "199") (name "Net-(DS1-f)") (class "Default")
      (node (ref "DS1") (pin "2") (pinfunction "f_2") (pintype "passive"))
      (node (ref "R84") (pin "2") (pinfunction "2_2") (pintype "passive"))
    )
    (net (code "200") (name "Net-(DS1-g)") (class "Default")
      (node (ref "DS1") (pin "3") (pinfunction "g_3") (pintype "passive"))
      (node (ref "R83") (pin "2") (pinfunction "2_2") (pintype "passive"))
    )
    (net (code "201") (name "Net-(J4-Pad2)") (class "Default")
      (node (ref "J4") (pin "2") (pinfunction "2_2") (pintype "passive"))
      (node (ref "R37") (pin "2") (pinfunction "2_2") (pintype "passive"))
    )
    (net (code "202") (name "Net-(J4-Pad8)") (class "Default")
      (node (ref "J4") (pin "8") (pinfunction "8_8") (pintype "passive"))
      (node (ref "R39") (pin "2") (pinfunction "2_2") (pintype "passive"))
    )
    (net (code "203") (name "Net-(J4-Pad14)") (class "Default")
      (node (ref "J4") (pin "14") (pinfunction "14_14") (pintype "passive"))
      (node (ref "R41") (pin "2") (pinfunction "2_2") (pintype "passive"))
    )
    (net (code "204") (name "Net-(J5-Pad2)") (class "Default")
      (node (ref "J5") (pin "2") (pinfunction "2_2") (pintype "passive"))
      (node (ref "R31") (pin "2") (pinfunction "2_2") (pintype "passive"))
    )
    (net (code "205") (name "Net-(J5-Pad8)") (class "Default")
      (node (ref "J5") (pin "8") (pinfunction "8_8") (pintype "passive"))
      (node (ref "R33") (pin "2") (pinfunction "2_2") (pintype "passive"))
    )
    (net (code "206") (name "Net-(J5-Pad14)") (class "Default")
      (node (ref "J5") (pin "14") (pinfunction "14_14") (pintype "passive"))
      (node (ref "R35") (pin "2") (pinfunction "2_2") (pintype "passive"))
    )
    (net (code "207") (name "Net-(J6-Pad2)") (class "Default")
      (node (ref "J6") (pin "2") (pinfunction "2_2") (pintype "passive"))
      (node (ref "R25") (pin "2") (pinfunction "2_2") (pintype "passive"))
    )
    (net (code "208") (name "Net-(J6-Pad8)") (class "Default")
      (node (ref "J6") (pin "8") (pinfunction "8_8") (pintype "passive"))
      (node (ref "R27") (pin "2") (pinfunction "2_2") (pintype "passive"))
    )
    (net (code "209") (name "Net-(J6-Pad14)") (class "Default")
      (node (ref "J6") (pin "14") (pinfunction "14_14") (pintype "passive"))
      (node (ref "R29") (pin "2") (pinfunction "2_2") (pintype "passive"))
    )
    (net (code "210") (name "Net-(J8-Pad2)") (class "Default")
      (node (ref "J8") (pin "2") (pinfunction "2_2") (pintype "passive"))
      (node (ref "R43") (pin "2") (pinfunction "2_2") (pintype "passive"))
    )
    (net (code "211") (name "Net-(J8-Pad8)") (class "Default")
      (node (ref "J8") (pin "8") (pinfunction "8_8") (pintype "passive"))
      (node (ref "R45") (pin "2") (pinfunction "2_2") (pintype "passive"))
    )
    (net (code "212") (name "Net-(J8-Pad14)") (class "Default")
      (node (ref "J8") (pin "14") (pinfunction "14_14") (pintype "passive"))
      (node (ref "R47") (pin "2") (pinfunction "2_2") (pintype "passive"))
    )
    (net (code "213") (name "Net-(P1-E)") (class "Default")
      (node (ref "P1") (pin "3") (pinfunction "E_3") (pintype "passive"))
      (node (ref "R118") (pin "2") (pinfunction "2_2") (pintype "passive"))
    )
    (net (code "214") (name "Net-(P1-K)") (class "Default")
      (node (ref "P1") (pin "2") (pinfunction "K_2") (pintype "passive"))
      (node (ref "R23") (pin "1") (pinfunction "1_1") (pintype "passive"))
    )
    (net (code "215") (name "Net-(P4-C)") (class "Default")
      (node (ref "P4") (pin "4") (pinfunction "C_4") (pintype "passive"))
      (node (ref "R81") (pin "1") (pinfunction "1_1") (pintype "passive"))
    )
    (net (code "216") (name "Net-(P4-E)") (class "Default")
      (node (ref "P4") (pin "3") (pinfunction "E_3") (pintype "passive"))
      (node (ref "Q3") (pin "1") (pinfunction "G_1") (pintype "input"))
      (node (ref "R79") (pin "1") (pinfunction "1_1") (pintype "passive"))
    )
    (net (code "217") (name "Net-(P4-K)") (class "Default")
      (node (ref "P4") (pin "2") (pinfunction "K_2") (pintype "passive"))
      (node (ref "R77") (pin "1") (pinfunction "1_1") (pintype "passive"))
    )
    (net (code "218") (name "Net-(P5-C)") (class "Default")
      (node (ref "P5") (pin "4") (pinfunction "C_4") (pintype "passive"))
      (node (ref "R82") (pin "1") (pinfunction "1_1") (pintype "passive"))
    )
    (net (code "219") (name "Net-(P5-E)") (class "Default")
      (node (ref "P5") (pin "3") (pinfunction "E_3") (pintype "passive"))
      (node (ref "Q4") (pin "1") (pinfunction "G_1") (pintype "input"))
      (node (ref "R80") (pin "1") (pinfunction "1_1") (pintype "passive"))
    )
    (net (code "220") (name "Net-(P5-K)") (class "Default")
      (node (ref "P5") (pin "2") (pinfunction "K_2") (pintype "passive"))
      (node (ref "R78") (pin "1") (pinfunction "1_1") (pintype "passive"))
    )
    (net (code "221") (name "Net-(P6-C)") (class "Default")
      (node (ref "P6") (pin "4") (pinfunction "C_4") (pintype "passive"))
      (node (ref "R97") (pin "1") (pinfunction "1_1") (pintype "passive"))
    )
    (net (code "222") (name "Net-(P6-E)") (class "Default")
      (node (ref "P6") (pin "3") (pinfunction "E_3") (pintype "passive"))
      (node (ref "Q5") (pin "1") (pinfunction "G_1") (pintype "input"))
      (node (ref "R95") (pin "1") (pinfunction "1_1") (pintype "passive"))
    )
    (net (code "223") (name "Net-(P6-K)") (class "Default")
      (node (ref "P6") (pin "2") (pinfunction "K_2") (pintype "passive"))
      (node (ref "R92") (pin "1") (pinfunction "1_1") (pintype "passive"))
    )
    (net (code "224") (name "Net-(P7-C)") (class "Default")
      (node (ref "P7") (pin "4") (pinfunction "C_4") (pintype "passive"))
      (node (ref "R98") (pin "1") (pinfunction "1_1") (pintype "passive"))
    )
    (net (code "225") (name "Net-(P7-E)") (class "Default")
      (node (ref "P7") (pin "3") (pinfunction "E_3") (pintype "passive"))
      (node (ref "Q6") (pin "1") (pinfunction "G_1") (pintype "passive"))
      (node (ref "R96") (pin "1") (pinfunction "1_1") (pintype "passive"))
    )
    (net (code "226") (name "Net-(P7-K)") (class "Default")
      (node (ref "P7") (pin "2") (pinfunction "K_2") (pintype "passive"))
      (node (ref "R93") (pin "1") (pinfunction "1_1") (pintype "passive"))
    )
    (net (code "227") (name "Net-(P8-C)") (class "Default")
      (node (ref "P8") (pin "4") (pinfunction "C_4") (pintype "passive"))
      (node (ref "R112") (pin "1") (pinfunction "1_1") (pintype "passive"))
    )
    (net (code "228") (name "Net-(P8-E)") (class "Default")
      (node (ref "P8") (pin "3") (pinfunction "E_3") (pintype "passive"))
      (node (ref "Q11") (pin "1") (pinfunction "G_1") (pintype "passive"))
      (node (ref "R110") (pin "1") (pinfunction "1_1") (pintype "passive"))
    )
    (net (code "229") (name "Net-(P8-K)") (class "Default")
      (node (ref "P8") (pin "2") (pinfunction "K_2") (pintype "passive"))
      (node (ref "R109") (pin "1") (pinfunction "1_1") (pintype "passive"))
    )
    (net (code "230") (name "Net-(U11-C1+)") (class "Default")
      (node (ref "C32") (pin "2") (pinfunction "2_2") (pintype "passive"))
      (node (ref "U11") (pin "1") (pinfunction "C1+_1") (pintype "passive"))
    )
    (net (code "231") (name "Net-(U11-C1-)") (class "Default")
      (node (ref "C32") (pin "1") (pinfunction "1_1") (pintype "passive"))
      (node (ref "U11") (pin "3") (pinfunction "C1-_3") (pintype "passive"))
    )
    (net (code "232") (name "Net-(U11-C2+)") (class "Default")
      (node (ref "C33") (pin "1") (pinfunction "1_1") (pintype "passive"))
      (node (ref "U11") (pin "4") (pinfunction "C2+_4") (pintype "passive"))
    )
    (net (code "233") (name "Net-(U11-C2-)") (class "Default")
      (node (ref "C33") (pin "2") (pinfunction "2_2") (pintype "passive"))
      (node (ref "U11") (pin "5") (pinfunction "C2-_5") (pintype "passive"))
    )
    (net (code "234") (name "Net-(U11-V+)") (class "Default")
      (node (ref "C52") (pin "1") (pinfunction "1_1") (pintype "passive"))
      (node (ref "U11") (pin "2") (pinfunction "V+_2") (pintype "passive"))
    )
    (net (code "235") (name "Net-(U11-V-)") (class "Default")
      (node (ref "C53") (pin "1") (pinfunction "1_1") (pintype "passive"))
      (node (ref "U11") (pin "6") (pinfunction "V-_6") (pintype "passive"))
    )
    (net (code "236") (name "Net-(U12-C1+)") (class "Default")
      (node (ref "C34") (pin "2") (pinfunction "2_2") (pintype "passive"))
      (node (ref "U12") (pin "1") (pinfunction "C1+_1") (pintype "passive"))
    )
    (net (code "237") (name "Net-(U12-C1-)") (class "Default")
      (node (ref "C34") (pin "1") (pinfunction "1_1") (pintype "passive"))
      (node (ref "U12") (pin "3") (pinfunction "C1-_3") (pintype "passive"))
    )
    (net (code "238") (name "Net-(U12-C2+)") (class "Default")
      (node (ref "C35") (pin "1") (pinfunction "1_1") (pintype "passive"))
      (node (ref "U12") (pin "4") (pinfunction "C2+_4") (pintype "passive"))
    )
    (net (code "239") (name "Net-(U12-C2-)") (class "Default")
      (node (ref "C35") (pin "2") (pinfunction "2_2") (pintype "passive"))
      (node (ref "U12") (pin "5") (pinfunction "C2-_5") (pintype "passive"))
    )
    (net (code "240") (name "Net-(U12-V+)") (class "Default")
      (node (ref "C54") (pin "1") (pinfunction "1_1") (pintype "passive"))
      (node (ref "U12") (pin "2") (pinfunction "V+_2") (pintype "passive"))
    )
    (net (code "241") (name "Net-(U12-V-)") (class "Default")
      (node (ref "C55") (pin "1") (pinfunction "1_1") (pintype "passive"))
      (node (ref "U12") (pin "6") (pinfunction "V-_6") (pintype "passive"))
    )
    (net (code "242") (name "Net-(U16-ENA)") (class "Default")
      (node (ref "C66") (pin "2") (pinfunction "2_2") (pintype "passive"))
      (node (ref "R104") (pin "2") (pinfunction "2_2") (pintype "passive"))
      (node (ref "U16") (pin "8") (pinfunction "ENA_8") (pintype "passive"))
    )
    (net (code "243") (name "Net-(U16-ENB)") (class "Default")
      (node (ref "C64") (pin "1") (pinfunction "1_1") (pintype "passive"))
      (node (ref "R105") (pin "2") (pinfunction "2_2") (pintype "passive"))
      (node (ref "U16") (pin "14") (pinfunction "ENB_14") (pintype "passive"))
    )
    (net (code "244") (name "Net-(U17A-IN-)") (class "Default")
      (node (ref "R111") (pin "1") (pinfunction "1_1") (pintype "passive"))
      (node (ref "R113") (pin "2") (pinfunction "2_2") (pintype "passive"))
      (node (ref "U17") (pin "2") (pinfunction "IN-_2") (pintype "input"))
      (node (ref "U17") (pin "6") (pinfunction "IN-_6") (pintype "input"))
    )
    (net (code "245") (name "Net-(U18-A)") (class "Default")
      (node (ref "R124") (pin "2") (pinfunction "2_2") (pintype "passive"))
      (node (ref "U18") (pin "1") (pinfunction "A_1") (pintype "passive"))
    )
    (net (code "246") (name "Net-(U18-E)") (class "Default")
      (node (ref "C79") (pin "1") (pinfunction "1_1") (pintype "passive"))
      (node (ref "U18") (pin "3") (pinfunction "E_3") (pintype "passive"))
    )
    (net (code "247") (name "Net-(U19-A)") (class "Default")
      (node (ref "R125") (pin "2") (pinfunction "2_2") (pintype "passive"))
      (node (ref "U19") (pin "1") (pinfunction "A_1") (pintype "passive"))
    )
    (net (code "248") (name "Net-(U19-E)") (class "Default")
      (node (ref "C80") (pin "1") (pinfunction "1_1") (pintype "passive"))
      (node (ref "U19") (pin "3") (pinfunction "E_3") (pintype "passive"))
    )
    (net (code "249") (name "Net-(U20-A)") (class "Default")
      (node (ref "R126") (pin "2") (pinfunction "2_2") (pintype "passive"))
      (node (ref "U20") (pin "1") (pinfunction "A_1") (pintype "passive"))
    )
    (net (code "250") (name "Net-(U20-E)") (class "Default")
      (node (ref "C81") (pin "1") (pinfunction "1_1") (pintype "passive"))
      (node (ref "U20") (pin "3") (pinfunction "E_3") (pintype "passive"))
    )
    (net (code "251") (name "Net-(U21-A)") (class "Default")
      (node (ref "R127") (pin "2") (pinfunction "2_2") (pintype "passive"))
      (node (ref "U21") (pin "1") (pinfunction "A_1") (pintype "passive"))
    )
    (net (code "252") (name "Net-(U21-E)") (class "Default")
      (node (ref "C82") (pin "1") (pinfunction "1_1") (pintype "passive"))
      (node (ref "U21") (pin "3") (pinfunction "E_3") (pintype "passive"))
    )
    (net (code "253") (name "Net-(U23-OSCIN)") (class "Default")
      (node (ref "C93") (pin "2") (pinfunction "2_2") (pintype "passive"))
      (node (ref "U23") (pin "21") (pinfunction "OSCIN_21") (pintype "passive"))
      (node (ref "Y1") (pin "1") (pinfunction "OSC1_1") (pintype "passive"))
    )
    (net (code "254") (name "Net-(U23-OSCOUT)") (class "Default")
      (node (ref "C92") (pin "2") (pinfunction "2_2") (pintype "passive"))
      (node (ref "U23") (pin "22") (pinfunction "OSCOUT_22") (pintype "passive"))
      (node (ref "Y1") (pin "2") (pinfunction "OSC2_2") (pintype "passive"))
    )
    (net (code "255") (name "Net-(U23-SVDD)") (class "Default")
      (node (ref "R131") (pin "2") (pinfunction "2_2") (pintype "passive"))
      (node (ref "U23") (pin "9") (pinfunction "SVDD_9") (pintype "passive"))
    )
    (net (code "256") (name "VCC3V3") (class "Default")
      (node (ref "C1") (pin "1") (pinfunction "1_1") (pintype "passive"))
      (node (ref "C11") (pin "1") (pinfunction "1_1") (pintype "passive"))
      (node (ref "C14") (pin "1") (pinfunction "1_1") (pintype "passive"))
      (node (ref "C18") (pin "1") (pinfunction "1_1") (pintype "passive"))
      (node (ref "C20") (pin "1") (pinfunction "1_1") (pintype "passive"))
      (node (ref "C26") (pin "1") (pinfunction "1_1") (pintype "passive"))
      (node (ref "C29") (pin "1") (pinfunction "1_1") (pintype "passive"))
      (node (ref "C3") (pin "1") (pinfunction "1_1") (pintype "passive"))
      (node (ref "C30") (pin "1") (pinfunction "1_1") (pintype "passive"))
      (node (ref "C5") (pin "2") (pinfunction "2_2") (pintype "passive"))
      (node (ref "C52") (pin "2") (pinfunction "2_2") (pintype "passive"))
      (node (ref "C54") (pin "2") (pinfunction "2_2") (pintype "passive"))
      (node (ref "C59") (pin "1") (pinfunction "1_1") (pintype "passive"))
      (node (ref "C60") (pin "1") (pinfunction "1_1") (pintype "passive"))
      (node (ref "C71") (pin "2") (pinfunction "2_2") (pintype "passive"))
      (node (ref "C72") (pin "1") (pinfunction "1_1") (pintype "passive"))
      (node (ref "C9") (pin "1") (pinfunction "1_1") (pintype "passive"))
      (node (ref "DS1") (pin "1") (pinfunction "A_1") (pintype "passive"))
      (node (ref "DS1") (pin "6") (pinfunction "A_6") (pintype "passive"))
      (node (ref "J7") (pin "1") (pinfunction "VTREF_1") (pintype "passive"))
      (node (ref "J7") (pin "2") (pinfunction "VSS_2") (pintype "passive"))
      (node (ref "L2") (pin "1") (pinfunction "1_1") (pintype "passive"))
      (node (ref "L7") (pin "1") (pinfunction "1_1") (pintype "passive"))
      (node (ref "R1") (pin "1") (pinfunction "1_1") (pintype "passive"))
      (node (ref "R119") (pin "1") (pinfunction "1_1") (pintype "passive"))
      (node (ref "R120") (pin "1") (pinfunction "1_1") (pintype "passive"))
      (node (ref "R121") (pin "1") (pinfunction "1_1") (pintype "passive"))
      (node (ref "R122") (pin "1") (pinfunction "1_1") (pintype "passive"))
      (node (ref "R124") (pin "1") (pinfunction "1_1") (pintype "passive"))
      (node (ref "R125") (pin "1") (pinfunction "1_1") (pintype "passive"))
      (node (ref "R126") (pin "1") (pinfunction "1_1") (pintype "passive"))
      (node (ref "R127") (pin "1") (pinfunction "1_1") (pintype "passive"))
      (node (ref "R13") (pin "2") (pinfunction "2_2") (pintype "passive"))
      (node (ref "R131") (pin "1") (pinfunction "1_1") (pintype "passive"))
      (node (ref "R132") (pin "1") (pinfunction "1_1") (pintype "passive"))
      (node (ref "R15") (pin "1") (pinfunction "1_1") (pintype "passive"))
      (node (ref "R17") (pin "1") (pinfunction "1_1") (pintype "passive"))
      (node (ref "R18") (pin "1") (pinfunction "1_1") (pintype "passive"))
      (node (ref "R19") (pin "1") (pinfunction "1_1") (pintype "passive"))
      (node (ref "R2") (pin "1") (pinfunction "1_1") (pintype "passive"))
      (node (ref "R20") (pin "1") (pinfunction "1_1") (pintype "passive"))
      (node (ref "R21") (pin "1") (pinfunction "1_1") (pintype "passive"))
      (node (ref "R22") (pin "1") (pinfunction "1_1") (pintype "passive"))
      (node (ref "R3") (pin "1") (pinfunction "1_1") (pintype "passive"))
      (node (ref "R4") (pin "1") (pinfunction "1_1") (pintype "passive"))
      (node (ref "R5") (pin "1") (pinfunction "1_1") (pintype "passive"))
      (node (ref "R57") (pin "2") (pinfunction "2_2") (pintype "passive"))
      (node (ref "R59") (pin "2") (pinfunction "2_2") (pintype "passive"))
      (node (ref "R6") (pin "1") (pinfunction "1_1") (pintype "passive"))
      (node (ref "R60") (pin "2") (pinfunction "2_2") (pintype "passive"))
      (node (ref "R64") (pin "1") (pinfunction "1_1") (pintype "passive"))
      (node (ref "R7") (pin "1") (pinfunction "1_1") (pintype "passive"))
      (node (ref "R8") (pin "1") (pinfunction "1_1") (pintype "passive"))
      (node (ref "U1") (pin "4") (pinfunction "VCC_4") (pintype "passive"))
      (node (ref "U11") (pin "16") (pinfunction "VCC_16") (pintype "passive"))
      (node (ref "U12") (pin "16") (pinfunction "VCC_16") (pintype "passive"))
      (node (ref "U23") (pin "32") (pinfunction "EA_32") (pintype "passive"))
      (node (ref "U3") (pin "8") (pinfunction "VCC_8") (pintype "passive"))
      (node (ref "U5") (pin "100") (pinfunction "VDD_3_100") (pintype "passive"))
      (node (ref "U5") (pin "11") (pinfunction "VDD_5_11") (pintype "passive"))
      (node (ref "U5") (pin "21") (pinfunction "VREF+_21") (pintype "passive"))
      (node (ref "U5") (pin "22") (pinfunction "VDDA_22") (pintype "passive"))
      (node (ref "U5") (pin "28") (pinfunction "VDD_4_28") (pintype "passive"))
      (node (ref "U5") (pin "50") (pinfunction "VDD_1_50") (pintype "passive"))
      (node (ref "U5") (pin "6") (pinfunction "VBAT_6") (pintype "passive"))
      (node (ref "U5") (pin "75") (pinfunction "VDD_2_75") (pintype "passive"))
      (node (ref "U6") (pin "2") (pinfunction "Vout_2") (pintype "passive"))
      (node (ref "U6") (pin "4") (pinfunction "4_4") (pintype "passive"))
      (node (ref "U7") (pin "3") (pinfunction "WP#_3") (pintype "passive"))
      (node (ref "U7") (pin "7") (pinfunction "HOLD_7") (pintype "passive"))
      (node (ref "U7") (pin "8") (pinfunction "VCC_8") (pintype "passive"))
    )
    (net (code "257") (name "unconnected-(J7-DBGACK-Pad19)") (class "Default")
      (node (ref "J7") (pin "19") (pinfunction "DBGACK_19") (pintype "passive"))
    )
    (net (code "258") (name "unconnected-(J7-DBGRQ-Pad17)") (class "Default")
      (node (ref "J7") (pin "17") (pinfunction "DBGRQ_17") (pintype "passive"))
    )
    (net (code "259") (name "unconnected-(J7-RTCK-Pad11)") (class "Default")
      (node (ref "J7") (pin "11") (pinfunction "RTCK_11") (pintype "passive"))
    )
    (net (code "260") (name "unconnected-(U1-NC-Pad1)") (class "Default")
      (node (ref "U1") (pin "1") (pinfunction "NC_1") (pintype "passive"))
    )
    (net (code "261") (name "unconnected-(U5-NC-Pad73)") (class "Default")
      (node (ref "U5") (pin "73") (pinfunction "NC_73") (pintype "passive"))
    )
    (net (code "262") (name "unconnected-(U5-OSC_OUT-Pad13)") (class "Default")
      (node (ref "U5") (pin "13") (pinfunction "OSC_OUT_13") (pintype "passive"))
    )
    (net (code "263") (name "unconnected-(U8-D-Pad2)") (class "Default")
      (node (ref "U8") (pin "2") (pinfunction "D_2") (pintype "passive"))
    )
    (net (code "264") (name "unconnected-(U9-COM-Pad9)") (class "Default")
      (node (ref "U9") (pin "9") (pinfunction "COM_9") (pintype "passive"))
    )
    (net (code "265") (name "unconnected-(U12-R1IN-Pad13)") (class "Default")
      (node (ref "U12") (pin "13") (pinfunction "R1IN_13") (pintype "passive"))
    )
    (net (code "266") (name "unconnected-(U12-R1OUT-Pad12)") (class "Default")
      (node (ref "U12") (pin "12") (pinfunction "R1OUT_12") (pintype "passive"))
    )
    (net (code "267") (name "unconnected-(U12-T1IN-Pad11)") (class "Default")
      (node (ref "U12") (pin "11") (pinfunction "T1IN_11") (pintype "passive"))
    )
    (net (code "268") (name "unconnected-(U12-T1OUT-Pad14)") (class "Default")
      (node (ref "U12") (pin "14") (pinfunction "T1OUT_14") (pintype "passive"))
    )
    (net (code "269") (name "unconnected-(U23-AUX1-Pad19)") (class "Default")
      (node (ref "U23") (pin "19") (pinfunction "AUX1_19") (pintype "passive+no_connect"))
    )
    (net (code "270") (name "unconnected-(U23-AUX2-Pad20)") (class "Default")
      (node (ref "U23") (pin "20") (pinfunction "AUX2_20") (pintype "passive+no_connect"))
    )
    (net (code "271") (name "unconnected-(U23-D1-Pad25)") (class "Default")
      (node (ref "U23") (pin "25") (pinfunction "D1_25") (pintype "passive+no_connect"))
    )
    (net (code "272") (name "unconnected-(U23-D2-Pad26)") (class "Default")
      (node (ref "U23") (pin "26") (pinfunction "D2_26") (pintype "passive+no_connect"))
    )
    (net (code "273") (name "unconnected-(U23-D3-Pad27)") (class "Default")
      (node (ref "U23") (pin "27") (pinfunction "D3_27") (pintype "passive+no_connect"))
    )
    (net (code "274") (name "unconnected-(U23-D4-Pad28)") (class "Default")
      (node (ref "U23") (pin "28") (pinfunction "D4_28") (pintype "passive+no_connect"))
    )
    (net (code "275") (name "unconnected-(U23-IRQ-Pad23)") (class "Default")
      (node (ref "U23") (pin "23") (pinfunction "IRQ_23") (pintype "passive+no_connect"))
    )
    (net (code "276") (name "unconnected-(U23-MFIN-Pad7)") (class "Default")
      (node (ref "U23") (pin "7") (pinfunction "MFIN_7") (pintype "passive+no_connect"))
    )
    (net (code "277") (name "unconnected-(U23-MFOUT-Pad8)") (class "Default")
      (node (ref "U23") (pin "8") (pinfunction "MFOUT_8") (pintype "passive+no_connect"))
    )
    (net (code "278") (name "unconnected-(U23-TX2-Pad13)") (class "Default")
      (node (ref "U23") (pin "13") (pinfunction "TX2_13") (pintype "passive+no_connect"))
    )
  )
)
